# DM01.net
KiCad netlist of a schematic drawn in EAGLE
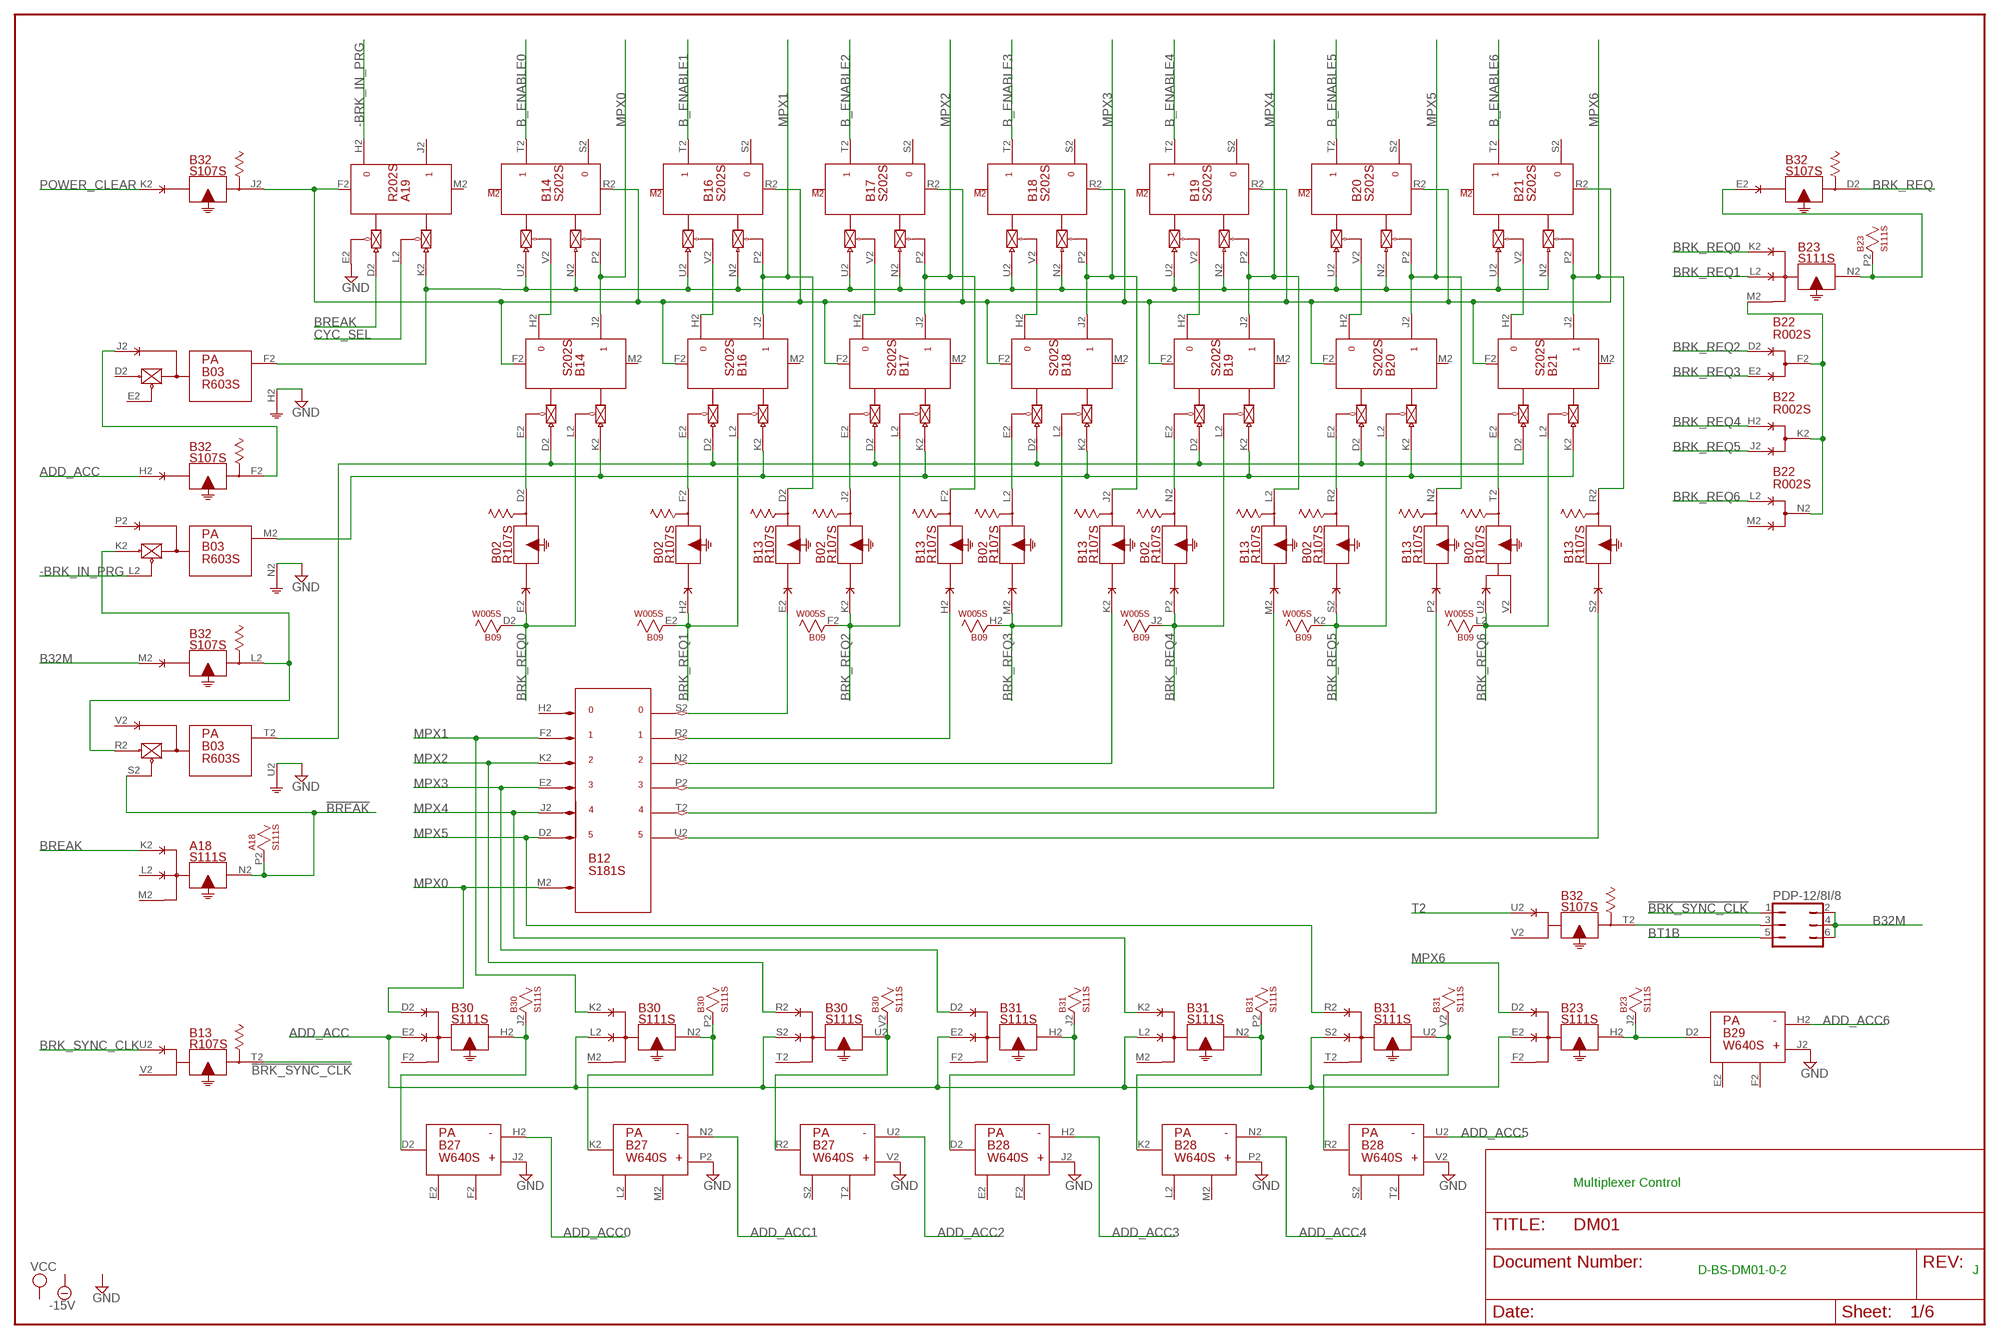
[diagram p0: schematic, sheet 1]
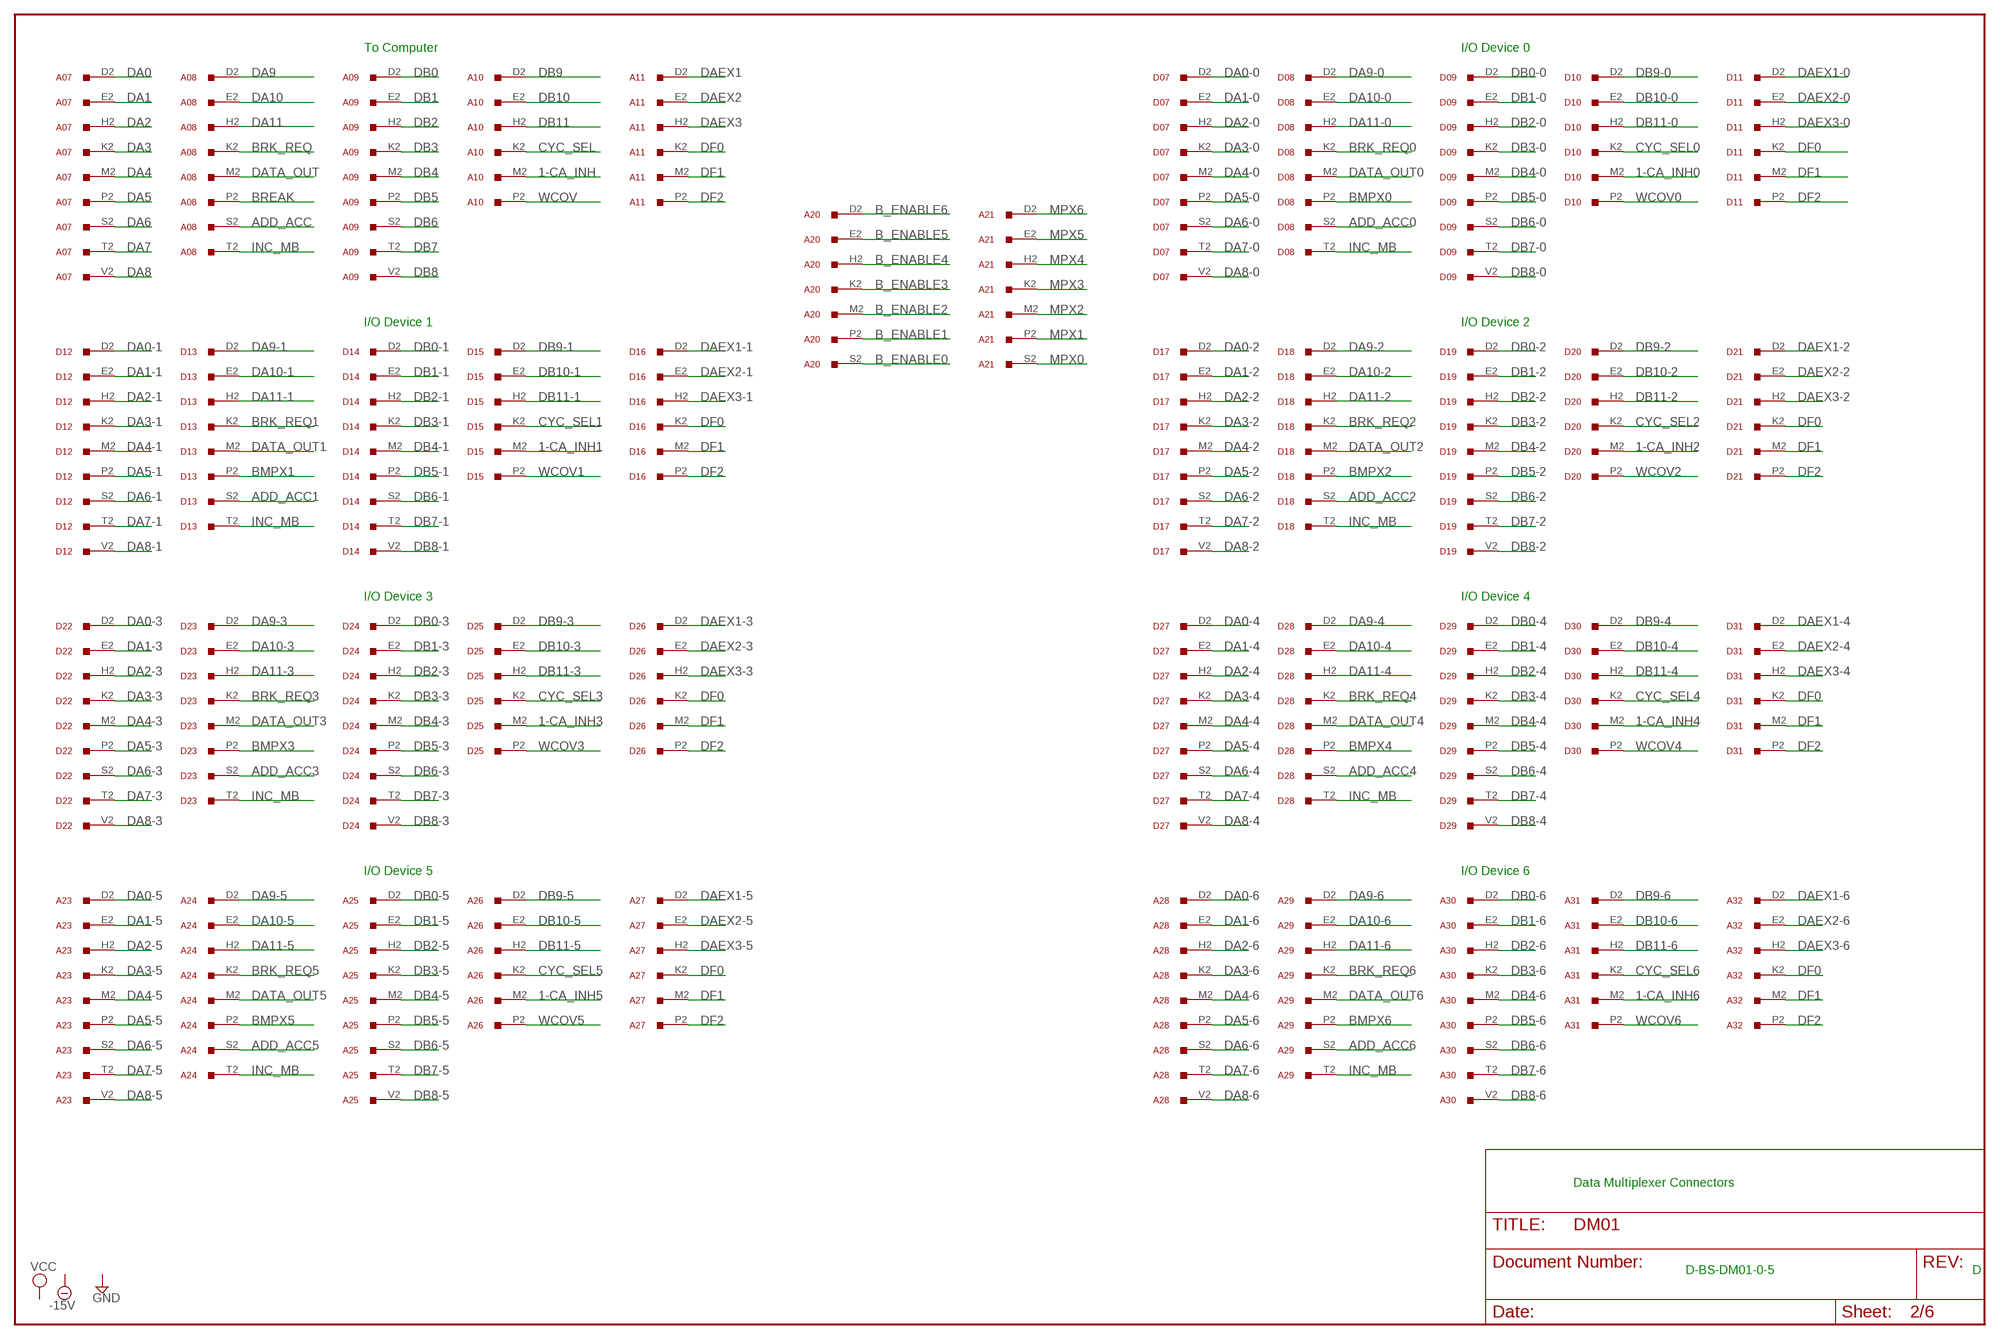
[diagram p1: schematic, sheet 2]
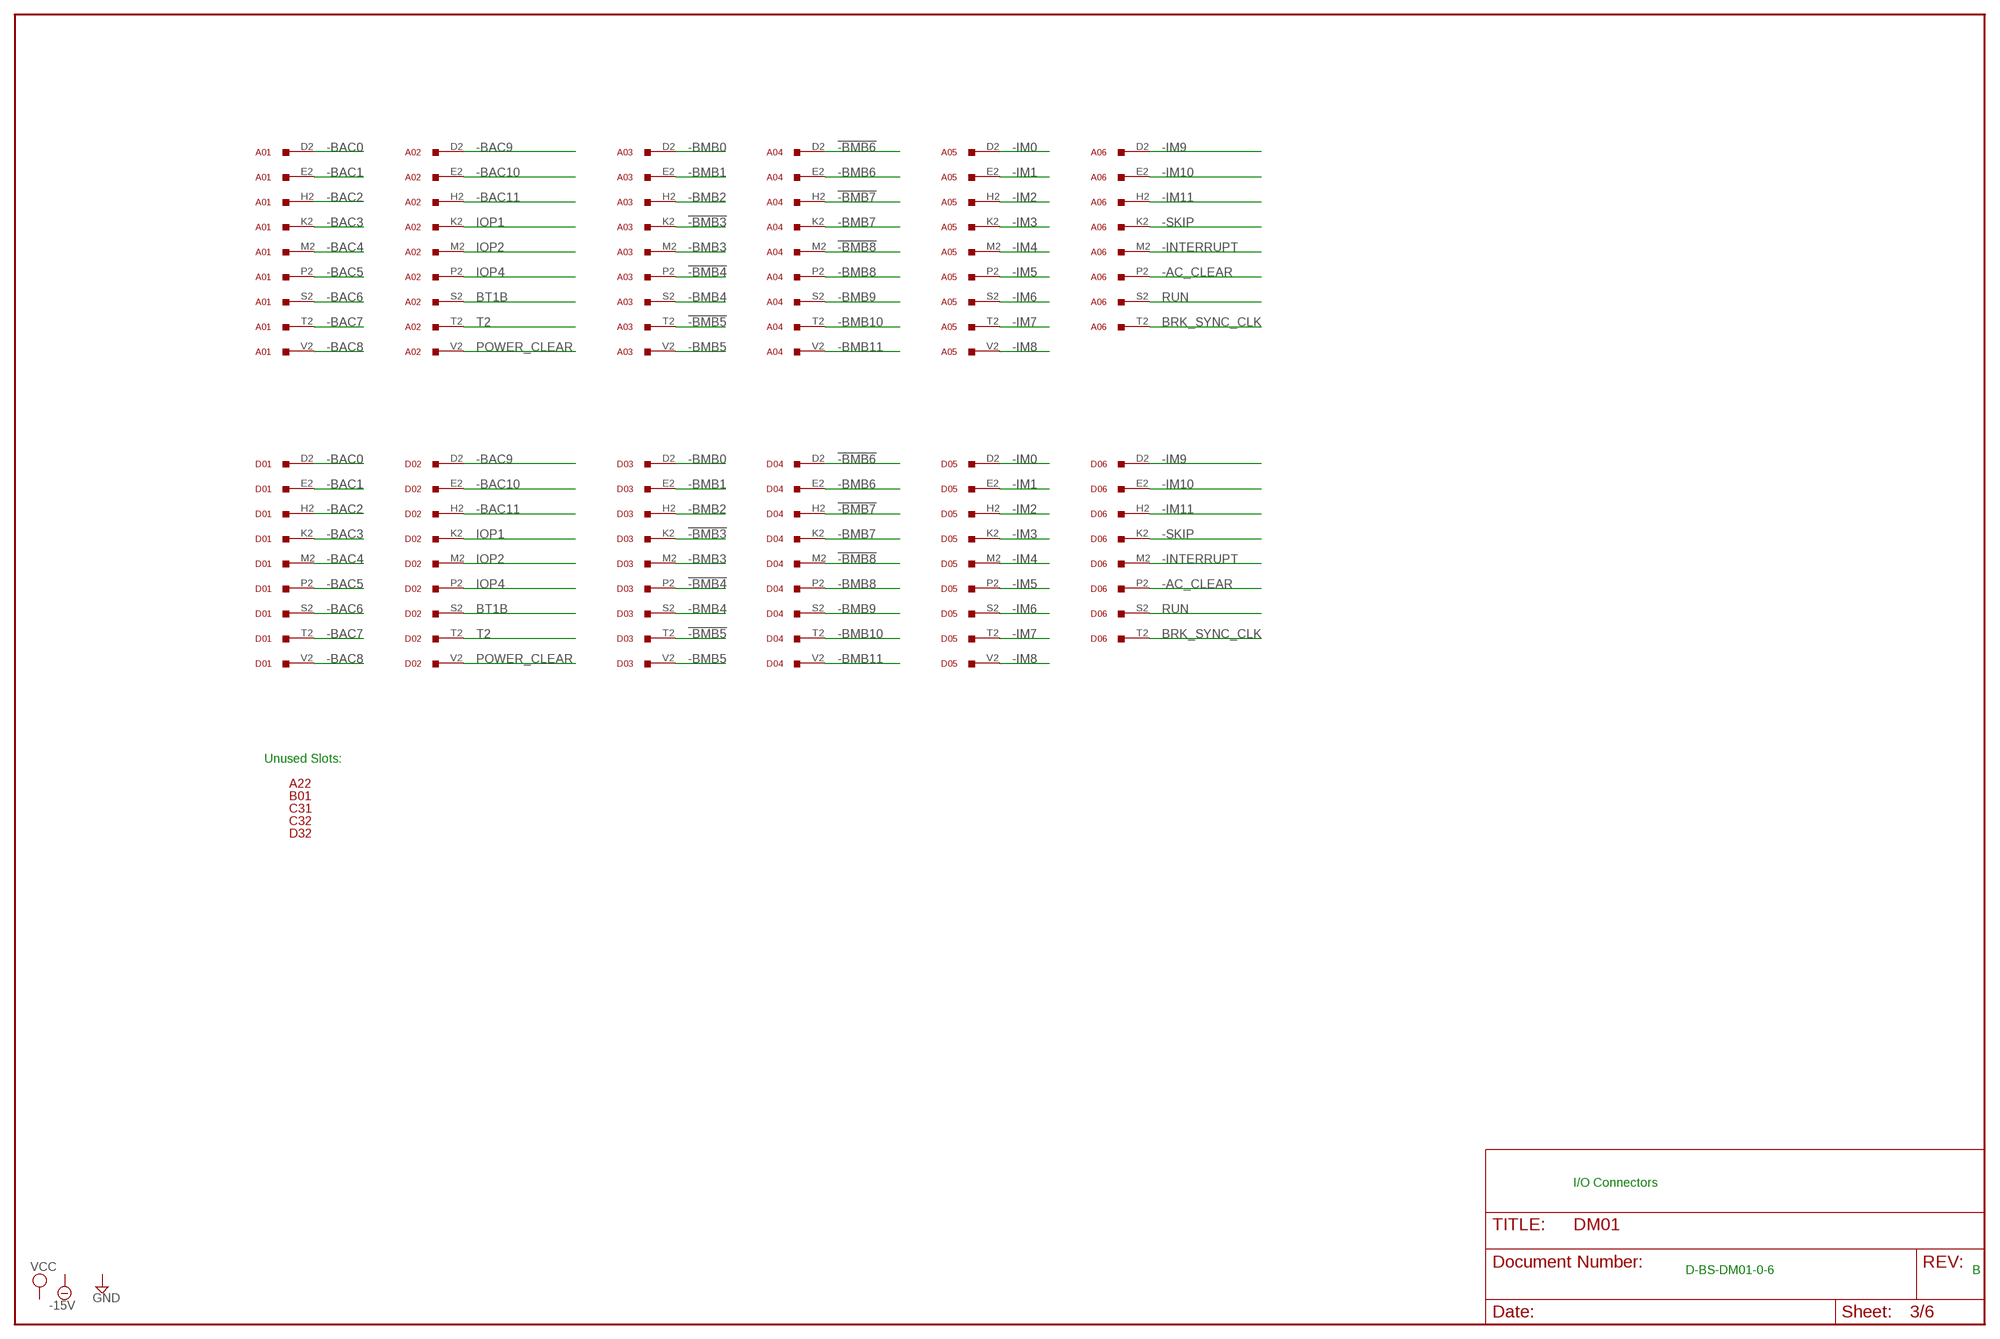
[diagram p2: schematic, sheet 3]
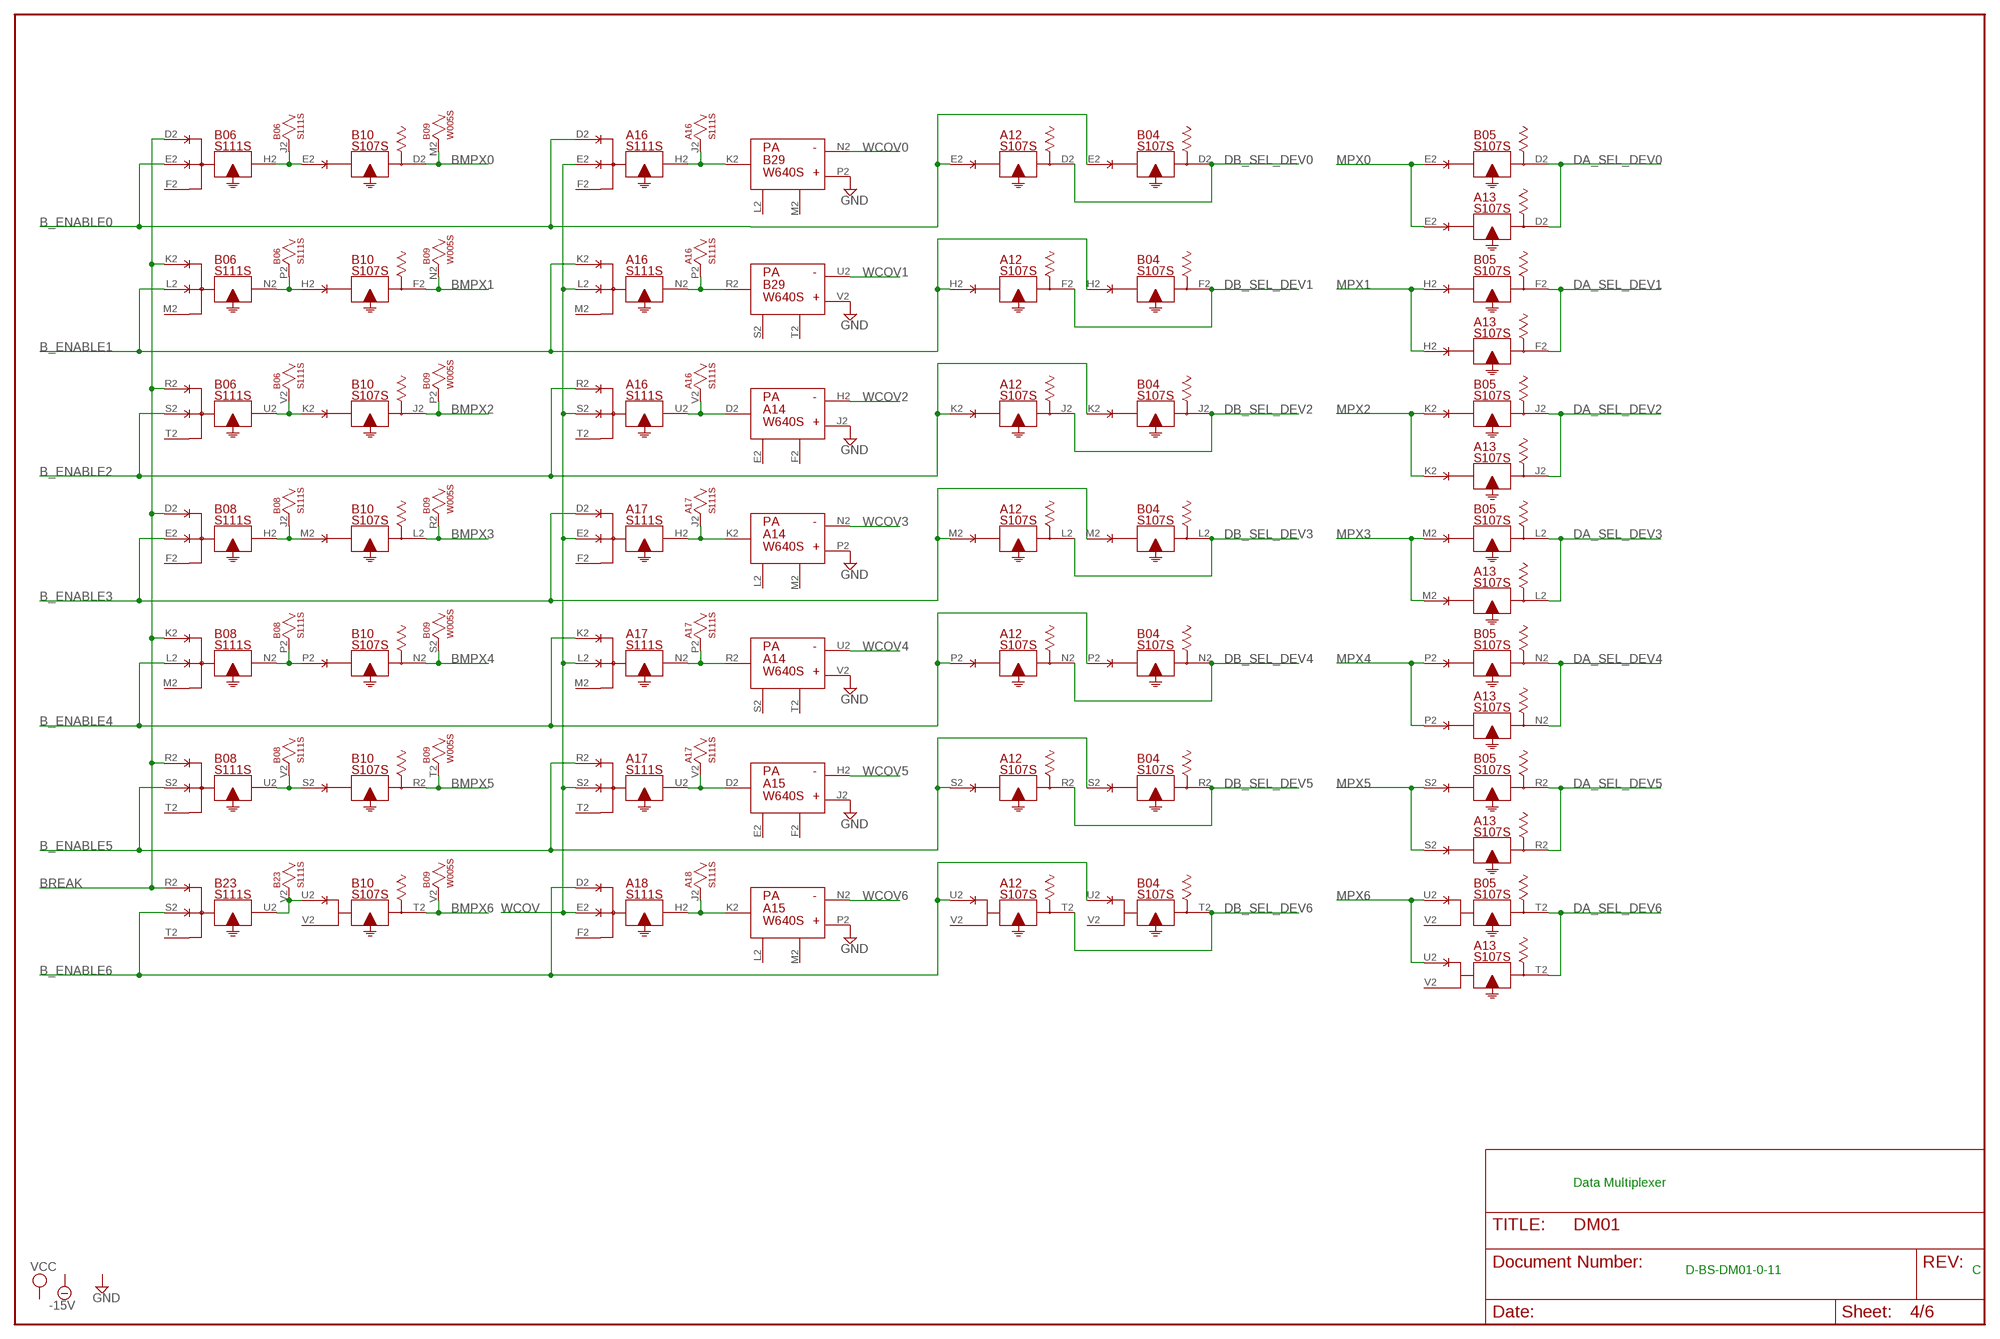
[diagram p3: schematic, sheet 4]
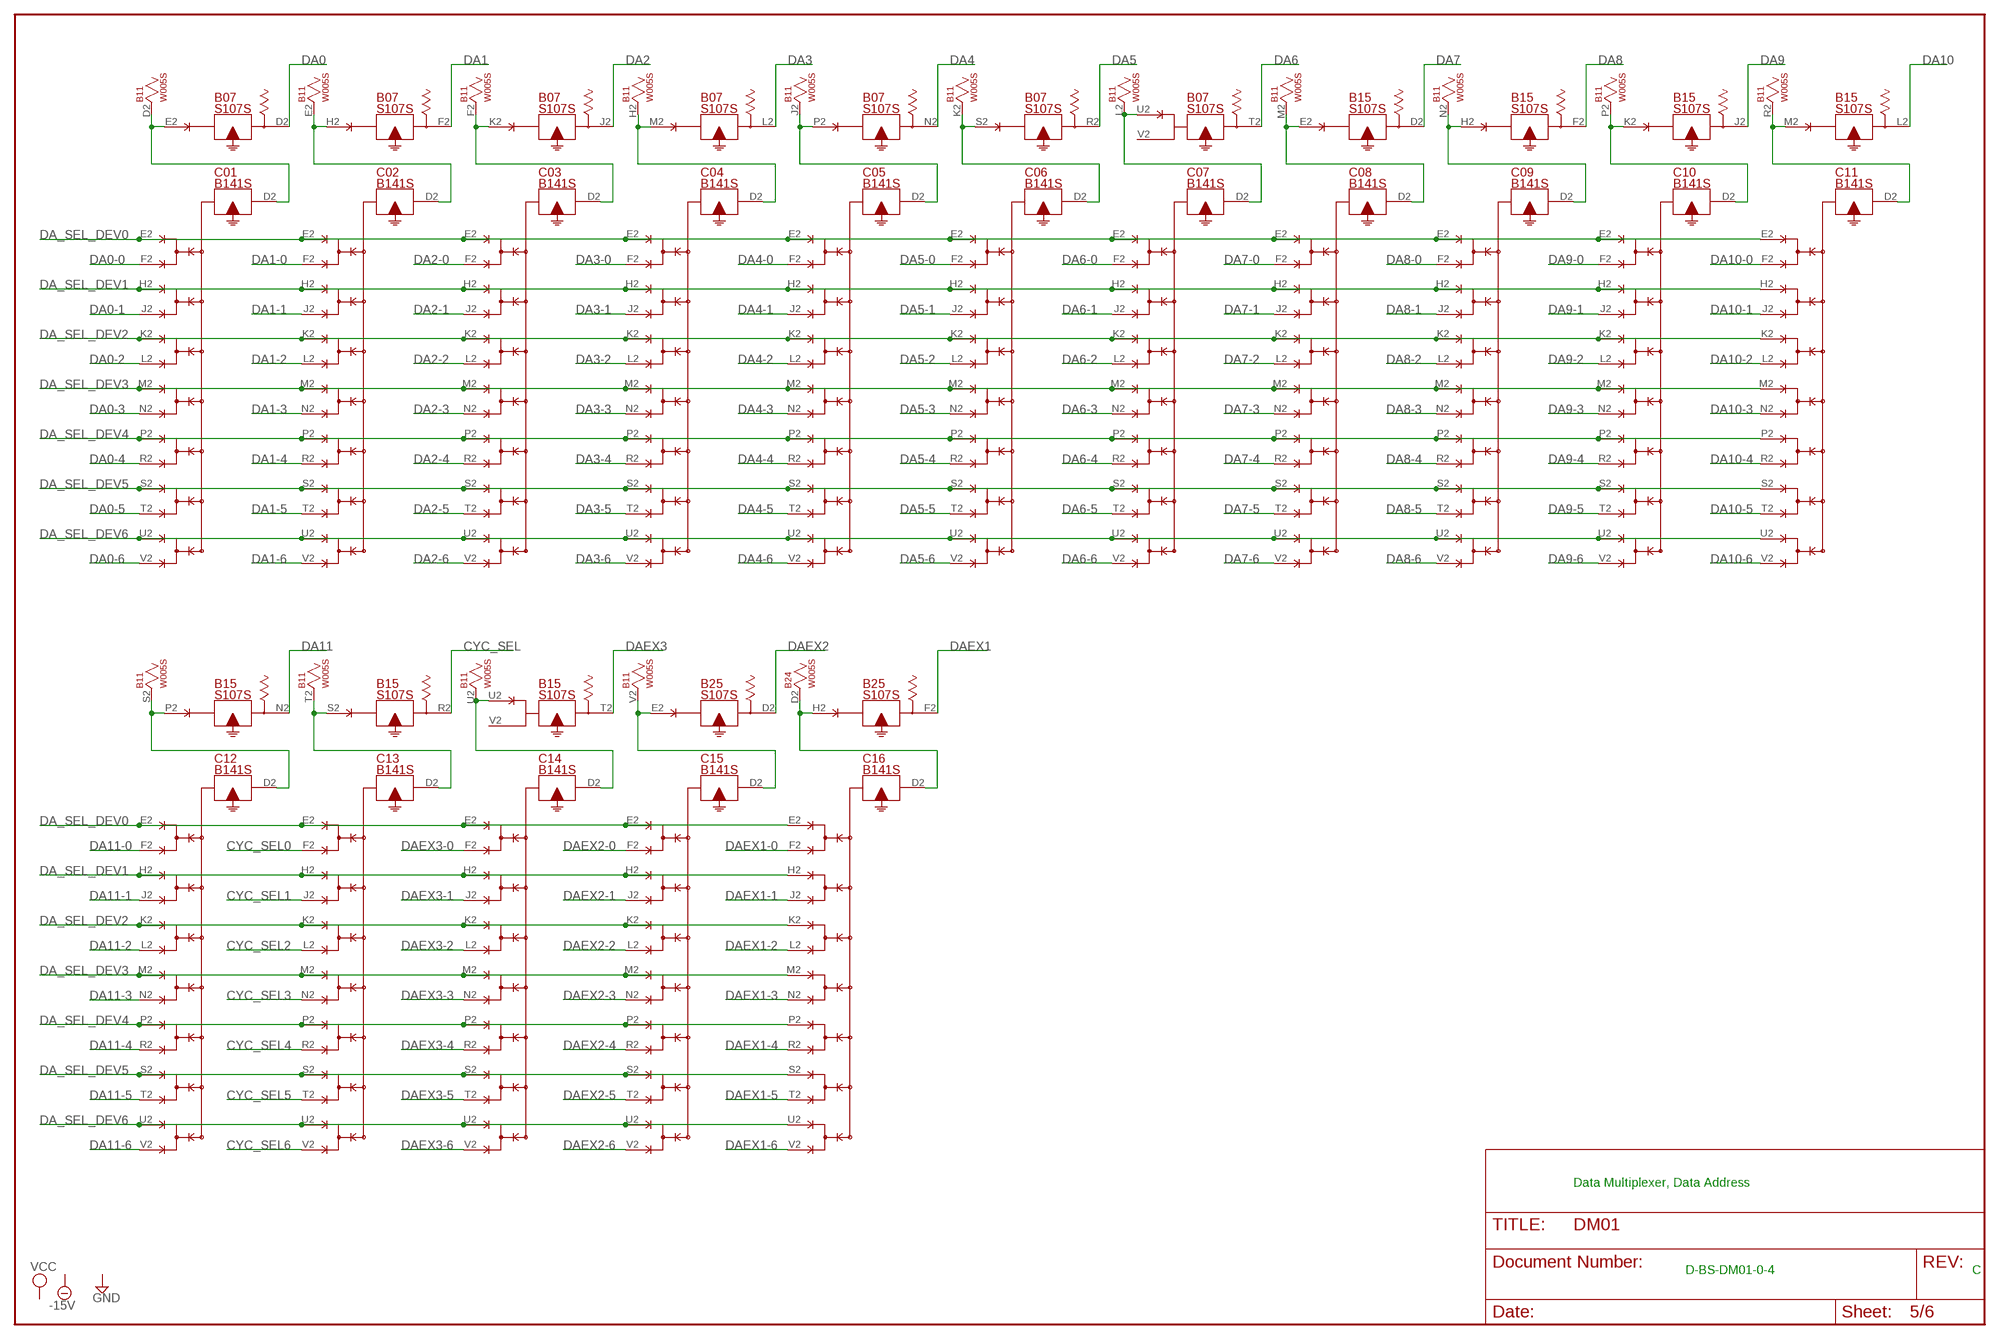
[diagram p4: schematic, sheet 5]
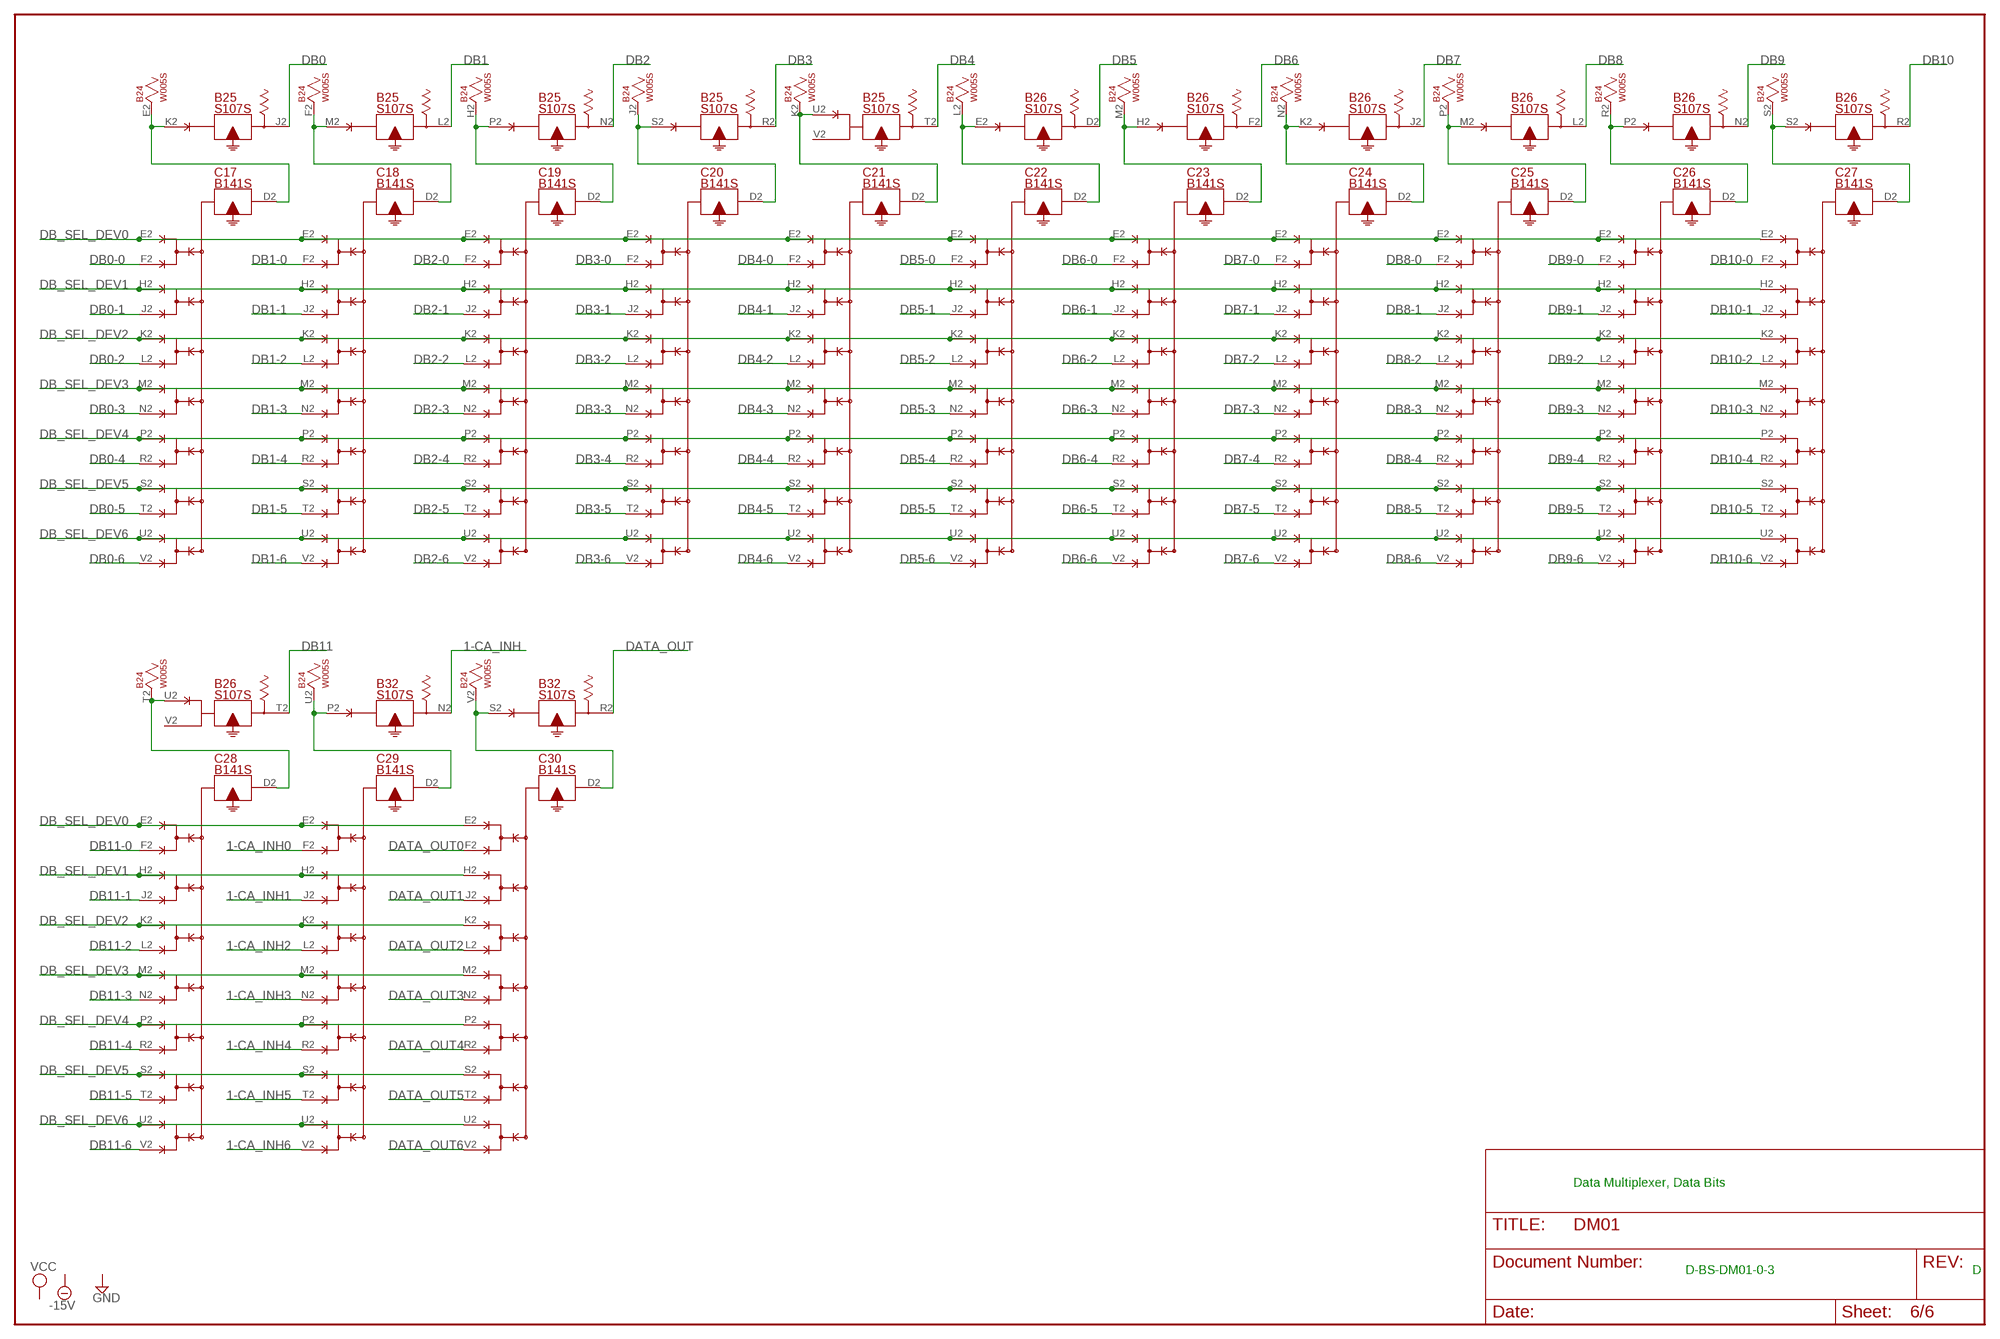
[diagram p5: schematic, sheet 6]

(export (version "E")
  (design (tool "Eeschema 10.0.6"))
  (components
    (comp (ref "A18")
      (value "S111S")
      (footprint "eagle-import:H807S")
      (libsource (lib "eagle-import") (part "R111S"))
    )
    (comp (ref "A19")
      (value "R202S")
      (footprint "eagle-import:H807S")
      (libsource (lib "eagle-import") (part "R202S"))
    )
    (comp (ref "B02")
      (value "R107S")
      (footprint "eagle-import:H807S")
      (libsource (lib "eagle-import") (part "R107S"))
    )
    (comp (ref "B03")
      (value "R603S")
      (footprint "eagle-import:H807S")
      (libsource (lib "eagle-import") (part "R603S"))
    )
    (comp (ref "B09")
      (value "W005S")
      (footprint "eagle-import:H807S")
      (libsource (lib "eagle-import") (part "W005S"))
    )
    (comp (ref "B12")
      (value "S181S")
      (footprint "eagle-import:H807S")
      (libsource (lib "eagle-import") (part "R181S"))
    )
    (comp (ref "B13")
      (value "R107S")
      (footprint "eagle-import:H807S")
      (libsource (lib "eagle-import") (part "R107S"))
    )
    (comp (ref "B14")
      (value "S202S")
      (footprint "eagle-import:H807S")
      (libsource (lib "eagle-import") (part "R202S"))
    )
    (comp (ref "B16")
      (value "S202S")
      (footprint "eagle-import:H807S")
      (libsource (lib "eagle-import") (part "R202S"))
    )
    (comp (ref "B17")
      (value "S202S")
      (footprint "eagle-import:H807S")
      (libsource (lib "eagle-import") (part "R202S"))
    )
    (comp (ref "B18")
      (value "S202S")
      (footprint "eagle-import:H807S")
      (libsource (lib "eagle-import") (part "R202S"))
    )
    (comp (ref "B19")
      (value "S202S")
      (footprint "eagle-import:H807S")
      (libsource (lib "eagle-import") (part "R202S"))
    )
    (comp (ref "B20")
      (value "S202S")
      (footprint "eagle-import:H807S")
      (libsource (lib "eagle-import") (part "R202S"))
    )
    (comp (ref "B21")
      (value "S202S")
      (footprint "eagle-import:H807S")
      (libsource (lib "eagle-import") (part "R202S"))
    )
    (comp (ref "B22")
      (value "R002S")
      (footprint "eagle-import:H807S")
      (libsource (lib "eagle-import") (part "R002S"))
    )
    (comp (ref "B23")
      (value "S111S")
      (footprint "eagle-import:H807S")
      (libsource (lib "eagle-import") (part "R111S"))
    )
    (comp (ref "B27")
      (value "W640S")
      (footprint "eagle-import:H807S")
      (libsource (lib "eagle-import") (part "W640S"))
    )
    (comp (ref "B28")
      (value "W640S")
      (footprint "eagle-import:H807S")
      (libsource (lib "eagle-import") (part "W640S"))
    )
    (comp (ref "B29")
      (value "W640S")
      (footprint "eagle-import:H807S")
      (libsource (lib "eagle-import") (part "W640S"))
    )
    (comp (ref "B30")
      (value "S111S")
      (footprint "eagle-import:H807S")
      (libsource (lib "eagle-import") (part "R111S"))
    )
    (comp (ref "B31")
      (value "S111S")
      (footprint "eagle-import:H807S")
      (libsource (lib "eagle-import") (part "R111S"))
    )
    (comp (ref "B32")
      (value "S107S")
      (footprint "eagle-import:H807S")
      (libsource (lib "eagle-import") (part "R107S"))
    )
    (comp (ref "PDP-12/8I/8")
      (value "JP3Q")
      (footprint "eagle-import:JP3Q")
      (libsource (lib "eagle-import") (part "JP3Q"))
    )
    (comp (ref "A07")
      (value "W021S")
      (footprint "eagle-import:H807S")
      (libsource (lib "eagle-import") (part "W021S"))
    )
    (comp (ref "A08")
      (value "W021S")
      (footprint "eagle-import:H807S")
      (libsource (lib "eagle-import") (part "W021S"))
    )
    (comp (ref "A09")
      (value "W021S")
      (footprint "eagle-import:H807S")
      (libsource (lib "eagle-import") (part "W021S"))
    )
    (comp (ref "A10")
      (value "W021S")
      (footprint "eagle-import:H807S")
      (libsource (lib "eagle-import") (part "W021S"))
    )
    (comp (ref "A11")
      (value "W021S")
      (footprint "eagle-import:H807S")
      (libsource (lib "eagle-import") (part "W021S"))
    )
    (comp (ref "A20")
      (value "W021S")
      (footprint "eagle-import:H807S")
      (libsource (lib "eagle-import") (part "W021S"))
    )
    (comp (ref "A21")
      (value "W021S")
      (footprint "eagle-import:H807S")
      (libsource (lib "eagle-import") (part "W021S"))
    )
    (comp (ref "A23")
      (value "W021S")
      (footprint "eagle-import:H807S")
      (libsource (lib "eagle-import") (part "W021S"))
    )
    (comp (ref "A24")
      (value "W021S")
      (footprint "eagle-import:H807S")
      (libsource (lib "eagle-import") (part "W021S"))
    )
    (comp (ref "A25")
      (value "W021S")
      (footprint "eagle-import:H807S")
      (libsource (lib "eagle-import") (part "W021S"))
    )
    (comp (ref "A26")
      (value "W021S")
      (footprint "eagle-import:H807S")
      (libsource (lib "eagle-import") (part "W021S"))
    )
    (comp (ref "A27")
      (value "W021S")
      (footprint "eagle-import:H807S")
      (libsource (lib "eagle-import") (part "W021S"))
    )
    (comp (ref "A28")
      (value "W021S")
      (footprint "eagle-import:H807S")
      (libsource (lib "eagle-import") (part "W021S"))
    )
    (comp (ref "A29")
      (value "W021S")
      (footprint "eagle-import:H807S")
      (libsource (lib "eagle-import") (part "W021S"))
    )
    (comp (ref "A30")
      (value "W021S")
      (footprint "eagle-import:H807S")
      (libsource (lib "eagle-import") (part "W021S"))
    )
    (comp (ref "A31")
      (value "W021S")
      (footprint "eagle-import:H807S")
      (libsource (lib "eagle-import") (part "W021S"))
    )
    (comp (ref "A32")
      (value "W021S")
      (footprint "eagle-import:H807S")
      (libsource (lib "eagle-import") (part "W021S"))
    )
    (comp (ref "D07")
      (value "W021S")
      (footprint "eagle-import:H807S")
      (libsource (lib "eagle-import") (part "W021S"))
    )
    (comp (ref "D08")
      (value "W021S")
      (footprint "eagle-import:H807S")
      (libsource (lib "eagle-import") (part "W021S"))
    )
    (comp (ref "D09")
      (value "W021S")
      (footprint "eagle-import:H807S")
      (libsource (lib "eagle-import") (part "W021S"))
    )
    (comp (ref "D10")
      (value "W021S")
      (footprint "eagle-import:H807S")
      (libsource (lib "eagle-import") (part "W021S"))
    )
    (comp (ref "D11")
      (value "W021S")
      (footprint "eagle-import:H807S")
      (libsource (lib "eagle-import") (part "W021S"))
    )
    (comp (ref "D12")
      (value "W021S")
      (footprint "eagle-import:H807S")
      (libsource (lib "eagle-import") (part "W021S"))
    )
    (comp (ref "D13")
      (value "W021S")
      (footprint "eagle-import:H807S")
      (libsource (lib "eagle-import") (part "W021S"))
    )
    (comp (ref "D14")
      (value "W021S")
      (footprint "eagle-import:H807S")
      (libsource (lib "eagle-import") (part "W021S"))
    )
    (comp (ref "D15")
      (value "W021S")
      (footprint "eagle-import:H807S")
      (libsource (lib "eagle-import") (part "W021S"))
    )
    (comp (ref "D16")
      (value "W021S")
      (footprint "eagle-import:H807S")
      (libsource (lib "eagle-import") (part "W021S"))
    )
    (comp (ref "D17")
      (value "W021S")
      (footprint "eagle-import:H807S")
      (libsource (lib "eagle-import") (part "W021S"))
    )
    (comp (ref "D18")
      (value "W021S")
      (footprint "eagle-import:H807S")
      (libsource (lib "eagle-import") (part "W021S"))
    )
    (comp (ref "D19")
      (value "W021S")
      (footprint "eagle-import:H807S")
      (libsource (lib "eagle-import") (part "W021S"))
    )
    (comp (ref "D20")
      (value "W021S")
      (footprint "eagle-import:H807S")
      (libsource (lib "eagle-import") (part "W021S"))
    )
    (comp (ref "D21")
      (value "W021S")
      (footprint "eagle-import:H807S")
      (libsource (lib "eagle-import") (part "W021S"))
    )
    (comp (ref "D22")
      (value "W021S")
      (footprint "eagle-import:H807S")
      (libsource (lib "eagle-import") (part "W021S"))
    )
    (comp (ref "D23")
      (value "W021S")
      (footprint "eagle-import:H807S")
      (libsource (lib "eagle-import") (part "W021S"))
    )
    (comp (ref "D24")
      (value "W021S")
      (footprint "eagle-import:H807S")
      (libsource (lib "eagle-import") (part "W021S"))
    )
    (comp (ref "D25")
      (value "W021S")
      (footprint "eagle-import:H807S")
      (libsource (lib "eagle-import") (part "W021S"))
    )
    (comp (ref "D26")
      (value "W021S")
      (footprint "eagle-import:H807S")
      (libsource (lib "eagle-import") (part "W021S"))
    )
    (comp (ref "D27")
      (value "W021S")
      (footprint "eagle-import:H807S")
      (libsource (lib "eagle-import") (part "W021S"))
    )
    (comp (ref "D28")
      (value "W021S")
      (footprint "eagle-import:H807S")
      (libsource (lib "eagle-import") (part "W021S"))
    )
    (comp (ref "D29")
      (value "W021S")
      (footprint "eagle-import:H807S")
      (libsource (lib "eagle-import") (part "W021S"))
    )
    (comp (ref "D30")
      (value "W021S")
      (footprint "eagle-import:H807S")
      (libsource (lib "eagle-import") (part "W021S"))
    )
    (comp (ref "D31")
      (value "W021S")
      (footprint "eagle-import:H807S")
      (libsource (lib "eagle-import") (part "W021S"))
    )
    (comp (ref "B24")
      (value "W005S")
      (footprint "eagle-import:H807S")
      (libsource (lib "eagle-import") (part "W005S"))
    )
    (comp (ref "B25")
      (value "S107S")
      (footprint "eagle-import:H807S")
      (libsource (lib "eagle-import") (part "R107S"))
    )
    (comp (ref "B26")
      (value "S107S")
      (footprint "eagle-import:H807S")
      (libsource (lib "eagle-import") (part "R107S"))
    )
    (comp (ref "C17")
      (value "B141S")
      (footprint "eagle-import:H807S")
      (libsource (lib "eagle-import") (part "R141S"))
    )
    (comp (ref "C18")
      (value "B141S")
      (footprint "eagle-import:H807S")
      (libsource (lib "eagle-import") (part "R141S"))
    )
    (comp (ref "C19")
      (value "B141S")
      (footprint "eagle-import:H807S")
      (libsource (lib "eagle-import") (part "R141S"))
    )
    (comp (ref "C20")
      (value "B141S")
      (footprint "eagle-import:H807S")
      (libsource (lib "eagle-import") (part "R141S"))
    )
    (comp (ref "C21")
      (value "B141S")
      (footprint "eagle-import:H807S")
      (libsource (lib "eagle-import") (part "R141S"))
    )
    (comp (ref "C22")
      (value "B141S")
      (footprint "eagle-import:H807S")
      (libsource (lib "eagle-import") (part "R141S"))
    )
    (comp (ref "C23")
      (value "B141S")
      (footprint "eagle-import:H807S")
      (libsource (lib "eagle-import") (part "R141S"))
    )
    (comp (ref "C24")
      (value "B141S")
      (footprint "eagle-import:H807S")
      (libsource (lib "eagle-import") (part "R141S"))
    )
    (comp (ref "C25")
      (value "B141S")
      (footprint "eagle-import:H807S")
      (libsource (lib "eagle-import") (part "R141S"))
    )
    (comp (ref "C26")
      (value "B141S")
      (footprint "eagle-import:H807S")
      (libsource (lib "eagle-import") (part "R141S"))
    )
    (comp (ref "C27")
      (value "B141S")
      (footprint "eagle-import:H807S")
      (libsource (lib "eagle-import") (part "R141S"))
    )
    (comp (ref "C28")
      (value "B141S")
      (footprint "eagle-import:H807S")
      (libsource (lib "eagle-import") (part "R141S"))
    )
    (comp (ref "C29")
      (value "B141S")
      (footprint "eagle-import:H807S")
      (libsource (lib "eagle-import") (part "R141S"))
    )
    (comp (ref "C30")
      (value "B141S")
      (footprint "eagle-import:H807S")
      (libsource (lib "eagle-import") (part "R141S"))
    )
    (comp (ref "A01")
      (value "W021S")
      (footprint "eagle-import:H807S")
      (libsource (lib "eagle-import") (part "W021S"))
    )
    (comp (ref "A02")
      (value "W021S")
      (footprint "eagle-import:H807S")
      (libsource (lib "eagle-import") (part "W021S"))
    )
    (comp (ref "A03")
      (value "W021S")
      (footprint "eagle-import:H807S")
      (libsource (lib "eagle-import") (part "W021S"))
    )
    (comp (ref "A04")
      (value "W021S")
      (footprint "eagle-import:H807S")
      (libsource (lib "eagle-import") (part "W021S"))
    )
    (comp (ref "A05")
      (value "W021S")
      (footprint "eagle-import:H807S")
      (libsource (lib "eagle-import") (part "W021S"))
    )
    (comp (ref "A06")
      (value "W021S")
      (footprint "eagle-import:H807S")
      (libsource (lib "eagle-import") (part "W021S"))
    )
    (comp (ref "A22")
      (value "EMPTYS")
      (footprint "eagle-import:H807S")
      (libsource (lib "eagle-import") (part "EMPTYS"))
    )
    (comp (ref "B01")
      (value "EMPTYS")
      (footprint "eagle-import:H807S")
      (libsource (lib "eagle-import") (part "EMPTYS"))
    )
    (comp (ref "C31")
      (value "EMPTYS")
      (footprint "eagle-import:H807S")
      (libsource (lib "eagle-import") (part "EMPTYS"))
    )
    (comp (ref "C32")
      (value "EMPTYS")
      (footprint "eagle-import:H807S")
      (libsource (lib "eagle-import") (part "EMPTYS"))
    )
    (comp (ref "D01")
      (value "W021S")
      (footprint "eagle-import:H807S")
      (libsource (lib "eagle-import") (part "W021S"))
    )
    (comp (ref "D02")
      (value "W021S")
      (footprint "eagle-import:H807S")
      (libsource (lib "eagle-import") (part "W021S"))
    )
    (comp (ref "D03")
      (value "W021S")
      (footprint "eagle-import:H807S")
      (libsource (lib "eagle-import") (part "W021S"))
    )
    (comp (ref "D04")
      (value "W021S")
      (footprint "eagle-import:H807S")
      (libsource (lib "eagle-import") (part "W021S"))
    )
    (comp (ref "D05")
      (value "W021S")
      (footprint "eagle-import:H807S")
      (libsource (lib "eagle-import") (part "W021S"))
    )
    (comp (ref "D06")
      (value "W021S")
      (footprint "eagle-import:H807S")
      (libsource (lib "eagle-import") (part "W021S"))
    )
    (comp (ref "D32")
      (value "EMPTYS")
      (footprint "eagle-import:H807S")
      (libsource (lib "eagle-import") (part "EMPTYS"))
    )
    (comp (ref "B07")
      (value "S107S")
      (footprint "eagle-import:H807S")
      (libsource (lib "eagle-import") (part "R107S"))
    )
    (comp (ref "B11")
      (value "W005S")
      (footprint "eagle-import:H807S")
      (libsource (lib "eagle-import") (part "W005S"))
    )
    (comp (ref "B15")
      (value "S107S")
      (footprint "eagle-import:H807S")
      (libsource (lib "eagle-import") (part "R107S"))
    )
    (comp (ref "C01")
      (value "B141S")
      (footprint "eagle-import:H807S")
      (libsource (lib "eagle-import") (part "R141S"))
    )
    (comp (ref "C02")
      (value "B141S")
      (footprint "eagle-import:H807S")
      (libsource (lib "eagle-import") (part "R141S"))
    )
    (comp (ref "C03")
      (value "B141S")
      (footprint "eagle-import:H807S")
      (libsource (lib "eagle-import") (part "R141S"))
    )
    (comp (ref "C04")
      (value "B141S")
      (footprint "eagle-import:H807S")
      (libsource (lib "eagle-import") (part "R141S"))
    )
    (comp (ref "C05")
      (value "B141S")
      (footprint "eagle-import:H807S")
      (libsource (lib "eagle-import") (part "R141S"))
    )
    (comp (ref "C06")
      (value "B141S")
      (footprint "eagle-import:H807S")
      (libsource (lib "eagle-import") (part "R141S"))
    )
    (comp (ref "C07")
      (value "B141S")
      (footprint "eagle-import:H807S")
      (libsource (lib "eagle-import") (part "R141S"))
    )
    (comp (ref "C08")
      (value "B141S")
      (footprint "eagle-import:H807S")
      (libsource (lib "eagle-import") (part "R141S"))
    )
    (comp (ref "C09")
      (value "B141S")
      (footprint "eagle-import:H807S")
      (libsource (lib "eagle-import") (part "R141S"))
    )
    (comp (ref "C10")
      (value "B141S")
      (footprint "eagle-import:H807S")
      (libsource (lib "eagle-import") (part "R141S"))
    )
    (comp (ref "C11")
      (value "B141S")
      (footprint "eagle-import:H807S")
      (libsource (lib "eagle-import") (part "R141S"))
    )
    (comp (ref "C12")
      (value "B141S")
      (footprint "eagle-import:H807S")
      (libsource (lib "eagle-import") (part "R141S"))
    )
    (comp (ref "C13")
      (value "B141S")
      (footprint "eagle-import:H807S")
      (libsource (lib "eagle-import") (part "R141S"))
    )
    (comp (ref "C14")
      (value "B141S")
      (footprint "eagle-import:H807S")
      (libsource (lib "eagle-import") (part "R141S"))
    )
    (comp (ref "C15")
      (value "B141S")
      (footprint "eagle-import:H807S")
      (libsource (lib "eagle-import") (part "R141S"))
    )
    (comp (ref "C16")
      (value "B141S")
      (footprint "eagle-import:H807S")
      (libsource (lib "eagle-import") (part "R141S"))
    )
    (comp (ref "A12")
      (value "S107S")
      (footprint "eagle-import:H807S")
      (libsource (lib "eagle-import") (part "R107S"))
    )
    (comp (ref "A13")
      (value "S107S")
      (footprint "eagle-import:H807S")
      (libsource (lib "eagle-import") (part "R107S"))
    )
    (comp (ref "A14")
      (value "W640S")
      (footprint "eagle-import:H807S")
      (libsource (lib "eagle-import") (part "W640S"))
    )
    (comp (ref "A15")
      (value "W640S")
      (footprint "eagle-import:H807S")
      (libsource (lib "eagle-import") (part "W640S"))
    )
    (comp (ref "A16")
      (value "S111S")
      (footprint "eagle-import:H807S")
      (libsource (lib "eagle-import") (part "R111S"))
    )
    (comp (ref "A17")
      (value "S111S")
      (footprint "eagle-import:H807S")
      (libsource (lib "eagle-import") (part "R111S"))
    )
    (comp (ref "B04")
      (value "S107S")
      (footprint "eagle-import:H807S")
      (libsource (lib "eagle-import") (part "R107S"))
    )
    (comp (ref "B05")
      (value "S107S")
      (footprint "eagle-import:H807S")
      (libsource (lib "eagle-import") (part "R107S"))
    )
    (comp (ref "B06")
      (value "S111S")
      (footprint "eagle-import:H807S")
      (libsource (lib "eagle-import") (part "R111S"))
    )
    (comp (ref "B08")
      (value "S111S")
      (footprint "eagle-import:H807S")
      (libsource (lib "eagle-import") (part "R111S"))
    )
    (comp (ref "B10")
      (value "S107S")
      (footprint "eagle-import:H807S")
      (libsource (lib "eagle-import") (part "R107S"))
    )
  )
  (nets
    (net (code "2") (name "-AC_CLEAR") (class "Default")
      (node (ref "A06") (pin "P2") (pinfunction "P$2_P2") (pintype "bidirectional"))
      (node (ref "D06") (pin "P2") (pinfunction "P$2_P2") (pintype "bidirectional"))
    )
    (net (code "3") (name "-BAC0") (class "Default")
      (node (ref "A01") (pin "D2") (pinfunction "P$2_D2") (pintype "bidirectional"))
      (node (ref "D01") (pin "D2") (pinfunction "P$2_D2") (pintype "bidirectional"))
    )
    (net (code "4") (name "-BAC1") (class "Default")
      (node (ref "A01") (pin "E2") (pinfunction "P$2_E2") (pintype "bidirectional"))
      (node (ref "D01") (pin "E2") (pinfunction "P$2_E2") (pintype "bidirectional"))
    )
    (net (code "5") (name "-BAC2") (class "Default")
      (node (ref "A01") (pin "H2") (pinfunction "P$2_H2") (pintype "bidirectional"))
      (node (ref "D01") (pin "H2") (pinfunction "P$2_H2") (pintype "bidirectional"))
    )
    (net (code "6") (name "-BAC3") (class "Default")
      (node (ref "A01") (pin "K2") (pinfunction "P$2_K2") (pintype "bidirectional"))
      (node (ref "D01") (pin "K2") (pinfunction "P$2_K2") (pintype "bidirectional"))
    )
    (net (code "7") (name "-BAC4") (class "Default")
      (node (ref "A01") (pin "M2") (pinfunction "P$2_M2") (pintype "bidirectional"))
      (node (ref "D01") (pin "M2") (pinfunction "P$2_M2") (pintype "bidirectional"))
    )
    (net (code "8") (name "-BAC5") (class "Default")
      (node (ref "A01") (pin "P2") (pinfunction "P$2_P2") (pintype "bidirectional"))
      (node (ref "D01") (pin "P2") (pinfunction "P$2_P2") (pintype "bidirectional"))
    )
    (net (code "9") (name "-BAC6") (class "Default")
      (node (ref "A01") (pin "S2") (pinfunction "P$2_S2") (pintype "bidirectional"))
      (node (ref "D01") (pin "S2") (pinfunction "P$2_S2") (pintype "bidirectional"))
    )
    (net (code "10") (name "-BAC7") (class "Default")
      (node (ref "A01") (pin "T2") (pinfunction "P$2_T2") (pintype "bidirectional"))
      (node (ref "D01") (pin "T2") (pinfunction "P$2_T2") (pintype "bidirectional"))
    )
    (net (code "11") (name "-BAC8") (class "Default")
      (node (ref "A01") (pin "V2") (pinfunction "P$2_V2") (pintype "bidirectional"))
      (node (ref "D01") (pin "V2") (pinfunction "P$2_V2") (pintype "bidirectional"))
    )
    (net (code "12") (name "-BAC9") (class "Default")
      (node (ref "A02") (pin "D2") (pinfunction "P$2_D2") (pintype "bidirectional"))
      (node (ref "D02") (pin "D2") (pinfunction "P$2_D2") (pintype "bidirectional"))
    )
    (net (code "13") (name "-BAC10") (class "Default")
      (node (ref "A02") (pin "E2") (pinfunction "P$2_E2") (pintype "bidirectional"))
      (node (ref "D02") (pin "E2") (pinfunction "P$2_E2") (pintype "bidirectional"))
    )
    (net (code "14") (name "-BAC11") (class "Default")
      (node (ref "A02") (pin "H2") (pinfunction "P$2_H2") (pintype "bidirectional"))
      (node (ref "D02") (pin "H2") (pinfunction "P$2_H2") (pintype "bidirectional"))
    )
    (net (code "15") (name "-BMB0") (class "Default")
      (node (ref "A03") (pin "D2") (pinfunction "P$2_D2") (pintype "bidirectional"))
      (node (ref "D03") (pin "D2") (pinfunction "P$2_D2") (pintype "bidirectional"))
    )
    (net (code "16") (name "-BMB1") (class "Default")
      (node (ref "A03") (pin "E2") (pinfunction "P$2_E2") (pintype "bidirectional"))
      (node (ref "D03") (pin "E2") (pinfunction "P$2_E2") (pintype "bidirectional"))
    )
    (net (code "17") (name "-BMB2") (class "Default")
      (node (ref "A03") (pin "H2") (pinfunction "P$2_H2") (pintype "bidirectional"))
      (node (ref "D03") (pin "H2") (pinfunction "P$2_H2") (pintype "bidirectional"))
    )
    (net (code "18") (name "-BMB3") (class "Default")
      (node (ref "A03") (pin "M2") (pinfunction "P$2_M2") (pintype "bidirectional"))
      (node (ref "D03") (pin "M2") (pinfunction "P$2_M2") (pintype "bidirectional"))
    )
    (net (code "19") (name "-BMB4") (class "Default")
      (node (ref "A03") (pin "S2") (pinfunction "P$2_S2") (pintype "bidirectional"))
      (node (ref "D03") (pin "S2") (pinfunction "P$2_S2") (pintype "bidirectional"))
    )
    (net (code "20") (name "-BMB5") (class "Default")
      (node (ref "A03") (pin "V2") (pinfunction "P$2_V2") (pintype "bidirectional"))
      (node (ref "D03") (pin "V2") (pinfunction "P$2_V2") (pintype "bidirectional"))
    )
    (net (code "21") (name "-BMB6") (class "Default")
      (node (ref "A04") (pin "E2") (pinfunction "P$2_E2") (pintype "bidirectional"))
      (node (ref "D04") (pin "E2") (pinfunction "P$2_E2") (pintype "bidirectional"))
    )
    (net (code "22") (name "-BMB7") (class "Default")
      (node (ref "A04") (pin "K2") (pinfunction "P$2_K2") (pintype "bidirectional"))
      (node (ref "D04") (pin "K2") (pinfunction "P$2_K2") (pintype "bidirectional"))
    )
    (net (code "23") (name "-BMB8") (class "Default")
      (node (ref "A04") (pin "P2") (pinfunction "P$2_P2") (pintype "bidirectional"))
      (node (ref "D04") (pin "P2") (pinfunction "P$2_P2") (pintype "bidirectional"))
    )
    (net (code "24") (name "-BMB9") (class "Default")
      (node (ref "A04") (pin "S2") (pinfunction "P$2_S2") (pintype "bidirectional"))
      (node (ref "D04") (pin "S2") (pinfunction "P$2_S2") (pintype "bidirectional"))
    )
    (net (code "25") (name "-BMB10") (class "Default")
      (node (ref "A04") (pin "T2") (pinfunction "P$2_T2") (pintype "bidirectional"))
      (node (ref "D04") (pin "T2") (pinfunction "P$2_T2") (pintype "bidirectional"))
    )
    (net (code "26") (name "-BMB11") (class "Default")
      (node (ref "A04") (pin "V2") (pinfunction "P$2_V2") (pintype "bidirectional"))
      (node (ref "D04") (pin "V2") (pinfunction "P$2_V2") (pintype "bidirectional"))
    )
    (net (code "27") (name "-BRK_IN_PRG") (class "Default")
      (node (ref "A19") (pin "H2") (pinfunction "0_H2") (pintype "open_collector"))
      (node (ref "B03") (pin "L2") (pinfunction "EN0_L2") (pintype "passive"))
    )
    (net (code "28") (name "-IM0") (class "Default")
      (node (ref "A05") (pin "D2") (pinfunction "P$2_D2") (pintype "bidirectional"))
      (node (ref "D05") (pin "D2") (pinfunction "P$2_D2") (pintype "bidirectional"))
    )
    (net (code "29") (name "-IM1") (class "Default")
      (node (ref "A05") (pin "E2") (pinfunction "P$2_E2") (pintype "bidirectional"))
      (node (ref "D05") (pin "E2") (pinfunction "P$2_E2") (pintype "bidirectional"))
    )
    (net (code "30") (name "-IM2") (class "Default")
      (node (ref "A05") (pin "H2") (pinfunction "P$2_H2") (pintype "bidirectional"))
      (node (ref "D05") (pin "H2") (pinfunction "P$2_H2") (pintype "bidirectional"))
    )
    (net (code "31") (name "-IM3") (class "Default")
      (node (ref "A05") (pin "K2") (pinfunction "P$2_K2") (pintype "bidirectional"))
      (node (ref "D05") (pin "K2") (pinfunction "P$2_K2") (pintype "bidirectional"))
    )
    (net (code "32") (name "-IM4") (class "Default")
      (node (ref "A05") (pin "M2") (pinfunction "P$2_M2") (pintype "bidirectional"))
      (node (ref "D05") (pin "M2") (pinfunction "P$2_M2") (pintype "bidirectional"))
    )
    (net (code "33") (name "-IM5") (class "Default")
      (node (ref "A05") (pin "P2") (pinfunction "P$2_P2") (pintype "bidirectional"))
      (node (ref "D05") (pin "P2") (pinfunction "P$2_P2") (pintype "bidirectional"))
    )
    (net (code "34") (name "-IM6") (class "Default")
      (node (ref "A05") (pin "S2") (pinfunction "P$2_S2") (pintype "bidirectional"))
      (node (ref "D05") (pin "S2") (pinfunction "P$2_S2") (pintype "bidirectional"))
    )
    (net (code "35") (name "-IM7") (class "Default")
      (node (ref "A05") (pin "T2") (pinfunction "P$2_T2") (pintype "bidirectional"))
      (node (ref "D05") (pin "T2") (pinfunction "P$2_T2") (pintype "bidirectional"))
    )
    (net (code "36") (name "-IM8") (class "Default")
      (node (ref "A05") (pin "V2") (pinfunction "P$2_V2") (pintype "bidirectional"))
      (node (ref "D05") (pin "V2") (pinfunction "P$2_V2") (pintype "bidirectional"))
    )
    (net (code "37") (name "-IM9") (class "Default")
      (node (ref "A06") (pin "D2") (pinfunction "P$2_D2") (pintype "bidirectional"))
      (node (ref "D06") (pin "D2") (pinfunction "P$2_D2") (pintype "bidirectional"))
    )
    (net (code "38") (name "-IM10") (class "Default")
      (node (ref "A06") (pin "E2") (pinfunction "P$2_E2") (pintype "bidirectional"))
      (node (ref "D06") (pin "E2") (pinfunction "P$2_E2") (pintype "bidirectional"))
    )
    (net (code "39") (name "-IM11") (class "Default")
      (node (ref "A06") (pin "H2") (pinfunction "P$2_H2") (pintype "bidirectional"))
      (node (ref "D06") (pin "H2") (pinfunction "P$2_H2") (pintype "bidirectional"))
    )
    (net (code "40") (name "-INTERRUPT") (class "Default")
      (node (ref "A06") (pin "M2") (pinfunction "P$2_M2") (pintype "bidirectional"))
      (node (ref "D06") (pin "M2") (pinfunction "P$2_M2") (pintype "bidirectional"))
    )
    (net (code "41") (name "-SKIP") (class "Default")
      (node (ref "A06") (pin "K2") (pinfunction "P$2_K2") (pintype "bidirectional"))
      (node (ref "D06") (pin "K2") (pinfunction "P$2_K2") (pintype "bidirectional"))
    )
    (net (code "42") (name "1-CA_INH") (class "Default")
      (node (ref "A10") (pin "M2") (pinfunction "P$2_M2") (pintype "bidirectional"))
      (node (ref "B32") (pin "N2") (pinfunction "O$1_N2") (pintype "open_collector"))
    )
    (net (code "43") (name "1-CA_INH0") (class "Default")
      (node (ref "C29") (pin "F2") (pinfunction "F_F2") (pintype "input"))
      (node (ref "D10") (pin "M2") (pinfunction "P$2_M2") (pintype "bidirectional"))
    )
    (net (code "44") (name "1-CA_INH1") (class "Default")
      (node (ref "C29") (pin "J2") (pinfunction "J_J2") (pintype "input"))
      (node (ref "D15") (pin "M2") (pinfunction "P$2_M2") (pintype "bidirectional"))
    )
    (net (code "45") (name "1-CA_INH2") (class "Default")
      (node (ref "C29") (pin "L2") (pinfunction "L_L2") (pintype "input"))
      (node (ref "D20") (pin "M2") (pinfunction "P$2_M2") (pintype "bidirectional"))
    )
    (net (code "46") (name "1-CA_INH3") (class "Default")
      (node (ref "C29") (pin "N2") (pinfunction "N_N2") (pintype "input"))
      (node (ref "D25") (pin "M2") (pinfunction "P$2_M2") (pintype "bidirectional"))
    )
    (net (code "47") (name "1-CA_INH4") (class "Default")
      (node (ref "C29") (pin "R2") (pinfunction "R_R2") (pintype "input"))
      (node (ref "D30") (pin "M2") (pinfunction "P$2_M2") (pintype "bidirectional"))
    )
    (net (code "48") (name "1-CA_INH5") (class "Default")
      (node (ref "A26") (pin "M2") (pinfunction "P$2_M2") (pintype "bidirectional"))
      (node (ref "C29") (pin "T2") (pinfunction "T_T2") (pintype "input"))
    )
    (net (code "49") (name "1-CA_INH6") (class "Default")
      (node (ref "A31") (pin "M2") (pinfunction "P$2_M2") (pintype "bidirectional"))
      (node (ref "C29") (pin "V2") (pinfunction "V_V2") (pintype "input"))
    )
    (net (code "50") (name "ADD_ACC") (class "Default")
      (node (ref "A08") (pin "S2") (pinfunction "P$2_S2") (pintype "bidirectional"))
      (node (ref "B23") (pin "E2") (pinfunction "I$2_E2") (pintype "input"))
      (node (ref "B30") (pin "E2") (pinfunction "I$2_E2") (pintype "input"))
      (node (ref "B30") (pin "L2") (pinfunction "I$2_L2") (pintype "input"))
      (node (ref "B30") (pin "S2") (pinfunction "I$2_S2") (pintype "input"))
      (node (ref "B31") (pin "E2") (pinfunction "I$2_E2") (pintype "input"))
      (node (ref "B31") (pin "L2") (pinfunction "I$2_L2") (pintype "input"))
      (node (ref "B31") (pin "S2") (pinfunction "I$2_S2") (pintype "input"))
      (node (ref "B32") (pin "H2") (pinfunction "I$1_H2") (pintype "input"))
    )
    (net (code "51") (name "ADD_ACC0") (class "Default")
      (node (ref "B27") (pin "H2") (pinfunction "H_H2") (pintype "output"))
      (node (ref "D08") (pin "S2") (pinfunction "P$2_S2") (pintype "bidirectional"))
    )
    (net (code "52") (name "ADD_ACC1") (class "Default")
      (node (ref "B27") (pin "N2") (pinfunction "H_N2") (pintype "output"))
      (node (ref "D13") (pin "S2") (pinfunction "P$2_S2") (pintype "bidirectional"))
    )
    (net (code "53") (name "ADD_ACC2") (class "Default")
      (node (ref "B27") (pin "U2") (pinfunction "H_U2") (pintype "output"))
      (node (ref "D18") (pin "S2") (pinfunction "P$2_S2") (pintype "bidirectional"))
    )
    (net (code "54") (name "ADD_ACC3") (class "Default")
      (node (ref "B28") (pin "H2") (pinfunction "H_H2") (pintype "output"))
      (node (ref "D23") (pin "S2") (pinfunction "P$2_S2") (pintype "bidirectional"))
    )
    (net (code "55") (name "ADD_ACC4") (class "Default")
      (node (ref "B28") (pin "N2") (pinfunction "H_N2") (pintype "output"))
      (node (ref "D28") (pin "S2") (pinfunction "P$2_S2") (pintype "bidirectional"))
    )
    (net (code "56") (name "ADD_ACC5") (class "Default")
      (node (ref "A24") (pin "S2") (pinfunction "P$2_S2") (pintype "bidirectional"))
      (node (ref "B28") (pin "U2") (pinfunction "H_U2") (pintype "output"))
    )
    (net (code "57") (name "ADD_ACC6") (class "Default")
      (node (ref "A29") (pin "S2") (pinfunction "P$2_S2") (pintype "bidirectional"))
      (node (ref "B29") (pin "H2") (pinfunction "H_H2") (pintype "output"))
    )
    (net (code "58") (name "B32M") (class "Default")
      (node (ref "B32") (pin "M2") (pinfunction "I$1_M2") (pintype "input"))
      (node (ref "PDP-12/8I/8") (pin "2") (pinfunction "2_2") (pintype "passive"))
      (node (ref "PDP-12/8I/8") (pin "4") (pinfunction "4_4") (pintype "passive"))
      (node (ref "PDP-12/8I/8") (pin "6") (pinfunction "6_6") (pintype "passive"))
    )
    (net (code "59") (name "BMPX0") (class "Default")
      (node (ref "B09") (pin "M2") (pinfunction "P$1_M2") (pintype "passive"))
      (node (ref "B10") (pin "D2") (pinfunction "O$1_D2") (pintype "open_collector"))
      (node (ref "D08") (pin "P2") (pinfunction "P$2_P2") (pintype "bidirectional"))
    )
    (net (code "60") (name "BMPX1") (class "Default")
      (node (ref "B09") (pin "N2") (pinfunction "P$1_N2") (pintype "passive"))
      (node (ref "B10") (pin "F2") (pinfunction "O$1_F2") (pintype "open_collector"))
      (node (ref "D13") (pin "P2") (pinfunction "P$2_P2") (pintype "bidirectional"))
    )
    (net (code "61") (name "BMPX2") (class "Default")
      (node (ref "B09") (pin "P2") (pinfunction "P$1_P2") (pintype "passive"))
      (node (ref "B10") (pin "J2") (pinfunction "O$1_J2") (pintype "open_collector"))
      (node (ref "D18") (pin "P2") (pinfunction "P$2_P2") (pintype "bidirectional"))
    )
    (net (code "62") (name "BMPX3") (class "Default")
      (node (ref "B09") (pin "R2") (pinfunction "P$1_R2") (pintype "passive"))
      (node (ref "B10") (pin "L2") (pinfunction "O$1_L2") (pintype "open_collector"))
      (node (ref "D23") (pin "P2") (pinfunction "P$2_P2") (pintype "bidirectional"))
    )
    (net (code "63") (name "BMPX4") (class "Default")
      (node (ref "B09") (pin "S2") (pinfunction "P$1_S2") (pintype "passive"))
      (node (ref "B10") (pin "N2") (pinfunction "O$1_N2") (pintype "open_collector"))
      (node (ref "D28") (pin "P2") (pinfunction "P$2_P2") (pintype "bidirectional"))
    )
    (net (code "64") (name "BMPX5") (class "Default")
      (node (ref "A24") (pin "P2") (pinfunction "P$2_P2") (pintype "bidirectional"))
      (node (ref "B09") (pin "T2") (pinfunction "P$1_T2") (pintype "passive"))
      (node (ref "B10") (pin "R2") (pinfunction "O$1_R2") (pintype "open_collector"))
    )
    (net (code "65") (name "BMPX6") (class "Default")
      (node (ref "A29") (pin "P2") (pinfunction "P$2_P2") (pintype "bidirectional"))
      (node (ref "B09") (pin "V2") (pinfunction "P$1_V2") (pintype "passive"))
      (node (ref "B10") (pin "T2") (pinfunction "O$1_T2") (pintype "open_collector"))
    )
    (net (code "66") (name "BREAK") (class "Default")
      (node (ref "A08") (pin "P2") (pinfunction "P$2_P2") (pintype "bidirectional"))
      (node (ref "A18") (pin "K2") (pinfunction "I$1_K2") (pintype "input"))
      (node (ref "A19") (pin "D2") (pinfunction "PU0_D2") (pintype "input"))
      (node (ref "B06") (pin "D2") (pinfunction "I$1_D2") (pintype "input"))
      (node (ref "B06") (pin "K2") (pinfunction "I$1_K2") (pintype "input"))
      (node (ref "B06") (pin "R2") (pinfunction "I$1_R2") (pintype "input"))
      (node (ref "B08") (pin "D2") (pinfunction "I$1_D2") (pintype "input"))
      (node (ref "B08") (pin "K2") (pinfunction "I$1_K2") (pintype "input"))
      (node (ref "B08") (pin "R2") (pinfunction "I$1_R2") (pintype "input"))
      (node (ref "B23") (pin "R2") (pinfunction "I$1_R2") (pintype "input"))
    )
    (net (code "67") (name "BRK_REQ") (class "Default")
      (node (ref "A08") (pin "K2") (pinfunction "P$2_K2") (pintype "bidirectional"))
      (node (ref "B32") (pin "D2") (pinfunction "O$1_D2") (pintype "open_collector"))
    )
    (net (code "68") (name "BRK_REQ0") (class "Default")
      (node (ref "B02") (pin "E2") (pinfunction "I$1_E2") (pintype "input"))
      (node (ref "B09") (pin "D2") (pinfunction "P$1_D2") (pintype "passive"))
      (node (ref "B14") (pin "L2") (pinfunction "EN1_L2") (pintype "input"))
      (node (ref "B23") (pin "K2") (pinfunction "I$1_K2") (pintype "input"))
      (node (ref "D08") (pin "K2") (pinfunction "P$2_K2") (pintype "bidirectional"))
    )
    (net (code "69") (name "BRK_REQ1") (class "Default")
      (node (ref "B02") (pin "H2") (pinfunction "I$1_H2") (pintype "input"))
      (node (ref "B09") (pin "E2") (pinfunction "P$1_E2") (pintype "passive"))
      (node (ref "B16") (pin "L2") (pinfunction "EN1_L2") (pintype "input"))
      (node (ref "B23") (pin "L2") (pinfunction "I$2_L2") (pintype "input"))
      (node (ref "D13") (pin "K2") (pinfunction "P$2_K2") (pintype "bidirectional"))
    )
    (net (code "70") (name "BRK_REQ2") (class "Default")
      (node (ref "B02") (pin "K2") (pinfunction "I$1_K2") (pintype "input"))
      (node (ref "B09") (pin "F2") (pinfunction "P$1_F2") (pintype "passive"))
      (node (ref "B17") (pin "L2") (pinfunction "EN1_L2") (pintype "input"))
      (node (ref "B22") (pin "D2") (pinfunction "D_D2") (pintype "input"))
      (node (ref "D18") (pin "K2") (pinfunction "P$2_K2") (pintype "bidirectional"))
    )
    (net (code "71") (name "BRK_REQ3") (class "Default")
      (node (ref "B02") (pin "M2") (pinfunction "I$1_M2") (pintype "input"))
      (node (ref "B09") (pin "H2") (pinfunction "P$1_H2") (pintype "passive"))
      (node (ref "B18") (pin "L2") (pinfunction "EN1_L2") (pintype "input"))
      (node (ref "B22") (pin "E2") (pinfunction "E_E2") (pintype "input"))
      (node (ref "D23") (pin "K2") (pinfunction "P$2_K2") (pintype "bidirectional"))
    )
    (net (code "72") (name "BRK_REQ4") (class "Default")
      (node (ref "B02") (pin "P2") (pinfunction "I$1_P2") (pintype "input"))
      (node (ref "B09") (pin "J2") (pinfunction "P$1_J2") (pintype "passive"))
      (node (ref "B19") (pin "L2") (pinfunction "EN1_L2") (pintype "input"))
      (node (ref "B22") (pin "H2") (pinfunction "D_H2") (pintype "input"))
      (node (ref "D28") (pin "K2") (pinfunction "P$2_K2") (pintype "bidirectional"))
    )
    (net (code "73") (name "BRK_REQ5") (class "Default")
      (node (ref "A24") (pin "K2") (pinfunction "P$2_K2") (pintype "bidirectional"))
      (node (ref "B02") (pin "S2") (pinfunction "I$1_S2") (pintype "input"))
      (node (ref "B09") (pin "K2") (pinfunction "P$1_K2") (pintype "passive"))
      (node (ref "B20") (pin "L2") (pinfunction "EN1_L2") (pintype "input"))
      (node (ref "B22") (pin "J2") (pinfunction "E_J2") (pintype "input"))
    )
    (net (code "74") (name "BRK_REQ6") (class "Default")
      (node (ref "A29") (pin "K2") (pinfunction "P$2_K2") (pintype "bidirectional"))
      (node (ref "B02") (pin "U2") (pinfunction "I$1_U2") (pintype "input"))
      (node (ref "B09") (pin "L2") (pinfunction "P$1_L2") (pintype "passive"))
      (node (ref "B21") (pin "L2") (pinfunction "EN1_L2") (pintype "input"))
      (node (ref "B22") (pin "L2") (pinfunction "D_L2") (pintype "input"))
    )
    (net (code "75") (name "BRK_SYNC_CLK") (class "Default")
      (node (ref "A06") (pin "T2") (pinfunction "P$2_T2") (pintype "bidirectional"))
      (node (ref "B13") (pin "U2") (pinfunction "I$1_U2") (pintype "input"))
      (node (ref "D06") (pin "T2") (pinfunction "P$2_T2") (pintype "bidirectional"))
    )
    (net (code "76") (name "BT1B") (class "Default")
      (node (ref "A02") (pin "S2") (pinfunction "P$2_S2") (pintype "bidirectional"))
      (node (ref "D02") (pin "S2") (pinfunction "P$2_S2") (pintype "bidirectional"))
      (node (ref "PDP-12/8I/8") (pin "5") (pinfunction "5_5") (pintype "passive"))
    )
    (net (code "77") (name "B_ENABLE0") (class "Default")
      (node (ref "A12") (pin "E2") (pinfunction "I$1_E2") (pintype "input"))
      (node (ref "A16") (pin "D2") (pinfunction "I$1_D2") (pintype "input"))
      (node (ref "A20") (pin "S2") (pinfunction "P$2_S2") (pintype "bidirectional"))
      (node (ref "B04") (pin "E2") (pinfunction "I$1_E2") (pintype "input"))
      (node (ref "B06") (pin "E2") (pinfunction "I$2_E2") (pintype "input"))
      (node (ref "B14") (pin "T2") (pinfunction "1_T2") (pintype "open_collector"))
    )
    (net (code "78") (name "B_ENABLE1") (class "Default")
      (node (ref "A12") (pin "H2") (pinfunction "I$1_H2") (pintype "input"))
      (node (ref "A16") (pin "K2") (pinfunction "I$1_K2") (pintype "input"))
      (node (ref "A20") (pin "P2") (pinfunction "P$2_P2") (pintype "bidirectional"))
      (node (ref "B04") (pin "H2") (pinfunction "I$1_H2") (pintype "input"))
      (node (ref "B06") (pin "L2") (pinfunction "I$2_L2") (pintype "input"))
      (node (ref "B16") (pin "T2") (pinfunction "1_T2") (pintype "open_collector"))
    )
    (net (code "79") (name "B_ENABLE2") (class "Default")
      (node (ref "A12") (pin "K2") (pinfunction "I$1_K2") (pintype "input"))
      (node (ref "A16") (pin "R2") (pinfunction "I$1_R2") (pintype "input"))
      (node (ref "A20") (pin "M2") (pinfunction "P$2_M2") (pintype "bidirectional"))
      (node (ref "B04") (pin "K2") (pinfunction "I$1_K2") (pintype "input"))
      (node (ref "B06") (pin "S2") (pinfunction "I$2_S2") (pintype "input"))
      (node (ref "B17") (pin "T2") (pinfunction "1_T2") (pintype "open_collector"))
    )
    (net (code "80") (name "B_ENABLE3") (class "Default")
      (node (ref "A12") (pin "M2") (pinfunction "I$1_M2") (pintype "input"))
      (node (ref "A17") (pin "D2") (pinfunction "I$1_D2") (pintype "input"))
      (node (ref "A20") (pin "K2") (pinfunction "P$2_K2") (pintype "bidirectional"))
      (node (ref "B04") (pin "M2") (pinfunction "I$1_M2") (pintype "input"))
      (node (ref "B08") (pin "E2") (pinfunction "I$2_E2") (pintype "input"))
      (node (ref "B18") (pin "T2") (pinfunction "1_T2") (pintype "open_collector"))
    )
    (net (code "81") (name "B_ENABLE4") (class "Default")
      (node (ref "A12") (pin "P2") (pinfunction "I$1_P2") (pintype "input"))
      (node (ref "A17") (pin "K2") (pinfunction "I$1_K2") (pintype "input"))
      (node (ref "A20") (pin "H2") (pinfunction "P$2_H2") (pintype "bidirectional"))
      (node (ref "B04") (pin "P2") (pinfunction "I$1_P2") (pintype "input"))
      (node (ref "B08") (pin "L2") (pinfunction "I$2_L2") (pintype "input"))
      (node (ref "B19") (pin "T2") (pinfunction "1_T2") (pintype "open_collector"))
    )
    (net (code "82") (name "B_ENABLE5") (class "Default")
      (node (ref "A12") (pin "S2") (pinfunction "I$1_S2") (pintype "input"))
      (node (ref "A17") (pin "R2") (pinfunction "I$1_R2") (pintype "input"))
      (node (ref "A20") (pin "E2") (pinfunction "P$2_E2") (pintype "bidirectional"))
      (node (ref "B04") (pin "S2") (pinfunction "I$1_S2") (pintype "input"))
      (node (ref "B08") (pin "S2") (pinfunction "I$2_S2") (pintype "input"))
      (node (ref "B20") (pin "T2") (pinfunction "1_T2") (pintype "open_collector"))
    )
    (net (code "83") (name "B_ENABLE6") (class "Default")
      (node (ref "A12") (pin "U2") (pinfunction "I$1_U2") (pintype "input"))
      (node (ref "A18") (pin "D2") (pinfunction "I$1_D2") (pintype "input"))
      (node (ref "A20") (pin "D2") (pinfunction "P$2_D2") (pintype "bidirectional"))
      (node (ref "B04") (pin "U2") (pinfunction "I$1_U2") (pintype "input"))
      (node (ref "B21") (pin "T2") (pinfunction "1_T2") (pintype "open_collector"))
      (node (ref "B23") (pin "S2") (pinfunction "I$2_S2") (pintype "input"))
    )
    (net (code "84") (name "CYC_SEL") (class "Default")
      (node (ref "A10") (pin "K2") (pinfunction "P$2_K2") (pintype "bidirectional"))
      (node (ref "A19") (pin "L2") (pinfunction "EN1_L2") (pintype "input"))
      (node (ref "B15") (pin "R2") (pinfunction "O$1_R2") (pintype "open_collector"))
    )
    (net (code "85") (name "CYC_SEL0") (class "Default")
      (node (ref "C13") (pin "F2") (pinfunction "F_F2") (pintype "input"))
      (node (ref "D10") (pin "K2") (pinfunction "P$2_K2") (pintype "bidirectional"))
    )
    (net (code "86") (name "CYC_SEL1") (class "Default")
      (node (ref "C13") (pin "J2") (pinfunction "J_J2") (pintype "input"))
      (node (ref "D15") (pin "K2") (pinfunction "P$2_K2") (pintype "bidirectional"))
    )
    (net (code "87") (name "CYC_SEL2") (class "Default")
      (node (ref "C13") (pin "L2") (pinfunction "L_L2") (pintype "input"))
      (node (ref "D20") (pin "K2") (pinfunction "P$2_K2") (pintype "bidirectional"))
    )
    (net (code "88") (name "CYC_SEL3") (class "Default")
      (node (ref "C13") (pin "N2") (pinfunction "N_N2") (pintype "input"))
      (node (ref "D25") (pin "K2") (pinfunction "P$2_K2") (pintype "bidirectional"))
    )
    (net (code "89") (name "CYC_SEL4") (class "Default")
      (node (ref "C13") (pin "R2") (pinfunction "R_R2") (pintype "input"))
      (node (ref "D30") (pin "K2") (pinfunction "P$2_K2") (pintype "bidirectional"))
    )
    (net (code "90") (name "CYC_SEL5") (class "Default")
      (node (ref "A26") (pin "K2") (pinfunction "P$2_K2") (pintype "bidirectional"))
      (node (ref "C13") (pin "T2") (pinfunction "T_T2") (pintype "input"))
    )
    (net (code "91") (name "CYC_SEL6") (class "Default")
      (node (ref "A31") (pin "K2") (pinfunction "P$2_K2") (pintype "bidirectional"))
      (node (ref "C13") (pin "V2") (pinfunction "V_V2") (pintype "input"))
    )
    (net (code "92") (name "DA0") (class "Default")
      (node (ref "A07") (pin "D2") (pinfunction "P$2_D2") (pintype "bidirectional"))
      (node (ref "B07") (pin "D2") (pinfunction "O$1_D2") (pintype "open_collector"))
    )
    (net (code "93") (name "DA0-0") (class "Default")
      (node (ref "C01") (pin "F2") (pinfunction "F_F2") (pintype "input"))
      (node (ref "D07") (pin "D2") (pinfunction "P$2_D2") (pintype "bidirectional"))
    )
    (net (code "94") (name "DA0-1") (class "Default")
      (node (ref "C01") (pin "J2") (pinfunction "J_J2") (pintype "input"))
      (node (ref "D12") (pin "D2") (pinfunction "P$2_D2") (pintype "bidirectional"))
    )
    (net (code "95") (name "DA0-2") (class "Default")
      (node (ref "C01") (pin "L2") (pinfunction "L_L2") (pintype "input"))
      (node (ref "D17") (pin "D2") (pinfunction "P$2_D2") (pintype "bidirectional"))
    )
    (net (code "96") (name "DA0-3") (class "Default")
      (node (ref "C01") (pin "N2") (pinfunction "N_N2") (pintype "input"))
      (node (ref "D22") (pin "D2") (pinfunction "P$2_D2") (pintype "bidirectional"))
    )
    (net (code "97") (name "DA0-4") (class "Default")
      (node (ref "C01") (pin "R2") (pinfunction "R_R2") (pintype "input"))
      (node (ref "D27") (pin "D2") (pinfunction "P$2_D2") (pintype "bidirectional"))
    )
    (net (code "98") (name "DA0-5") (class "Default")
      (node (ref "A23") (pin "D2") (pinfunction "P$2_D2") (pintype "bidirectional"))
      (node (ref "C01") (pin "T2") (pinfunction "T_T2") (pintype "input"))
    )
    (net (code "99") (name "DA0-6") (class "Default")
      (node (ref "A28") (pin "D2") (pinfunction "P$2_D2") (pintype "bidirectional"))
      (node (ref "C01") (pin "V2") (pinfunction "V_V2") (pintype "input"))
    )
    (net (code "100") (name "DA1") (class "Default")
      (node (ref "A07") (pin "E2") (pinfunction "P$2_E2") (pintype "bidirectional"))
      (node (ref "B07") (pin "F2") (pinfunction "O$1_F2") (pintype "open_collector"))
    )
    (net (code "101") (name "DA1-0") (class "Default")
      (node (ref "C02") (pin "F2") (pinfunction "F_F2") (pintype "input"))
      (node (ref "D07") (pin "E2") (pinfunction "P$2_E2") (pintype "bidirectional"))
    )
    (net (code "102") (name "DA1-1") (class "Default")
      (node (ref "C02") (pin "J2") (pinfunction "J_J2") (pintype "input"))
      (node (ref "D12") (pin "E2") (pinfunction "P$2_E2") (pintype "bidirectional"))
    )
    (net (code "103") (name "DA1-2") (class "Default")
      (node (ref "C02") (pin "L2") (pinfunction "L_L2") (pintype "input"))
      (node (ref "D17") (pin "E2") (pinfunction "P$2_E2") (pintype "bidirectional"))
    )
    (net (code "104") (name "DA1-3") (class "Default")
      (node (ref "C02") (pin "N2") (pinfunction "N_N2") (pintype "input"))
      (node (ref "D22") (pin "E2") (pinfunction "P$2_E2") (pintype "bidirectional"))
    )
    (net (code "105") (name "DA1-4") (class "Default")
      (node (ref "C02") (pin "R2") (pinfunction "R_R2") (pintype "input"))
      (node (ref "D27") (pin "E2") (pinfunction "P$2_E2") (pintype "bidirectional"))
    )
    (net (code "106") (name "DA1-5") (class "Default")
      (node (ref "A23") (pin "E2") (pinfunction "P$2_E2") (pintype "bidirectional"))
      (node (ref "C02") (pin "T2") (pinfunction "T_T2") (pintype "input"))
    )
    (net (code "107") (name "DA1-6") (class "Default")
      (node (ref "A28") (pin "E2") (pinfunction "P$2_E2") (pintype "bidirectional"))
      (node (ref "C02") (pin "V2") (pinfunction "V_V2") (pintype "input"))
    )
    (net (code "108") (name "DA2") (class "Default")
      (node (ref "A07") (pin "H2") (pinfunction "P$2_H2") (pintype "bidirectional"))
      (node (ref "B07") (pin "J2") (pinfunction "O$1_J2") (pintype "open_collector"))
    )
    (net (code "109") (name "DA2-0") (class "Default")
      (node (ref "C03") (pin "F2") (pinfunction "F_F2") (pintype "input"))
      (node (ref "D07") (pin "H2") (pinfunction "P$2_H2") (pintype "bidirectional"))
    )
    (net (code "110") (name "DA2-1") (class "Default")
      (node (ref "C03") (pin "J2") (pinfunction "J_J2") (pintype "input"))
      (node (ref "D12") (pin "H2") (pinfunction "P$2_H2") (pintype "bidirectional"))
    )
    (net (code "111") (name "DA2-2") (class "Default")
      (node (ref "C03") (pin "L2") (pinfunction "L_L2") (pintype "input"))
      (node (ref "D17") (pin "H2") (pinfunction "P$2_H2") (pintype "bidirectional"))
    )
    (net (code "112") (name "DA2-3") (class "Default")
      (node (ref "C03") (pin "N2") (pinfunction "N_N2") (pintype "input"))
      (node (ref "D22") (pin "H2") (pinfunction "P$2_H2") (pintype "bidirectional"))
    )
    (net (code "113") (name "DA2-4") (class "Default")
      (node (ref "C03") (pin "R2") (pinfunction "R_R2") (pintype "input"))
      (node (ref "D27") (pin "H2") (pinfunction "P$2_H2") (pintype "bidirectional"))
    )
    (net (code "114") (name "DA2-5") (class "Default")
      (node (ref "A23") (pin "H2") (pinfunction "P$2_H2") (pintype "bidirectional"))
      (node (ref "C03") (pin "T2") (pinfunction "T_T2") (pintype "input"))
    )
    (net (code "115") (name "DA2-6") (class "Default")
      (node (ref "A28") (pin "H2") (pinfunction "P$2_H2") (pintype "bidirectional"))
      (node (ref "C03") (pin "V2") (pinfunction "V_V2") (pintype "input"))
    )
    (net (code "116") (name "DA3") (class "Default")
      (node (ref "A07") (pin "K2") (pinfunction "P$2_K2") (pintype "bidirectional"))
      (node (ref "B07") (pin "L2") (pinfunction "O$1_L2") (pintype "open_collector"))
    )
    (net (code "117") (name "DA3-0") (class "Default")
      (node (ref "C04") (pin "F2") (pinfunction "F_F2") (pintype "input"))
      (node (ref "D07") (pin "K2") (pinfunction "P$2_K2") (pintype "bidirectional"))
    )
    (net (code "118") (name "DA3-1") (class "Default")
      (node (ref "C04") (pin "J2") (pinfunction "J_J2") (pintype "input"))
      (node (ref "D12") (pin "K2") (pinfunction "P$2_K2") (pintype "bidirectional"))
    )
    (net (code "119") (name "DA3-2") (class "Default")
      (node (ref "C04") (pin "L2") (pinfunction "L_L2") (pintype "input"))
      (node (ref "D17") (pin "K2") (pinfunction "P$2_K2") (pintype "bidirectional"))
    )
    (net (code "120") (name "DA3-3") (class "Default")
      (node (ref "C04") (pin "N2") (pinfunction "N_N2") (pintype "input"))
      (node (ref "D22") (pin "K2") (pinfunction "P$2_K2") (pintype "bidirectional"))
    )
    (net (code "121") (name "DA3-4") (class "Default")
      (node (ref "C04") (pin "R2") (pinfunction "R_R2") (pintype "input"))
      (node (ref "D27") (pin "K2") (pinfunction "P$2_K2") (pintype "bidirectional"))
    )
    (net (code "122") (name "DA3-5") (class "Default")
      (node (ref "A23") (pin "K2") (pinfunction "P$2_K2") (pintype "bidirectional"))
      (node (ref "C04") (pin "T2") (pinfunction "T_T2") (pintype "input"))
    )
    (net (code "123") (name "DA3-6") (class "Default")
      (node (ref "A28") (pin "K2") (pinfunction "P$2_K2") (pintype "bidirectional"))
      (node (ref "C04") (pin "V2") (pinfunction "V_V2") (pintype "input"))
    )
    (net (code "124") (name "DA4") (class "Default")
      (node (ref "A07") (pin "M2") (pinfunction "P$2_M2") (pintype "bidirectional"))
      (node (ref "B07") (pin "N2") (pinfunction "O$1_N2") (pintype "open_collector"))
    )
    (net (code "125") (name "DA4-0") (class "Default")
      (node (ref "C05") (pin "F2") (pinfunction "F_F2") (pintype "input"))
      (node (ref "D07") (pin "M2") (pinfunction "P$2_M2") (pintype "bidirectional"))
    )
    (net (code "126") (name "DA4-1") (class "Default")
      (node (ref "C05") (pin "J2") (pinfunction "J_J2") (pintype "input"))
      (node (ref "D12") (pin "M2") (pinfunction "P$2_M2") (pintype "bidirectional"))
    )
    (net (code "127") (name "DA4-2") (class "Default")
      (node (ref "C05") (pin "L2") (pinfunction "L_L2") (pintype "input"))
      (node (ref "D17") (pin "M2") (pinfunction "P$2_M2") (pintype "bidirectional"))
    )
    (net (code "128") (name "DA4-3") (class "Default")
      (node (ref "C05") (pin "N2") (pinfunction "N_N2") (pintype "input"))
      (node (ref "D22") (pin "M2") (pinfunction "P$2_M2") (pintype "bidirectional"))
    )
    (net (code "129") (name "DA4-4") (class "Default")
      (node (ref "C05") (pin "R2") (pinfunction "R_R2") (pintype "input"))
      (node (ref "D27") (pin "M2") (pinfunction "P$2_M2") (pintype "bidirectional"))
    )
    (net (code "130") (name "DA4-5") (class "Default")
      (node (ref "A23") (pin "M2") (pinfunction "P$2_M2") (pintype "bidirectional"))
      (node (ref "C05") (pin "T2") (pinfunction "T_T2") (pintype "input"))
    )
    (net (code "131") (name "DA4-6") (class "Default")
      (node (ref "A28") (pin "M2") (pinfunction "P$2_M2") (pintype "bidirectional"))
      (node (ref "C05") (pin "V2") (pinfunction "V_V2") (pintype "input"))
    )
    (net (code "132") (name "DA5") (class "Default")
      (node (ref "A07") (pin "P2") (pinfunction "P$2_P2") (pintype "bidirectional"))
      (node (ref "B07") (pin "R2") (pinfunction "O$1_R2") (pintype "open_collector"))
    )
    (net (code "133") (name "DA5-0") (class "Default")
      (node (ref "C06") (pin "F2") (pinfunction "F_F2") (pintype "input"))
      (node (ref "D07") (pin "P2") (pinfunction "P$2_P2") (pintype "bidirectional"))
    )
    (net (code "134") (name "DA5-1") (class "Default")
      (node (ref "C06") (pin "J2") (pinfunction "J_J2") (pintype "input"))
      (node (ref "D12") (pin "P2") (pinfunction "P$2_P2") (pintype "bidirectional"))
    )
    (net (code "135") (name "DA5-2") (class "Default")
      (node (ref "C06") (pin "L2") (pinfunction "L_L2") (pintype "input"))
      (node (ref "D17") (pin "P2") (pinfunction "P$2_P2") (pintype "bidirectional"))
    )
    (net (code "136") (name "DA5-3") (class "Default")
      (node (ref "C06") (pin "N2") (pinfunction "N_N2") (pintype "input"))
      (node (ref "D22") (pin "P2") (pinfunction "P$2_P2") (pintype "bidirectional"))
    )
    (net (code "137") (name "DA5-4") (class "Default")
      (node (ref "C06") (pin "R2") (pinfunction "R_R2") (pintype "input"))
      (node (ref "D27") (pin "P2") (pinfunction "P$2_P2") (pintype "bidirectional"))
    )
    (net (code "138") (name "DA5-5") (class "Default")
      (node (ref "A23") (pin "P2") (pinfunction "P$2_P2") (pintype "bidirectional"))
      (node (ref "C06") (pin "T2") (pinfunction "T_T2") (pintype "input"))
    )
    (net (code "139") (name "DA5-6") (class "Default")
      (node (ref "A28") (pin "P2") (pinfunction "P$2_P2") (pintype "bidirectional"))
      (node (ref "C06") (pin "V2") (pinfunction "V_V2") (pintype "input"))
    )
    (net (code "140") (name "DA6") (class "Default")
      (node (ref "A07") (pin "S2") (pinfunction "P$2_S2") (pintype "bidirectional"))
      (node (ref "B07") (pin "T2") (pinfunction "O$1_T2") (pintype "open_collector"))
    )
    (net (code "141") (name "DA6-0") (class "Default")
      (node (ref "C07") (pin "F2") (pinfunction "F_F2") (pintype "input"))
      (node (ref "D07") (pin "S2") (pinfunction "P$2_S2") (pintype "bidirectional"))
    )
    (net (code "142") (name "DA6-1") (class "Default")
      (node (ref "C07") (pin "J2") (pinfunction "J_J2") (pintype "input"))
      (node (ref "D12") (pin "S2") (pinfunction "P$2_S2") (pintype "bidirectional"))
    )
    (net (code "143") (name "DA6-2") (class "Default")
      (node (ref "C07") (pin "L2") (pinfunction "L_L2") (pintype "input"))
      (node (ref "D17") (pin "S2") (pinfunction "P$2_S2") (pintype "bidirectional"))
    )
    (net (code "144") (name "DA6-3") (class "Default")
      (node (ref "C07") (pin "N2") (pinfunction "N_N2") (pintype "input"))
      (node (ref "D22") (pin "S2") (pinfunction "P$2_S2") (pintype "bidirectional"))
    )
    (net (code "145") (name "DA6-4") (class "Default")
      (node (ref "C07") (pin "R2") (pinfunction "R_R2") (pintype "input"))
      (node (ref "D27") (pin "S2") (pinfunction "P$2_S2") (pintype "bidirectional"))
    )
    (net (code "146") (name "DA6-5") (class "Default")
      (node (ref "A23") (pin "S2") (pinfunction "P$2_S2") (pintype "bidirectional"))
      (node (ref "C07") (pin "T2") (pinfunction "T_T2") (pintype "input"))
    )
    (net (code "147") (name "DA6-6") (class "Default")
      (node (ref "A28") (pin "S2") (pinfunction "P$2_S2") (pintype "bidirectional"))
      (node (ref "C07") (pin "V2") (pinfunction "V_V2") (pintype "input"))
    )
    (net (code "148") (name "DA7") (class "Default")
      (node (ref "A07") (pin "T2") (pinfunction "P$2_T2") (pintype "bidirectional"))
      (node (ref "B15") (pin "D2") (pinfunction "O$1_D2") (pintype "open_collector"))
    )
    (net (code "149") (name "DA7-0") (class "Default")
      (node (ref "C08") (pin "F2") (pinfunction "F_F2") (pintype "input"))
      (node (ref "D07") (pin "T2") (pinfunction "P$2_T2") (pintype "bidirectional"))
    )
    (net (code "150") (name "DA7-1") (class "Default")
      (node (ref "C08") (pin "J2") (pinfunction "J_J2") (pintype "input"))
      (node (ref "D12") (pin "T2") (pinfunction "P$2_T2") (pintype "bidirectional"))
    )
    (net (code "151") (name "DA7-2") (class "Default")
      (node (ref "C08") (pin "L2") (pinfunction "L_L2") (pintype "input"))
      (node (ref "D17") (pin "T2") (pinfunction "P$2_T2") (pintype "bidirectional"))
    )
    (net (code "152") (name "DA7-3") (class "Default")
      (node (ref "C08") (pin "N2") (pinfunction "N_N2") (pintype "input"))
      (node (ref "D22") (pin "T2") (pinfunction "P$2_T2") (pintype "bidirectional"))
    )
    (net (code "153") (name "DA7-4") (class "Default")
      (node (ref "C08") (pin "R2") (pinfunction "R_R2") (pintype "input"))
      (node (ref "D27") (pin "T2") (pinfunction "P$2_T2") (pintype "bidirectional"))
    )
    (net (code "154") (name "DA7-5") (class "Default")
      (node (ref "A23") (pin "T2") (pinfunction "P$2_T2") (pintype "bidirectional"))
      (node (ref "C08") (pin "T2") (pinfunction "T_T2") (pintype "input"))
    )
    (net (code "155") (name "DA7-6") (class "Default")
      (node (ref "A28") (pin "T2") (pinfunction "P$2_T2") (pintype "bidirectional"))
      (node (ref "C08") (pin "V2") (pinfunction "V_V2") (pintype "input"))
    )
    (net (code "156") (name "DA8") (class "Default")
      (node (ref "A07") (pin "V2") (pinfunction "P$2_V2") (pintype "bidirectional"))
      (node (ref "B15") (pin "F2") (pinfunction "O$1_F2") (pintype "open_collector"))
    )
    (net (code "157") (name "DA8-0") (class "Default")
      (node (ref "C09") (pin "F2") (pinfunction "F_F2") (pintype "input"))
      (node (ref "D07") (pin "V2") (pinfunction "P$2_V2") (pintype "bidirectional"))
    )
    (net (code "158") (name "DA8-1") (class "Default")
      (node (ref "C09") (pin "J2") (pinfunction "J_J2") (pintype "input"))
      (node (ref "D12") (pin "V2") (pinfunction "P$2_V2") (pintype "bidirectional"))
    )
    (net (code "159") (name "DA8-2") (class "Default")
      (node (ref "C09") (pin "L2") (pinfunction "L_L2") (pintype "input"))
      (node (ref "D17") (pin "V2") (pinfunction "P$2_V2") (pintype "bidirectional"))
    )
    (net (code "160") (name "DA8-3") (class "Default")
      (node (ref "C09") (pin "N2") (pinfunction "N_N2") (pintype "input"))
      (node (ref "D22") (pin "V2") (pinfunction "P$2_V2") (pintype "bidirectional"))
    )
    (net (code "161") (name "DA8-4") (class "Default")
      (node (ref "C09") (pin "R2") (pinfunction "R_R2") (pintype "input"))
      (node (ref "D27") (pin "V2") (pinfunction "P$2_V2") (pintype "bidirectional"))
    )
    (net (code "162") (name "DA8-5") (class "Default")
      (node (ref "A23") (pin "V2") (pinfunction "P$2_V2") (pintype "bidirectional"))
      (node (ref "C09") (pin "T2") (pinfunction "T_T2") (pintype "input"))
    )
    (net (code "163") (name "DA8-6") (class "Default")
      (node (ref "A28") (pin "V2") (pinfunction "P$2_V2") (pintype "bidirectional"))
      (node (ref "C09") (pin "V2") (pinfunction "V_V2") (pintype "input"))
    )
    (net (code "164") (name "DA9") (class "Default")
      (node (ref "A08") (pin "D2") (pinfunction "P$2_D2") (pintype "bidirectional"))
      (node (ref "B15") (pin "J2") (pinfunction "O$1_J2") (pintype "open_collector"))
    )
    (net (code "165") (name "DA9-0") (class "Default")
      (node (ref "C10") (pin "F2") (pinfunction "F_F2") (pintype "input"))
      (node (ref "D08") (pin "D2") (pinfunction "P$2_D2") (pintype "bidirectional"))
    )
    (net (code "166") (name "DA9-1") (class "Default")
      (node (ref "C10") (pin "J2") (pinfunction "J_J2") (pintype "input"))
      (node (ref "D13") (pin "D2") (pinfunction "P$2_D2") (pintype "bidirectional"))
    )
    (net (code "167") (name "DA9-2") (class "Default")
      (node (ref "C10") (pin "L2") (pinfunction "L_L2") (pintype "input"))
      (node (ref "D18") (pin "D2") (pinfunction "P$2_D2") (pintype "bidirectional"))
    )
    (net (code "168") (name "DA9-3") (class "Default")
      (node (ref "C10") (pin "N2") (pinfunction "N_N2") (pintype "input"))
      (node (ref "D23") (pin "D2") (pinfunction "P$2_D2") (pintype "bidirectional"))
    )
    (net (code "169") (name "DA9-4") (class "Default")
      (node (ref "C10") (pin "R2") (pinfunction "R_R2") (pintype "input"))
      (node (ref "D28") (pin "D2") (pinfunction "P$2_D2") (pintype "bidirectional"))
    )
    (net (code "170") (name "DA9-5") (class "Default")
      (node (ref "A24") (pin "D2") (pinfunction "P$2_D2") (pintype "bidirectional"))
      (node (ref "C10") (pin "T2") (pinfunction "T_T2") (pintype "input"))
    )
    (net (code "171") (name "DA9-6") (class "Default")
      (node (ref "A29") (pin "D2") (pinfunction "P$2_D2") (pintype "bidirectional"))
      (node (ref "C10") (pin "V2") (pinfunction "V_V2") (pintype "input"))
    )
    (net (code "172") (name "DA10") (class "Default")
      (node (ref "A08") (pin "E2") (pinfunction "P$2_E2") (pintype "bidirectional"))
      (node (ref "B15") (pin "L2") (pinfunction "O$1_L2") (pintype "open_collector"))
    )
    (net (code "173") (name "DA10-0") (class "Default")
      (node (ref "C11") (pin "F2") (pinfunction "F_F2") (pintype "input"))
      (node (ref "D08") (pin "E2") (pinfunction "P$2_E2") (pintype "bidirectional"))
    )
    (net (code "174") (name "DA10-1") (class "Default")
      (node (ref "C11") (pin "J2") (pinfunction "J_J2") (pintype "input"))
      (node (ref "D13") (pin "E2") (pinfunction "P$2_E2") (pintype "bidirectional"))
    )
    (net (code "175") (name "DA10-2") (class "Default")
      (node (ref "C11") (pin "L2") (pinfunction "L_L2") (pintype "input"))
      (node (ref "D18") (pin "E2") (pinfunction "P$2_E2") (pintype "bidirectional"))
    )
    (net (code "176") (name "DA10-3") (class "Default")
      (node (ref "C11") (pin "N2") (pinfunction "N_N2") (pintype "input"))
      (node (ref "D23") (pin "E2") (pinfunction "P$2_E2") (pintype "bidirectional"))
    )
    (net (code "177") (name "DA10-4") (class "Default")
      (node (ref "C11") (pin "R2") (pinfunction "R_R2") (pintype "input"))
      (node (ref "D28") (pin "E2") (pinfunction "P$2_E2") (pintype "bidirectional"))
    )
    (net (code "178") (name "DA10-5") (class "Default")
      (node (ref "A24") (pin "E2") (pinfunction "P$2_E2") (pintype "bidirectional"))
      (node (ref "C11") (pin "T2") (pinfunction "T_T2") (pintype "input"))
    )
    (net (code "179") (name "DA10-6") (class "Default")
      (node (ref "A29") (pin "E2") (pinfunction "P$2_E2") (pintype "bidirectional"))
      (node (ref "C11") (pin "V2") (pinfunction "V_V2") (pintype "input"))
    )
    (net (code "180") (name "DA11") (class "Default")
      (node (ref "A08") (pin "H2") (pinfunction "P$2_H2") (pintype "bidirectional"))
      (node (ref "B15") (pin "N2") (pinfunction "O$1_N2") (pintype "open_collector"))
    )
    (net (code "181") (name "DA11-0") (class "Default")
      (node (ref "C12") (pin "F2") (pinfunction "F_F2") (pintype "input"))
      (node (ref "D08") (pin "H2") (pinfunction "P$2_H2") (pintype "bidirectional"))
    )
    (net (code "182") (name "DA11-1") (class "Default")
      (node (ref "C12") (pin "J2") (pinfunction "J_J2") (pintype "input"))
      (node (ref "D13") (pin "H2") (pinfunction "P$2_H2") (pintype "bidirectional"))
    )
    (net (code "183") (name "DA11-2") (class "Default")
      (node (ref "C12") (pin "L2") (pinfunction "L_L2") (pintype "input"))
      (node (ref "D18") (pin "H2") (pinfunction "P$2_H2") (pintype "bidirectional"))
    )
    (net (code "184") (name "DA11-3") (class "Default")
      (node (ref "C12") (pin "N2") (pinfunction "N_N2") (pintype "input"))
      (node (ref "D23") (pin "H2") (pinfunction "P$2_H2") (pintype "bidirectional"))
    )
    (net (code "185") (name "DA11-4") (class "Default")
      (node (ref "C12") (pin "R2") (pinfunction "R_R2") (pintype "input"))
      (node (ref "D28") (pin "H2") (pinfunction "P$2_H2") (pintype "bidirectional"))
    )
    (net (code "186") (name "DA11-5") (class "Default")
      (node (ref "A24") (pin "H2") (pinfunction "P$2_H2") (pintype "bidirectional"))
      (node (ref "C12") (pin "T2") (pinfunction "T_T2") (pintype "input"))
    )
    (net (code "187") (name "DA11-6") (class "Default")
      (node (ref "A29") (pin "H2") (pinfunction "P$2_H2") (pintype "bidirectional"))
      (node (ref "C12") (pin "V2") (pinfunction "V_V2") (pintype "input"))
    )
    (net (code "188") (name "DAEX1") (class "Default")
      (node (ref "A11") (pin "D2") (pinfunction "P$2_D2") (pintype "bidirectional"))
      (node (ref "B25") (pin "F2") (pinfunction "O$1_F2") (pintype "open_collector"))
    )
    (net (code "189") (name "DAEX1-0") (class "Default")
      (node (ref "C16") (pin "F2") (pinfunction "F_F2") (pintype "input"))
      (node (ref "D11") (pin "D2") (pinfunction "P$2_D2") (pintype "bidirectional"))
    )
    (net (code "190") (name "DAEX1-1") (class "Default")
      (node (ref "C16") (pin "J2") (pinfunction "J_J2") (pintype "input"))
      (node (ref "D16") (pin "D2") (pinfunction "P$2_D2") (pintype "bidirectional"))
    )
    (net (code "191") (name "DAEX1-2") (class "Default")
      (node (ref "C16") (pin "L2") (pinfunction "L_L2") (pintype "input"))
      (node (ref "D21") (pin "D2") (pinfunction "P$2_D2") (pintype "bidirectional"))
    )
    (net (code "192") (name "DAEX1-3") (class "Default")
      (node (ref "C16") (pin "N2") (pinfunction "N_N2") (pintype "input"))
      (node (ref "D26") (pin "D2") (pinfunction "P$2_D2") (pintype "bidirectional"))
    )
    (net (code "193") (name "DAEX1-4") (class "Default")
      (node (ref "C16") (pin "R2") (pinfunction "R_R2") (pintype "input"))
      (node (ref "D31") (pin "D2") (pinfunction "P$2_D2") (pintype "bidirectional"))
    )
    (net (code "194") (name "DAEX1-5") (class "Default")
      (node (ref "A27") (pin "D2") (pinfunction "P$2_D2") (pintype "bidirectional"))
      (node (ref "C16") (pin "T2") (pinfunction "T_T2") (pintype "input"))
    )
    (net (code "195") (name "DAEX1-6") (class "Default")
      (node (ref "A32") (pin "D2") (pinfunction "P$2_D2") (pintype "bidirectional"))
      (node (ref "C16") (pin "V2") (pinfunction "V_V2") (pintype "input"))
    )
    (net (code "196") (name "DAEX2") (class "Default")
      (node (ref "A11") (pin "E2") (pinfunction "P$2_E2") (pintype "bidirectional"))
      (node (ref "B25") (pin "D2") (pinfunction "O$1_D2") (pintype "open_collector"))
    )
    (net (code "197") (name "DAEX2-0") (class "Default")
      (node (ref "C15") (pin "F2") (pinfunction "F_F2") (pintype "input"))
      (node (ref "D11") (pin "E2") (pinfunction "P$2_E2") (pintype "bidirectional"))
    )
    (net (code "198") (name "DAEX2-1") (class "Default")
      (node (ref "C15") (pin "J2") (pinfunction "J_J2") (pintype "input"))
      (node (ref "D16") (pin "E2") (pinfunction "P$2_E2") (pintype "bidirectional"))
    )
    (net (code "199") (name "DAEX2-2") (class "Default")
      (node (ref "C15") (pin "L2") (pinfunction "L_L2") (pintype "input"))
      (node (ref "D21") (pin "E2") (pinfunction "P$2_E2") (pintype "bidirectional"))
    )
    (net (code "200") (name "DAEX2-3") (class "Default")
      (node (ref "C15") (pin "N2") (pinfunction "N_N2") (pintype "input"))
      (node (ref "D26") (pin "E2") (pinfunction "P$2_E2") (pintype "bidirectional"))
    )
    (net (code "201") (name "DAEX2-4") (class "Default")
      (node (ref "C15") (pin "R2") (pinfunction "R_R2") (pintype "input"))
      (node (ref "D31") (pin "E2") (pinfunction "P$2_E2") (pintype "bidirectional"))
    )
    (net (code "202") (name "DAEX2-5") (class "Default")
      (node (ref "A27") (pin "E2") (pinfunction "P$2_E2") (pintype "bidirectional"))
      (node (ref "C15") (pin "T2") (pinfunction "T_T2") (pintype "input"))
    )
    (net (code "203") (name "DAEX2-6") (class "Default")
      (node (ref "A32") (pin "E2") (pinfunction "P$2_E2") (pintype "bidirectional"))
      (node (ref "C15") (pin "V2") (pinfunction "V_V2") (pintype "input"))
    )
    (net (code "204") (name "DAEX3") (class "Default")
      (node (ref "A11") (pin "H2") (pinfunction "P$2_H2") (pintype "bidirectional"))
      (node (ref "B15") (pin "T2") (pinfunction "O$1_T2") (pintype "open_collector"))
    )
    (net (code "205") (name "DAEX3-0") (class "Default")
      (node (ref "C14") (pin "F2") (pinfunction "F_F2") (pintype "input"))
      (node (ref "D11") (pin "H2") (pinfunction "P$2_H2") (pintype "bidirectional"))
    )
    (net (code "206") (name "DAEX3-1") (class "Default")
      (node (ref "C14") (pin "J2") (pinfunction "J_J2") (pintype "input"))
      (node (ref "D16") (pin "H2") (pinfunction "P$2_H2") (pintype "bidirectional"))
    )
    (net (code "207") (name "DAEX3-2") (class "Default")
      (node (ref "C14") (pin "L2") (pinfunction "L_L2") (pintype "input"))
      (node (ref "D21") (pin "H2") (pinfunction "P$2_H2") (pintype "bidirectional"))
    )
    (net (code "208") (name "DAEX3-3") (class "Default")
      (node (ref "C14") (pin "N2") (pinfunction "N_N2") (pintype "input"))
      (node (ref "D26") (pin "H2") (pinfunction "P$2_H2") (pintype "bidirectional"))
    )
    (net (code "209") (name "DAEX3-4") (class "Default")
      (node (ref "C14") (pin "R2") (pinfunction "R_R2") (pintype "input"))
      (node (ref "D31") (pin "H2") (pinfunction "P$2_H2") (pintype "bidirectional"))
    )
    (net (code "210") (name "DAEX3-5") (class "Default")
      (node (ref "A27") (pin "H2") (pinfunction "P$2_H2") (pintype "bidirectional"))
      (node (ref "C14") (pin "T2") (pinfunction "T_T2") (pintype "input"))
    )
    (net (code "211") (name "DAEX3-6") (class "Default")
      (node (ref "A32") (pin "H2") (pinfunction "P$2_H2") (pintype "bidirectional"))
      (node (ref "C14") (pin "V2") (pinfunction "V_V2") (pintype "input"))
    )
    (net (code "212") (name "DATA_OUT") (class "Default")
      (node (ref "A08") (pin "M2") (pinfunction "P$2_M2") (pintype "bidirectional"))
      (node (ref "B32") (pin "R2") (pinfunction "O$1_R2") (pintype "open_collector"))
    )
    (net (code "213") (name "DATA_OUT0") (class "Default")
      (node (ref "C30") (pin "F2") (pinfunction "F_F2") (pintype "input"))
      (node (ref "D08") (pin "M2") (pinfunction "P$2_M2") (pintype "bidirectional"))
    )
    (net (code "214") (name "DATA_OUT1") (class "Default")
      (node (ref "C30") (pin "J2") (pinfunction "J_J2") (pintype "input"))
      (node (ref "D13") (pin "M2") (pinfunction "P$2_M2") (pintype "bidirectional"))
    )
    (net (code "215") (name "DATA_OUT2") (class "Default")
      (node (ref "C30") (pin "L2") (pinfunction "L_L2") (pintype "input"))
      (node (ref "D18") (pin "M2") (pinfunction "P$2_M2") (pintype "bidirectional"))
    )
    (net (code "216") (name "DATA_OUT3") (class "Default")
      (node (ref "C30") (pin "N2") (pinfunction "N_N2") (pintype "input"))
      (node (ref "D23") (pin "M2") (pinfunction "P$2_M2") (pintype "bidirectional"))
    )
    (net (code "217") (name "DATA_OUT4") (class "Default")
      (node (ref "C30") (pin "R2") (pinfunction "R_R2") (pintype "input"))
      (node (ref "D28") (pin "M2") (pinfunction "P$2_M2") (pintype "bidirectional"))
    )
    (net (code "218") (name "DATA_OUT5") (class "Default")
      (node (ref "A24") (pin "M2") (pinfunction "P$2_M2") (pintype "bidirectional"))
      (node (ref "C30") (pin "T2") (pinfunction "T_T2") (pintype "input"))
    )
    (net (code "219") (name "DATA_OUT6") (class "Default")
      (node (ref "A29") (pin "M2") (pinfunction "P$2_M2") (pintype "bidirectional"))
      (node (ref "C30") (pin "V2") (pinfunction "V_V2") (pintype "input"))
    )
    (net (code "220") (name "DA_SEL_DEV0") (class "Default")
      (node (ref "A13") (pin "D2") (pinfunction "O$1_D2") (pintype "open_collector"))
      (node (ref "B05") (pin "D2") (pinfunction "O$1_D2") (pintype "open_collector"))
      (node (ref "C01") (pin "E2") (pinfunction "E_E2") (pintype "input"))
      (node (ref "C02") (pin "E2") (pinfunction "E_E2") (pintype "input"))
      (node (ref "C03") (pin "E2") (pinfunction "E_E2") (pintype "input"))
      (node (ref "C04") (pin "E2") (pinfunction "E_E2") (pintype "input"))
      (node (ref "C05") (pin "E2") (pinfunction "E_E2") (pintype "input"))
      (node (ref "C06") (pin "E2") (pinfunction "E_E2") (pintype "input"))
      (node (ref "C07") (pin "E2") (pinfunction "E_E2") (pintype "input"))
      (node (ref "C08") (pin "E2") (pinfunction "E_E2") (pintype "input"))
      (node (ref "C09") (pin "E2") (pinfunction "E_E2") (pintype "input"))
      (node (ref "C10") (pin "E2") (pinfunction "E_E2") (pintype "input"))
      (node (ref "C11") (pin "E2") (pinfunction "E_E2") (pintype "input"))
      (node (ref "C12") (pin "E2") (pinfunction "E_E2") (pintype "input"))
      (node (ref "C13") (pin "E2") (pinfunction "E_E2") (pintype "input"))
      (node (ref "C14") (pin "E2") (pinfunction "E_E2") (pintype "input"))
      (node (ref "C15") (pin "E2") (pinfunction "E_E2") (pintype "input"))
      (node (ref "C16") (pin "E2") (pinfunction "E_E2") (pintype "input"))
    )
    (net (code "221") (name "DA_SEL_DEV1") (class "Default")
      (node (ref "A13") (pin "F2") (pinfunction "O$1_F2") (pintype "open_collector"))
      (node (ref "B05") (pin "F2") (pinfunction "O$1_F2") (pintype "open_collector"))
      (node (ref "C01") (pin "H2") (pinfunction "H_H2") (pintype "input"))
      (node (ref "C02") (pin "H2") (pinfunction "H_H2") (pintype "input"))
      (node (ref "C03") (pin "H2") (pinfunction "H_H2") (pintype "input"))
      (node (ref "C04") (pin "H2") (pinfunction "H_H2") (pintype "input"))
      (node (ref "C05") (pin "H2") (pinfunction "H_H2") (pintype "input"))
      (node (ref "C06") (pin "H2") (pinfunction "H_H2") (pintype "input"))
      (node (ref "C07") (pin "H2") (pinfunction "H_H2") (pintype "input"))
      (node (ref "C08") (pin "H2") (pinfunction "H_H2") (pintype "input"))
      (node (ref "C09") (pin "H2") (pinfunction "H_H2") (pintype "input"))
      (node (ref "C10") (pin "H2") (pinfunction "H_H2") (pintype "input"))
      (node (ref "C11") (pin "H2") (pinfunction "H_H2") (pintype "input"))
      (node (ref "C12") (pin "H2") (pinfunction "H_H2") (pintype "input"))
      (node (ref "C13") (pin "H2") (pinfunction "H_H2") (pintype "input"))
      (node (ref "C14") (pin "H2") (pinfunction "H_H2") (pintype "input"))
      (node (ref "C15") (pin "H2") (pinfunction "H_H2") (pintype "input"))
      (node (ref "C16") (pin "H2") (pinfunction "H_H2") (pintype "input"))
    )
    (net (code "222") (name "DA_SEL_DEV2") (class "Default")
      (node (ref "A13") (pin "J2") (pinfunction "O$1_J2") (pintype "open_collector"))
      (node (ref "B05") (pin "J2") (pinfunction "O$1_J2") (pintype "open_collector"))
      (node (ref "C01") (pin "K2") (pinfunction "K_K2") (pintype "input"))
      (node (ref "C02") (pin "K2") (pinfunction "K_K2") (pintype "input"))
      (node (ref "C03") (pin "K2") (pinfunction "K_K2") (pintype "input"))
      (node (ref "C04") (pin "K2") (pinfunction "K_K2") (pintype "input"))
      (node (ref "C05") (pin "K2") (pinfunction "K_K2") (pintype "input"))
      (node (ref "C06") (pin "K2") (pinfunction "K_K2") (pintype "input"))
      (node (ref "C07") (pin "K2") (pinfunction "K_K2") (pintype "input"))
      (node (ref "C08") (pin "K2") (pinfunction "K_K2") (pintype "input"))
      (node (ref "C09") (pin "K2") (pinfunction "K_K2") (pintype "input"))
      (node (ref "C10") (pin "K2") (pinfunction "K_K2") (pintype "input"))
      (node (ref "C11") (pin "K2") (pinfunction "K_K2") (pintype "input"))
      (node (ref "C12") (pin "K2") (pinfunction "K_K2") (pintype "input"))
      (node (ref "C13") (pin "K2") (pinfunction "K_K2") (pintype "input"))
      (node (ref "C14") (pin "K2") (pinfunction "K_K2") (pintype "input"))
      (node (ref "C15") (pin "K2") (pinfunction "K_K2") (pintype "input"))
      (node (ref "C16") (pin "K2") (pinfunction "K_K2") (pintype "input"))
    )
    (net (code "223") (name "DA_SEL_DEV3") (class "Default")
      (node (ref "A13") (pin "L2") (pinfunction "O$1_L2") (pintype "open_collector"))
      (node (ref "B05") (pin "L2") (pinfunction "O$1_L2") (pintype "open_collector"))
      (node (ref "C01") (pin "M2") (pinfunction "M_M2") (pintype "input"))
      (node (ref "C02") (pin "M2") (pinfunction "M_M2") (pintype "input"))
      (node (ref "C03") (pin "M2") (pinfunction "M_M2") (pintype "input"))
      (node (ref "C04") (pin "M2") (pinfunction "M_M2") (pintype "input"))
      (node (ref "C05") (pin "M2") (pinfunction "M_M2") (pintype "input"))
      (node (ref "C06") (pin "M2") (pinfunction "M_M2") (pintype "input"))
      (node (ref "C07") (pin "M2") (pinfunction "M_M2") (pintype "input"))
      (node (ref "C08") (pin "M2") (pinfunction "M_M2") (pintype "input"))
      (node (ref "C09") (pin "M2") (pinfunction "M_M2") (pintype "input"))
      (node (ref "C10") (pin "M2") (pinfunction "M_M2") (pintype "input"))
      (node (ref "C11") (pin "M2") (pinfunction "M_M2") (pintype "input"))
      (node (ref "C12") (pin "M2") (pinfunction "M_M2") (pintype "input"))
      (node (ref "C13") (pin "M2") (pinfunction "M_M2") (pintype "input"))
      (node (ref "C14") (pin "M2") (pinfunction "M_M2") (pintype "input"))
      (node (ref "C15") (pin "M2") (pinfunction "M_M2") (pintype "input"))
      (node (ref "C16") (pin "M2") (pinfunction "M_M2") (pintype "input"))
    )
    (net (code "224") (name "DA_SEL_DEV4") (class "Default")
      (node (ref "A13") (pin "N2") (pinfunction "O$1_N2") (pintype "open_collector"))
      (node (ref "B05") (pin "N2") (pinfunction "O$1_N2") (pintype "open_collector"))
      (node (ref "C01") (pin "P2") (pinfunction "P_P2") (pintype "input"))
      (node (ref "C02") (pin "P2") (pinfunction "P_P2") (pintype "input"))
      (node (ref "C03") (pin "P2") (pinfunction "P_P2") (pintype "input"))
      (node (ref "C04") (pin "P2") (pinfunction "P_P2") (pintype "input"))
      (node (ref "C05") (pin "P2") (pinfunction "P_P2") (pintype "input"))
      (node (ref "C06") (pin "P2") (pinfunction "P_P2") (pintype "input"))
      (node (ref "C07") (pin "P2") (pinfunction "P_P2") (pintype "input"))
      (node (ref "C08") (pin "P2") (pinfunction "P_P2") (pintype "input"))
      (node (ref "C09") (pin "P2") (pinfunction "P_P2") (pintype "input"))
      (node (ref "C10") (pin "P2") (pinfunction "P_P2") (pintype "input"))
      (node (ref "C11") (pin "P2") (pinfunction "P_P2") (pintype "input"))
      (node (ref "C12") (pin "P2") (pinfunction "P_P2") (pintype "input"))
      (node (ref "C13") (pin "P2") (pinfunction "P_P2") (pintype "input"))
      (node (ref "C14") (pin "P2") (pinfunction "P_P2") (pintype "input"))
      (node (ref "C15") (pin "P2") (pinfunction "P_P2") (pintype "input"))
      (node (ref "C16") (pin "P2") (pinfunction "P_P2") (pintype "input"))
    )
    (net (code "225") (name "DA_SEL_DEV5") (class "Default")
      (node (ref "A13") (pin "R2") (pinfunction "O$1_R2") (pintype "open_collector"))
      (node (ref "B05") (pin "R2") (pinfunction "O$1_R2") (pintype "open_collector"))
      (node (ref "C01") (pin "S2") (pinfunction "S_S2") (pintype "input"))
      (node (ref "C02") (pin "S2") (pinfunction "S_S2") (pintype "input"))
      (node (ref "C03") (pin "S2") (pinfunction "S_S2") (pintype "input"))
      (node (ref "C04") (pin "S2") (pinfunction "S_S2") (pintype "input"))
      (node (ref "C05") (pin "S2") (pinfunction "S_S2") (pintype "input"))
      (node (ref "C06") (pin "S2") (pinfunction "S_S2") (pintype "input"))
      (node (ref "C07") (pin "S2") (pinfunction "S_S2") (pintype "input"))
      (node (ref "C08") (pin "S2") (pinfunction "S_S2") (pintype "input"))
      (node (ref "C09") (pin "S2") (pinfunction "S_S2") (pintype "input"))
      (node (ref "C10") (pin "S2") (pinfunction "S_S2") (pintype "input"))
      (node (ref "C11") (pin "S2") (pinfunction "S_S2") (pintype "input"))
      (node (ref "C12") (pin "S2") (pinfunction "S_S2") (pintype "input"))
      (node (ref "C13") (pin "S2") (pinfunction "S_S2") (pintype "input"))
      (node (ref "C14") (pin "S2") (pinfunction "S_S2") (pintype "input"))
      (node (ref "C15") (pin "S2") (pinfunction "S_S2") (pintype "input"))
      (node (ref "C16") (pin "S2") (pinfunction "S_S2") (pintype "input"))
    )
    (net (code "226") (name "DA_SEL_DEV6") (class "Default")
      (node (ref "A13") (pin "T2") (pinfunction "O$1_T2") (pintype "open_collector"))
      (node (ref "B05") (pin "T2") (pinfunction "O$1_T2") (pintype "open_collector"))
      (node (ref "C01") (pin "U2") (pinfunction "U_U2") (pintype "input"))
      (node (ref "C02") (pin "U2") (pinfunction "U_U2") (pintype "input"))
      (node (ref "C03") (pin "U2") (pinfunction "U_U2") (pintype "input"))
      (node (ref "C04") (pin "U2") (pinfunction "U_U2") (pintype "input"))
      (node (ref "C05") (pin "U2") (pinfunction "U_U2") (pintype "input"))
      (node (ref "C06") (pin "U2") (pinfunction "U_U2") (pintype "input"))
      (node (ref "C07") (pin "U2") (pinfunction "U_U2") (pintype "input"))
      (node (ref "C08") (pin "U2") (pinfunction "U_U2") (pintype "input"))
      (node (ref "C09") (pin "U2") (pinfunction "U_U2") (pintype "input"))
      (node (ref "C10") (pin "U2") (pinfunction "U_U2") (pintype "input"))
      (node (ref "C11") (pin "U2") (pinfunction "U_U2") (pintype "input"))
      (node (ref "C12") (pin "U2") (pinfunction "U_U2") (pintype "input"))
      (node (ref "C13") (pin "U2") (pinfunction "U_U2") (pintype "input"))
      (node (ref "C14") (pin "U2") (pinfunction "U_U2") (pintype "input"))
      (node (ref "C15") (pin "U2") (pinfunction "U_U2") (pintype "input"))
      (node (ref "C16") (pin "U2") (pinfunction "U_U2") (pintype "input"))
    )
    (net (code "227") (name "DB0") (class "Default")
      (node (ref "A09") (pin "D2") (pinfunction "P$2_D2") (pintype "bidirectional"))
      (node (ref "B25") (pin "J2") (pinfunction "O$1_J2") (pintype "open_collector"))
    )
    (net (code "228") (name "DB0-0") (class "Default")
      (node (ref "C17") (pin "F2") (pinfunction "F_F2") (pintype "input"))
      (node (ref "D09") (pin "D2") (pinfunction "P$2_D2") (pintype "bidirectional"))
    )
    (net (code "229") (name "DB0-1") (class "Default")
      (node (ref "C17") (pin "J2") (pinfunction "J_J2") (pintype "input"))
      (node (ref "D14") (pin "D2") (pinfunction "P$2_D2") (pintype "bidirectional"))
    )
    (net (code "230") (name "DB0-2") (class "Default")
      (node (ref "C17") (pin "L2") (pinfunction "L_L2") (pintype "input"))
      (node (ref "D19") (pin "D2") (pinfunction "P$2_D2") (pintype "bidirectional"))
    )
    (net (code "231") (name "DB0-3") (class "Default")
      (node (ref "C17") (pin "N2") (pinfunction "N_N2") (pintype "input"))
      (node (ref "D24") (pin "D2") (pinfunction "P$2_D2") (pintype "bidirectional"))
    )
    (net (code "232") (name "DB0-4") (class "Default")
      (node (ref "C17") (pin "R2") (pinfunction "R_R2") (pintype "input"))
      (node (ref "D29") (pin "D2") (pinfunction "P$2_D2") (pintype "bidirectional"))
    )
    (net (code "233") (name "DB0-5") (class "Default")
      (node (ref "A25") (pin "D2") (pinfunction "P$2_D2") (pintype "bidirectional"))
      (node (ref "C17") (pin "T2") (pinfunction "T_T2") (pintype "input"))
    )
    (net (code "234") (name "DB0-6") (class "Default")
      (node (ref "A30") (pin "D2") (pinfunction "P$2_D2") (pintype "bidirectional"))
      (node (ref "C17") (pin "V2") (pinfunction "V_V2") (pintype "input"))
    )
    (net (code "235") (name "DB1") (class "Default")
      (node (ref "A09") (pin "E2") (pinfunction "P$2_E2") (pintype "bidirectional"))
      (node (ref "B25") (pin "L2") (pinfunction "O$1_L2") (pintype "open_collector"))
    )
    (net (code "236") (name "DB1-0") (class "Default")
      (node (ref "C18") (pin "F2") (pinfunction "F_F2") (pintype "input"))
      (node (ref "D09") (pin "E2") (pinfunction "P$2_E2") (pintype "bidirectional"))
    )
    (net (code "237") (name "DB1-1") (class "Default")
      (node (ref "C18") (pin "J2") (pinfunction "J_J2") (pintype "input"))
      (node (ref "D14") (pin "E2") (pinfunction "P$2_E2") (pintype "bidirectional"))
    )
    (net (code "238") (name "DB1-2") (class "Default")
      (node (ref "C18") (pin "L2") (pinfunction "L_L2") (pintype "input"))
      (node (ref "D19") (pin "E2") (pinfunction "P$2_E2") (pintype "bidirectional"))
    )
    (net (code "239") (name "DB1-3") (class "Default")
      (node (ref "C18") (pin "N2") (pinfunction "N_N2") (pintype "input"))
      (node (ref "D24") (pin "E2") (pinfunction "P$2_E2") (pintype "bidirectional"))
    )
    (net (code "240") (name "DB1-4") (class "Default")
      (node (ref "C18") (pin "R2") (pinfunction "R_R2") (pintype "input"))
      (node (ref "D29") (pin "E2") (pinfunction "P$2_E2") (pintype "bidirectional"))
    )
    (net (code "241") (name "DB1-5") (class "Default")
      (node (ref "A25") (pin "E2") (pinfunction "P$2_E2") (pintype "bidirectional"))
      (node (ref "C18") (pin "T2") (pinfunction "T_T2") (pintype "input"))
    )
    (net (code "242") (name "DB1-6") (class "Default")
      (node (ref "A30") (pin "E2") (pinfunction "P$2_E2") (pintype "bidirectional"))
      (node (ref "C18") (pin "V2") (pinfunction "V_V2") (pintype "input"))
    )
    (net (code "243") (name "DB2") (class "Default")
      (node (ref "A09") (pin "H2") (pinfunction "P$2_H2") (pintype "bidirectional"))
      (node (ref "B25") (pin "N2") (pinfunction "O$1_N2") (pintype "open_collector"))
    )
    (net (code "244") (name "DB2-0") (class "Default")
      (node (ref "C19") (pin "F2") (pinfunction "F_F2") (pintype "input"))
      (node (ref "D09") (pin "H2") (pinfunction "P$2_H2") (pintype "bidirectional"))
    )
    (net (code "245") (name "DB2-1") (class "Default")
      (node (ref "C19") (pin "J2") (pinfunction "J_J2") (pintype "input"))
      (node (ref "D14") (pin "H2") (pinfunction "P$2_H2") (pintype "bidirectional"))
    )
    (net (code "246") (name "DB2-2") (class "Default")
      (node (ref "C19") (pin "L2") (pinfunction "L_L2") (pintype "input"))
      (node (ref "D19") (pin "H2") (pinfunction "P$2_H2") (pintype "bidirectional"))
    )
    (net (code "247") (name "DB2-3") (class "Default")
      (node (ref "C19") (pin "N2") (pinfunction "N_N2") (pintype "input"))
      (node (ref "D24") (pin "H2") (pinfunction "P$2_H2") (pintype "bidirectional"))
    )
    (net (code "248") (name "DB2-4") (class "Default")
      (node (ref "C19") (pin "R2") (pinfunction "R_R2") (pintype "input"))
      (node (ref "D29") (pin "H2") (pinfunction "P$2_H2") (pintype "bidirectional"))
    )
    (net (code "249") (name "DB2-5") (class "Default")
      (node (ref "A25") (pin "H2") (pinfunction "P$2_H2") (pintype "bidirectional"))
      (node (ref "C19") (pin "T2") (pinfunction "T_T2") (pintype "input"))
    )
    (net (code "250") (name "DB2-6") (class "Default")
      (node (ref "A30") (pin "H2") (pinfunction "P$2_H2") (pintype "bidirectional"))
      (node (ref "C19") (pin "V2") (pinfunction "V_V2") (pintype "input"))
    )
    (net (code "251") (name "DB3") (class "Default")
      (node (ref "A09") (pin "K2") (pinfunction "P$2_K2") (pintype "bidirectional"))
      (node (ref "B25") (pin "R2") (pinfunction "O$1_R2") (pintype "open_collector"))
    )
    (net (code "252") (name "DB3-0") (class "Default")
      (node (ref "C20") (pin "F2") (pinfunction "F_F2") (pintype "input"))
      (node (ref "D09") (pin "K2") (pinfunction "P$2_K2") (pintype "bidirectional"))
    )
    (net (code "253") (name "DB3-1") (class "Default")
      (node (ref "C20") (pin "J2") (pinfunction "J_J2") (pintype "input"))
      (node (ref "D14") (pin "K2") (pinfunction "P$2_K2") (pintype "bidirectional"))
    )
    (net (code "254") (name "DB3-2") (class "Default")
      (node (ref "C20") (pin "L2") (pinfunction "L_L2") (pintype "input"))
      (node (ref "D19") (pin "K2") (pinfunction "P$2_K2") (pintype "bidirectional"))
    )
    (net (code "255") (name "DB3-3") (class "Default")
      (node (ref "C20") (pin "N2") (pinfunction "N_N2") (pintype "input"))
      (node (ref "D24") (pin "K2") (pinfunction "P$2_K2") (pintype "bidirectional"))
    )
    (net (code "256") (name "DB3-4") (class "Default")
      (node (ref "C20") (pin "R2") (pinfunction "R_R2") (pintype "input"))
      (node (ref "D29") (pin "K2") (pinfunction "P$2_K2") (pintype "bidirectional"))
    )
    (net (code "257") (name "DB3-5") (class "Default")
      (node (ref "A25") (pin "K2") (pinfunction "P$2_K2") (pintype "bidirectional"))
      (node (ref "C20") (pin "T2") (pinfunction "T_T2") (pintype "input"))
    )
    (net (code "258") (name "DB3-6") (class "Default")
      (node (ref "A30") (pin "K2") (pinfunction "P$2_K2") (pintype "bidirectional"))
      (node (ref "C20") (pin "V2") (pinfunction "V_V2") (pintype "input"))
    )
    (net (code "259") (name "DB4") (class "Default")
      (node (ref "A09") (pin "M2") (pinfunction "P$2_M2") (pintype "bidirectional"))
      (node (ref "B25") (pin "T2") (pinfunction "O$1_T2") (pintype "open_collector"))
    )
    (net (code "260") (name "DB4-0") (class "Default")
      (node (ref "C21") (pin "F2") (pinfunction "F_F2") (pintype "input"))
      (node (ref "D09") (pin "M2") (pinfunction "P$2_M2") (pintype "bidirectional"))
    )
    (net (code "261") (name "DB4-1") (class "Default")
      (node (ref "C21") (pin "J2") (pinfunction "J_J2") (pintype "input"))
      (node (ref "D14") (pin "M2") (pinfunction "P$2_M2") (pintype "bidirectional"))
    )
    (net (code "262") (name "DB4-2") (class "Default")
      (node (ref "C21") (pin "L2") (pinfunction "L_L2") (pintype "input"))
      (node (ref "D19") (pin "M2") (pinfunction "P$2_M2") (pintype "bidirectional"))
    )
    (net (code "263") (name "DB4-3") (class "Default")
      (node (ref "C21") (pin "N2") (pinfunction "N_N2") (pintype "input"))
      (node (ref "D24") (pin "M2") (pinfunction "P$2_M2") (pintype "bidirectional"))
    )
    (net (code "264") (name "DB4-4") (class "Default")
      (node (ref "C21") (pin "R2") (pinfunction "R_R2") (pintype "input"))
      (node (ref "D29") (pin "M2") (pinfunction "P$2_M2") (pintype "bidirectional"))
    )
    (net (code "265") (name "DB4-5") (class "Default")
      (node (ref "A25") (pin "M2") (pinfunction "P$2_M2") (pintype "bidirectional"))
      (node (ref "C21") (pin "T2") (pinfunction "T_T2") (pintype "input"))
    )
    (net (code "266") (name "DB4-6") (class "Default")
      (node (ref "A30") (pin "M2") (pinfunction "P$2_M2") (pintype "bidirectional"))
      (node (ref "C21") (pin "V2") (pinfunction "V_V2") (pintype "input"))
    )
    (net (code "267") (name "DB5") (class "Default")
      (node (ref "A09") (pin "P2") (pinfunction "P$2_P2") (pintype "bidirectional"))
      (node (ref "B26") (pin "D2") (pinfunction "O$1_D2") (pintype "open_collector"))
    )
    (net (code "268") (name "DB5-0") (class "Default")
      (node (ref "C22") (pin "F2") (pinfunction "F_F2") (pintype "input"))
      (node (ref "D09") (pin "P2") (pinfunction "P$2_P2") (pintype "bidirectional"))
    )
    (net (code "269") (name "DB5-1") (class "Default")
      (node (ref "C22") (pin "J2") (pinfunction "J_J2") (pintype "input"))
      (node (ref "D14") (pin "P2") (pinfunction "P$2_P2") (pintype "bidirectional"))
    )
    (net (code "270") (name "DB5-2") (class "Default")
      (node (ref "C22") (pin "L2") (pinfunction "L_L2") (pintype "input"))
      (node (ref "D19") (pin "P2") (pinfunction "P$2_P2") (pintype "bidirectional"))
    )
    (net (code "271") (name "DB5-3") (class "Default")
      (node (ref "C22") (pin "N2") (pinfunction "N_N2") (pintype "input"))
      (node (ref "D24") (pin "P2") (pinfunction "P$2_P2") (pintype "bidirectional"))
    )
    (net (code "272") (name "DB5-4") (class "Default")
      (node (ref "C22") (pin "R2") (pinfunction "R_R2") (pintype "input"))
      (node (ref "D29") (pin "P2") (pinfunction "P$2_P2") (pintype "bidirectional"))
    )
    (net (code "273") (name "DB5-5") (class "Default")
      (node (ref "A25") (pin "P2") (pinfunction "P$2_P2") (pintype "bidirectional"))
      (node (ref "C22") (pin "T2") (pinfunction "T_T2") (pintype "input"))
    )
    (net (code "274") (name "DB5-6") (class "Default")
      (node (ref "A30") (pin "P2") (pinfunction "P$2_P2") (pintype "bidirectional"))
      (node (ref "C22") (pin "V2") (pinfunction "V_V2") (pintype "input"))
    )
    (net (code "275") (name "DB6") (class "Default")
      (node (ref "A09") (pin "S2") (pinfunction "P$2_S2") (pintype "bidirectional"))
      (node (ref "B26") (pin "F2") (pinfunction "O$1_F2") (pintype "open_collector"))
    )
    (net (code "276") (name "DB6-0") (class "Default")
      (node (ref "C23") (pin "F2") (pinfunction "F_F2") (pintype "input"))
      (node (ref "D09") (pin "S2") (pinfunction "P$2_S2") (pintype "bidirectional"))
    )
    (net (code "277") (name "DB6-1") (class "Default")
      (node (ref "C23") (pin "J2") (pinfunction "J_J2") (pintype "input"))
      (node (ref "D14") (pin "S2") (pinfunction "P$2_S2") (pintype "bidirectional"))
    )
    (net (code "278") (name "DB6-2") (class "Default")
      (node (ref "C23") (pin "L2") (pinfunction "L_L2") (pintype "input"))
      (node (ref "D19") (pin "S2") (pinfunction "P$2_S2") (pintype "bidirectional"))
    )
    (net (code "279") (name "DB6-3") (class "Default")
      (node (ref "C23") (pin "N2") (pinfunction "N_N2") (pintype "input"))
      (node (ref "D24") (pin "S2") (pinfunction "P$2_S2") (pintype "bidirectional"))
    )
    (net (code "280") (name "DB6-4") (class "Default")
      (node (ref "C23") (pin "R2") (pinfunction "R_R2") (pintype "input"))
      (node (ref "D29") (pin "S2") (pinfunction "P$2_S2") (pintype "bidirectional"))
    )
    (net (code "281") (name "DB6-5") (class "Default")
      (node (ref "A25") (pin "S2") (pinfunction "P$2_S2") (pintype "bidirectional"))
      (node (ref "C23") (pin "T2") (pinfunction "T_T2") (pintype "input"))
    )
    (net (code "282") (name "DB6-6") (class "Default")
      (node (ref "A30") (pin "S2") (pinfunction "P$2_S2") (pintype "bidirectional"))
      (node (ref "C23") (pin "V2") (pinfunction "V_V2") (pintype "input"))
    )
    (net (code "283") (name "DB7") (class "Default")
      (node (ref "A09") (pin "T2") (pinfunction "P$2_T2") (pintype "bidirectional"))
      (node (ref "B26") (pin "J2") (pinfunction "O$1_J2") (pintype "open_collector"))
    )
    (net (code "284") (name "DB7-0") (class "Default")
      (node (ref "C24") (pin "F2") (pinfunction "F_F2") (pintype "input"))
      (node (ref "D09") (pin "T2") (pinfunction "P$2_T2") (pintype "bidirectional"))
    )
    (net (code "285") (name "DB7-1") (class "Default")
      (node (ref "C24") (pin "J2") (pinfunction "J_J2") (pintype "input"))
      (node (ref "D14") (pin "T2") (pinfunction "P$2_T2") (pintype "bidirectional"))
    )
    (net (code "286") (name "DB7-2") (class "Default")
      (node (ref "C24") (pin "L2") (pinfunction "L_L2") (pintype "input"))
      (node (ref "D19") (pin "T2") (pinfunction "P$2_T2") (pintype "bidirectional"))
    )
    (net (code "287") (name "DB7-3") (class "Default")
      (node (ref "C24") (pin "N2") (pinfunction "N_N2") (pintype "input"))
      (node (ref "D24") (pin "T2") (pinfunction "P$2_T2") (pintype "bidirectional"))
    )
    (net (code "288") (name "DB7-4") (class "Default")
      (node (ref "C24") (pin "R2") (pinfunction "R_R2") (pintype "input"))
      (node (ref "D29") (pin "T2") (pinfunction "P$2_T2") (pintype "bidirectional"))
    )
    (net (code "289") (name "DB7-5") (class "Default")
      (node (ref "A25") (pin "T2") (pinfunction "P$2_T2") (pintype "bidirectional"))
      (node (ref "C24") (pin "T2") (pinfunction "T_T2") (pintype "input"))
    )
    (net (code "290") (name "DB7-6") (class "Default")
      (node (ref "A30") (pin "T2") (pinfunction "P$2_T2") (pintype "bidirectional"))
      (node (ref "C24") (pin "V2") (pinfunction "V_V2") (pintype "input"))
    )
    (net (code "291") (name "DB8") (class "Default")
      (node (ref "A09") (pin "V2") (pinfunction "P$2_V2") (pintype "bidirectional"))
      (node (ref "B26") (pin "L2") (pinfunction "O$1_L2") (pintype "open_collector"))
    )
    (net (code "292") (name "DB8-0") (class "Default")
      (node (ref "C25") (pin "F2") (pinfunction "F_F2") (pintype "input"))
      (node (ref "D09") (pin "V2") (pinfunction "P$2_V2") (pintype "bidirectional"))
    )
    (net (code "293") (name "DB8-1") (class "Default")
      (node (ref "C25") (pin "J2") (pinfunction "J_J2") (pintype "input"))
      (node (ref "D14") (pin "V2") (pinfunction "P$2_V2") (pintype "bidirectional"))
    )
    (net (code "294") (name "DB8-2") (class "Default")
      (node (ref "C25") (pin "L2") (pinfunction "L_L2") (pintype "input"))
      (node (ref "D19") (pin "V2") (pinfunction "P$2_V2") (pintype "bidirectional"))
    )
    (net (code "295") (name "DB8-3") (class "Default")
      (node (ref "C25") (pin "N2") (pinfunction "N_N2") (pintype "input"))
      (node (ref "D24") (pin "V2") (pinfunction "P$2_V2") (pintype "bidirectional"))
    )
    (net (code "296") (name "DB8-4") (class "Default")
      (node (ref "C25") (pin "R2") (pinfunction "R_R2") (pintype "input"))
      (node (ref "D29") (pin "V2") (pinfunction "P$2_V2") (pintype "bidirectional"))
    )
    (net (code "297") (name "DB8-5") (class "Default")
      (node (ref "A25") (pin "V2") (pinfunction "P$2_V2") (pintype "bidirectional"))
      (node (ref "C25") (pin "T2") (pinfunction "T_T2") (pintype "input"))
    )
    (net (code "298") (name "DB8-6") (class "Default")
      (node (ref "A30") (pin "V2") (pinfunction "P$2_V2") (pintype "bidirectional"))
      (node (ref "C25") (pin "V2") (pinfunction "V_V2") (pintype "input"))
    )
    (net (code "299") (name "DB9") (class "Default")
      (node (ref "A10") (pin "D2") (pinfunction "P$2_D2") (pintype "bidirectional"))
      (node (ref "B26") (pin "N2") (pinfunction "O$1_N2") (pintype "open_collector"))
    )
    (net (code "300") (name "DB9-0") (class "Default")
      (node (ref "C26") (pin "F2") (pinfunction "F_F2") (pintype "input"))
      (node (ref "D10") (pin "D2") (pinfunction "P$2_D2") (pintype "bidirectional"))
    )
    (net (code "301") (name "DB9-1") (class "Default")
      (node (ref "C26") (pin "J2") (pinfunction "J_J2") (pintype "input"))
      (node (ref "D15") (pin "D2") (pinfunction "P$2_D2") (pintype "bidirectional"))
    )
    (net (code "302") (name "DB9-2") (class "Default")
      (node (ref "C26") (pin "L2") (pinfunction "L_L2") (pintype "input"))
      (node (ref "D20") (pin "D2") (pinfunction "P$2_D2") (pintype "bidirectional"))
    )
    (net (code "303") (name "DB9-3") (class "Default")
      (node (ref "C26") (pin "N2") (pinfunction "N_N2") (pintype "input"))
      (node (ref "D25") (pin "D2") (pinfunction "P$2_D2") (pintype "bidirectional"))
    )
    (net (code "304") (name "DB9-4") (class "Default")
      (node (ref "C26") (pin "R2") (pinfunction "R_R2") (pintype "input"))
      (node (ref "D30") (pin "D2") (pinfunction "P$2_D2") (pintype "bidirectional"))
    )
    (net (code "305") (name "DB9-5") (class "Default")
      (node (ref "A26") (pin "D2") (pinfunction "P$2_D2") (pintype "bidirectional"))
      (node (ref "C26") (pin "T2") (pinfunction "T_T2") (pintype "input"))
    )
    (net (code "306") (name "DB9-6") (class "Default")
      (node (ref "A31") (pin "D2") (pinfunction "P$2_D2") (pintype "bidirectional"))
      (node (ref "C26") (pin "V2") (pinfunction "V_V2") (pintype "input"))
    )
    (net (code "307") (name "DB10") (class "Default")
      (node (ref "A10") (pin "E2") (pinfunction "P$2_E2") (pintype "bidirectional"))
      (node (ref "B26") (pin "R2") (pinfunction "O$1_R2") (pintype "open_collector"))
    )
    (net (code "308") (name "DB10-0") (class "Default")
      (node (ref "C27") (pin "F2") (pinfunction "F_F2") (pintype "input"))
      (node (ref "D10") (pin "E2") (pinfunction "P$2_E2") (pintype "bidirectional"))
    )
    (net (code "309") (name "DB10-1") (class "Default")
      (node (ref "C27") (pin "J2") (pinfunction "J_J2") (pintype "input"))
      (node (ref "D15") (pin "E2") (pinfunction "P$2_E2") (pintype "bidirectional"))
    )
    (net (code "310") (name "DB10-2") (class "Default")
      (node (ref "C27") (pin "L2") (pinfunction "L_L2") (pintype "input"))
      (node (ref "D20") (pin "E2") (pinfunction "P$2_E2") (pintype "bidirectional"))
    )
    (net (code "311") (name "DB10-3") (class "Default")
      (node (ref "C27") (pin "N2") (pinfunction "N_N2") (pintype "input"))
      (node (ref "D25") (pin "E2") (pinfunction "P$2_E2") (pintype "bidirectional"))
    )
    (net (code "312") (name "DB10-4") (class "Default")
      (node (ref "C27") (pin "R2") (pinfunction "R_R2") (pintype "input"))
      (node (ref "D30") (pin "E2") (pinfunction "P$2_E2") (pintype "bidirectional"))
    )
    (net (code "313") (name "DB10-5") (class "Default")
      (node (ref "A26") (pin "E2") (pinfunction "P$2_E2") (pintype "bidirectional"))
      (node (ref "C27") (pin "T2") (pinfunction "T_T2") (pintype "input"))
    )
    (net (code "314") (name "DB10-6") (class "Default")
      (node (ref "A31") (pin "E2") (pinfunction "P$2_E2") (pintype "bidirectional"))
      (node (ref "C27") (pin "V2") (pinfunction "V_V2") (pintype "input"))
    )
    (net (code "315") (name "DB11") (class "Default")
      (node (ref "A10") (pin "H2") (pinfunction "P$2_H2") (pintype "bidirectional"))
      (node (ref "B26") (pin "T2") (pinfunction "O$1_T2") (pintype "open_collector"))
    )
    (net (code "316") (name "DB11-0") (class "Default")
      (node (ref "C28") (pin "F2") (pinfunction "F_F2") (pintype "input"))
      (node (ref "D10") (pin "H2") (pinfunction "P$2_H2") (pintype "bidirectional"))
    )
    (net (code "317") (name "DB11-1") (class "Default")
      (node (ref "C28") (pin "J2") (pinfunction "J_J2") (pintype "input"))
      (node (ref "D15") (pin "H2") (pinfunction "P$2_H2") (pintype "bidirectional"))
    )
    (net (code "318") (name "DB11-2") (class "Default")
      (node (ref "C28") (pin "L2") (pinfunction "L_L2") (pintype "input"))
      (node (ref "D20") (pin "H2") (pinfunction "P$2_H2") (pintype "bidirectional"))
    )
    (net (code "319") (name "DB11-3") (class "Default")
      (node (ref "C28") (pin "N2") (pinfunction "N_N2") (pintype "input"))
      (node (ref "D25") (pin "H2") (pinfunction "P$2_H2") (pintype "bidirectional"))
    )
    (net (code "320") (name "DB11-4") (class "Default")
      (node (ref "C28") (pin "R2") (pinfunction "R_R2") (pintype "input"))
      (node (ref "D30") (pin "H2") (pinfunction "P$2_H2") (pintype "bidirectional"))
    )
    (net (code "321") (name "DB11-5") (class "Default")
      (node (ref "A26") (pin "H2") (pinfunction "P$2_H2") (pintype "bidirectional"))
      (node (ref "C28") (pin "T2") (pinfunction "T_T2") (pintype "input"))
    )
    (net (code "322") (name "DB11-6") (class "Default")
      (node (ref "A31") (pin "H2") (pinfunction "P$2_H2") (pintype "bidirectional"))
      (node (ref "C28") (pin "V2") (pinfunction "V_V2") (pintype "input"))
    )
    (net (code "323") (name "DB_SEL_DEV0") (class "Default")
      (node (ref "A12") (pin "D2") (pinfunction "O$1_D2") (pintype "open_collector"))
      (node (ref "B04") (pin "D2") (pinfunction "O$1_D2") (pintype "open_collector"))
      (node (ref "C17") (pin "E2") (pinfunction "E_E2") (pintype "input"))
      (node (ref "C18") (pin "E2") (pinfunction "E_E2") (pintype "input"))
      (node (ref "C19") (pin "E2") (pinfunction "E_E2") (pintype "input"))
      (node (ref "C20") (pin "E2") (pinfunction "E_E2") (pintype "input"))
      (node (ref "C21") (pin "E2") (pinfunction "E_E2") (pintype "input"))
      (node (ref "C22") (pin "E2") (pinfunction "E_E2") (pintype "input"))
      (node (ref "C23") (pin "E2") (pinfunction "E_E2") (pintype "input"))
      (node (ref "C24") (pin "E2") (pinfunction "E_E2") (pintype "input"))
      (node (ref "C25") (pin "E2") (pinfunction "E_E2") (pintype "input"))
      (node (ref "C26") (pin "E2") (pinfunction "E_E2") (pintype "input"))
      (node (ref "C27") (pin "E2") (pinfunction "E_E2") (pintype "input"))
      (node (ref "C28") (pin "E2") (pinfunction "E_E2") (pintype "input"))
      (node (ref "C29") (pin "E2") (pinfunction "E_E2") (pintype "input"))
      (node (ref "C30") (pin "E2") (pinfunction "E_E2") (pintype "input"))
    )
    (net (code "324") (name "DB_SEL_DEV1") (class "Default")
      (node (ref "A12") (pin "F2") (pinfunction "O$1_F2") (pintype "open_collector"))
      (node (ref "B04") (pin "F2") (pinfunction "O$1_F2") (pintype "open_collector"))
      (node (ref "C17") (pin "H2") (pinfunction "H_H2") (pintype "input"))
      (node (ref "C18") (pin "H2") (pinfunction "H_H2") (pintype "input"))
      (node (ref "C19") (pin "H2") (pinfunction "H_H2") (pintype "input"))
      (node (ref "C20") (pin "H2") (pinfunction "H_H2") (pintype "input"))
      (node (ref "C21") (pin "H2") (pinfunction "H_H2") (pintype "input"))
      (node (ref "C22") (pin "H2") (pinfunction "H_H2") (pintype "input"))
      (node (ref "C23") (pin "H2") (pinfunction "H_H2") (pintype "input"))
      (node (ref "C24") (pin "H2") (pinfunction "H_H2") (pintype "input"))
      (node (ref "C25") (pin "H2") (pinfunction "H_H2") (pintype "input"))
      (node (ref "C26") (pin "H2") (pinfunction "H_H2") (pintype "input"))
      (node (ref "C27") (pin "H2") (pinfunction "H_H2") (pintype "input"))
      (node (ref "C28") (pin "H2") (pinfunction "H_H2") (pintype "input"))
      (node (ref "C29") (pin "H2") (pinfunction "H_H2") (pintype "input"))
      (node (ref "C30") (pin "H2") (pinfunction "H_H2") (pintype "input"))
    )
    (net (code "325") (name "DB_SEL_DEV2") (class "Default")
      (node (ref "A12") (pin "J2") (pinfunction "O$1_J2") (pintype "open_collector"))
      (node (ref "B04") (pin "J2") (pinfunction "O$1_J2") (pintype "open_collector"))
      (node (ref "C17") (pin "K2") (pinfunction "K_K2") (pintype "input"))
      (node (ref "C18") (pin "K2") (pinfunction "K_K2") (pintype "input"))
      (node (ref "C19") (pin "K2") (pinfunction "K_K2") (pintype "input"))
      (node (ref "C20") (pin "K2") (pinfunction "K_K2") (pintype "input"))
      (node (ref "C21") (pin "K2") (pinfunction "K_K2") (pintype "input"))
      (node (ref "C22") (pin "K2") (pinfunction "K_K2") (pintype "input"))
      (node (ref "C23") (pin "K2") (pinfunction "K_K2") (pintype "input"))
      (node (ref "C24") (pin "K2") (pinfunction "K_K2") (pintype "input"))
      (node (ref "C25") (pin "K2") (pinfunction "K_K2") (pintype "input"))
      (node (ref "C26") (pin "K2") (pinfunction "K_K2") (pintype "input"))
      (node (ref "C27") (pin "K2") (pinfunction "K_K2") (pintype "input"))
      (node (ref "C28") (pin "K2") (pinfunction "K_K2") (pintype "input"))
      (node (ref "C29") (pin "K2") (pinfunction "K_K2") (pintype "input"))
      (node (ref "C30") (pin "K2") (pinfunction "K_K2") (pintype "input"))
    )
    (net (code "326") (name "DB_SEL_DEV3") (class "Default")
      (node (ref "A12") (pin "L2") (pinfunction "O$1_L2") (pintype "open_collector"))
      (node (ref "B04") (pin "L2") (pinfunction "O$1_L2") (pintype "open_collector"))
      (node (ref "C17") (pin "M2") (pinfunction "M_M2") (pintype "input"))
      (node (ref "C18") (pin "M2") (pinfunction "M_M2") (pintype "input"))
      (node (ref "C19") (pin "M2") (pinfunction "M_M2") (pintype "input"))
      (node (ref "C20") (pin "M2") (pinfunction "M_M2") (pintype "input"))
      (node (ref "C21") (pin "M2") (pinfunction "M_M2") (pintype "input"))
      (node (ref "C22") (pin "M2") (pinfunction "M_M2") (pintype "input"))
      (node (ref "C23") (pin "M2") (pinfunction "M_M2") (pintype "input"))
      (node (ref "C24") (pin "M2") (pinfunction "M_M2") (pintype "input"))
      (node (ref "C25") (pin "M2") (pinfunction "M_M2") (pintype "input"))
      (node (ref "C26") (pin "M2") (pinfunction "M_M2") (pintype "input"))
      (node (ref "C27") (pin "M2") (pinfunction "M_M2") (pintype "input"))
      (node (ref "C28") (pin "M2") (pinfunction "M_M2") (pintype "input"))
      (node (ref "C29") (pin "M2") (pinfunction "M_M2") (pintype "input"))
      (node (ref "C30") (pin "M2") (pinfunction "M_M2") (pintype "input"))
    )
    (net (code "327") (name "DB_SEL_DEV4") (class "Default")
      (node (ref "A12") (pin "N2") (pinfunction "O$1_N2") (pintype "open_collector"))
      (node (ref "B04") (pin "N2") (pinfunction "O$1_N2") (pintype "open_collector"))
      (node (ref "C17") (pin "P2") (pinfunction "P_P2") (pintype "input"))
      (node (ref "C18") (pin "P2") (pinfunction "P_P2") (pintype "input"))
      (node (ref "C19") (pin "P2") (pinfunction "P_P2") (pintype "input"))
      (node (ref "C20") (pin "P2") (pinfunction "P_P2") (pintype "input"))
      (node (ref "C21") (pin "P2") (pinfunction "P_P2") (pintype "input"))
      (node (ref "C22") (pin "P2") (pinfunction "P_P2") (pintype "input"))
      (node (ref "C23") (pin "P2") (pinfunction "P_P2") (pintype "input"))
      (node (ref "C24") (pin "P2") (pinfunction "P_P2") (pintype "input"))
      (node (ref "C25") (pin "P2") (pinfunction "P_P2") (pintype "input"))
      (node (ref "C26") (pin "P2") (pinfunction "P_P2") (pintype "input"))
      (node (ref "C27") (pin "P2") (pinfunction "P_P2") (pintype "input"))
      (node (ref "C28") (pin "P2") (pinfunction "P_P2") (pintype "input"))
      (node (ref "C29") (pin "P2") (pinfunction "P_P2") (pintype "input"))
      (node (ref "C30") (pin "P2") (pinfunction "P_P2") (pintype "input"))
    )
    (net (code "328") (name "DB_SEL_DEV5") (class "Default")
      (node (ref "A12") (pin "R2") (pinfunction "O$1_R2") (pintype "open_collector"))
      (node (ref "B04") (pin "R2") (pinfunction "O$1_R2") (pintype "open_collector"))
      (node (ref "C17") (pin "S2") (pinfunction "S_S2") (pintype "input"))
      (node (ref "C18") (pin "S2") (pinfunction "S_S2") (pintype "input"))
      (node (ref "C19") (pin "S2") (pinfunction "S_S2") (pintype "input"))
      (node (ref "C20") (pin "S2") (pinfunction "S_S2") (pintype "input"))
      (node (ref "C21") (pin "S2") (pinfunction "S_S2") (pintype "input"))
      (node (ref "C22") (pin "S2") (pinfunction "S_S2") (pintype "input"))
      (node (ref "C23") (pin "S2") (pinfunction "S_S2") (pintype "input"))
      (node (ref "C24") (pin "S2") (pinfunction "S_S2") (pintype "input"))
      (node (ref "C25") (pin "S2") (pinfunction "S_S2") (pintype "input"))
      (node (ref "C26") (pin "S2") (pinfunction "S_S2") (pintype "input"))
      (node (ref "C27") (pin "S2") (pinfunction "S_S2") (pintype "input"))
      (node (ref "C28") (pin "S2") (pinfunction "S_S2") (pintype "input"))
      (node (ref "C29") (pin "S2") (pinfunction "S_S2") (pintype "input"))
      (node (ref "C30") (pin "S2") (pinfunction "S_S2") (pintype "input"))
    )
    (net (code "329") (name "DB_SEL_DEV6") (class "Default")
      (node (ref "A12") (pin "T2") (pinfunction "O$1_T2") (pintype "open_collector"))
      (node (ref "B04") (pin "T2") (pinfunction "O$1_T2") (pintype "open_collector"))
      (node (ref "C17") (pin "U2") (pinfunction "U_U2") (pintype "input"))
      (node (ref "C18") (pin "U2") (pinfunction "U_U2") (pintype "input"))
      (node (ref "C19") (pin "U2") (pinfunction "U_U2") (pintype "input"))
      (node (ref "C20") (pin "U2") (pinfunction "U_U2") (pintype "input"))
      (node (ref "C21") (pin "U2") (pinfunction "U_U2") (pintype "input"))
      (node (ref "C22") (pin "U2") (pinfunction "U_U2") (pintype "input"))
      (node (ref "C23") (pin "U2") (pinfunction "U_U2") (pintype "input"))
      (node (ref "C24") (pin "U2") (pinfunction "U_U2") (pintype "input"))
      (node (ref "C25") (pin "U2") (pinfunction "U_U2") (pintype "input"))
      (node (ref "C26") (pin "U2") (pinfunction "U_U2") (pintype "input"))
      (node (ref "C27") (pin "U2") (pinfunction "U_U2") (pintype "input"))
      (node (ref "C28") (pin "U2") (pinfunction "U_U2") (pintype "input"))
      (node (ref "C29") (pin "U2") (pinfunction "U_U2") (pintype "input"))
      (node (ref "C30") (pin "U2") (pinfunction "U_U2") (pintype "input"))
    )
    (net (code "330") (name "DF0") (class "Default")
      (node (ref "A11") (pin "K2") (pinfunction "P$2_K2") (pintype "bidirectional"))
      (node (ref "A27") (pin "K2") (pinfunction "P$2_K2") (pintype "bidirectional"))
      (node (ref "A32") (pin "K2") (pinfunction "P$2_K2") (pintype "bidirectional"))
      (node (ref "D11") (pin "K2") (pinfunction "P$2_K2") (pintype "bidirectional"))
      (node (ref "D16") (pin "K2") (pinfunction "P$2_K2") (pintype "bidirectional"))
      (node (ref "D21") (pin "K2") (pinfunction "P$2_K2") (pintype "bidirectional"))
      (node (ref "D26") (pin "K2") (pinfunction "P$2_K2") (pintype "bidirectional"))
      (node (ref "D31") (pin "K2") (pinfunction "P$2_K2") (pintype "bidirectional"))
    )
    (net (code "331") (name "DF1") (class "Default")
      (node (ref "A11") (pin "M2") (pinfunction "P$2_M2") (pintype "bidirectional"))
      (node (ref "A27") (pin "M2") (pinfunction "P$2_M2") (pintype "bidirectional"))
      (node (ref "A32") (pin "M2") (pinfunction "P$2_M2") (pintype "bidirectional"))
      (node (ref "D11") (pin "M2") (pinfunction "P$2_M2") (pintype "bidirectional"))
      (node (ref "D16") (pin "M2") (pinfunction "P$2_M2") (pintype "bidirectional"))
      (node (ref "D21") (pin "M2") (pinfunction "P$2_M2") (pintype "bidirectional"))
      (node (ref "D26") (pin "M2") (pinfunction "P$2_M2") (pintype "bidirectional"))
      (node (ref "D31") (pin "M2") (pinfunction "P$2_M2") (pintype "bidirectional"))
    )
    (net (code "332") (name "DF2") (class "Default")
      (node (ref "A11") (pin "P2") (pinfunction "P$2_P2") (pintype "bidirectional"))
      (node (ref "A27") (pin "P2") (pinfunction "P$2_P2") (pintype "bidirectional"))
      (node (ref "A32") (pin "P2") (pinfunction "P$2_P2") (pintype "bidirectional"))
      (node (ref "D11") (pin "P2") (pinfunction "P$2_P2") (pintype "bidirectional"))
      (node (ref "D16") (pin "P2") (pinfunction "P$2_P2") (pintype "bidirectional"))
      (node (ref "D21") (pin "P2") (pinfunction "P$2_P2") (pintype "bidirectional"))
      (node (ref "D26") (pin "P2") (pinfunction "P$2_P2") (pintype "bidirectional"))
      (node (ref "D31") (pin "P2") (pinfunction "P$2_P2") (pintype "bidirectional"))
    )
    (net (code "333") (name "GND") (class "Default")
      (node (ref "A14") (pin "J2") (pinfunction "J_J2") (pintype "input"))
      (node (ref "A14") (pin "P2") (pinfunction "J_P2") (pintype "input"))
      (node (ref "A14") (pin "V2") (pinfunction "J_V2") (pintype "input"))
      (node (ref "A15") (pin "J2") (pinfunction "J_J2") (pintype "input"))
      (node (ref "A15") (pin "P2") (pinfunction "J_P2") (pintype "input"))
      (node (ref "A19") (pin "E2") (pinfunction "EN0_E2") (pintype "input"))
      (node (ref "B03") (pin "H2") (pinfunction "G_H2") (pintype "input"))
      (node (ref "B03") (pin "N2") (pinfunction "G_N2") (pintype "input"))
      (node (ref "B03") (pin "U2") (pinfunction "G_U2") (pintype "input"))
      (node (ref "B27") (pin "J2") (pinfunction "J_J2") (pintype "input"))
      (node (ref "B27") (pin "P2") (pinfunction "J_P2") (pintype "input"))
      (node (ref "B27") (pin "V2") (pinfunction "J_V2") (pintype "input"))
      (node (ref "B28") (pin "J2") (pinfunction "J_J2") (pintype "input"))
      (node (ref "B28") (pin "P2") (pinfunction "J_P2") (pintype "input"))
      (node (ref "B28") (pin "V2") (pinfunction "J_V2") (pintype "input"))
      (node (ref "B29") (pin "J2") (pinfunction "J_J2") (pintype "input"))
      (node (ref "B29") (pin "P2") (pinfunction "J_P2") (pintype "input"))
      (node (ref "B29") (pin "V2") (pinfunction "J_V2") (pintype "input"))
    )
    (net (code "334") (name "INC_MB") (class "Default")
      (node (ref "A08") (pin "T2") (pinfunction "P$2_T2") (pintype "bidirectional"))
      (node (ref "A24") (pin "T2") (pinfunction "P$2_T2") (pintype "bidirectional"))
      (node (ref "A29") (pin "T2") (pinfunction "P$2_T2") (pintype "bidirectional"))
      (node (ref "D08") (pin "T2") (pinfunction "P$2_T2") (pintype "bidirectional"))
      (node (ref "D13") (pin "T2") (pinfunction "P$2_T2") (pintype "bidirectional"))
      (node (ref "D18") (pin "T2") (pinfunction "P$2_T2") (pintype "bidirectional"))
      (node (ref "D23") (pin "T2") (pinfunction "P$2_T2") (pintype "bidirectional"))
      (node (ref "D28") (pin "T2") (pinfunction "P$2_T2") (pintype "bidirectional"))
    )
    (net (code "335") (name "IOP1") (class "Default")
      (node (ref "A02") (pin "K2") (pinfunction "P$2_K2") (pintype "bidirectional"))
      (node (ref "D02") (pin "K2") (pinfunction "P$2_K2") (pintype "bidirectional"))
    )
    (net (code "336") (name "IOP2") (class "Default")
      (node (ref "A02") (pin "M2") (pinfunction "P$2_M2") (pintype "bidirectional"))
      (node (ref "D02") (pin "M2") (pinfunction "P$2_M2") (pintype "bidirectional"))
    )
    (net (code "337") (name "IOP4") (class "Default")
      (node (ref "A02") (pin "P2") (pinfunction "P$2_P2") (pintype "bidirectional"))
      (node (ref "D02") (pin "P2") (pinfunction "P$2_P2") (pintype "bidirectional"))
    )
    (net (code "338") (name "MPX0") (class "Default")
      (node (ref "A13") (pin "E2") (pinfunction "I$1_E2") (pintype "input"))
      (node (ref "A21") (pin "S2") (pinfunction "P$2_S2") (pintype "bidirectional"))
      (node (ref "B05") (pin "E2") (pinfunction "I$1_E2") (pintype "input"))
      (node (ref "B12") (pin "M2") (pinfunction "M_M2") (pintype "input"))
      (node (ref "B14") (pin "J2") (pinfunction "1_J2") (pintype "open_collector"))
      (node (ref "B14") (pin "P2") (pinfunction "EN0_P2") (pintype "input"))
      (node (ref "B30") (pin "D2") (pinfunction "I$1_D2") (pintype "input"))
    )
    (net (code "339") (name "MPX1") (class "Default")
      (node (ref "A13") (pin "H2") (pinfunction "I$1_H2") (pintype "input"))
      (node (ref "A21") (pin "P2") (pinfunction "P$2_P2") (pintype "bidirectional"))
      (node (ref "B05") (pin "H2") (pinfunction "I$1_H2") (pintype "input"))
      (node (ref "B12") (pin "F2") (pinfunction "F_F2") (pintype "input"))
      (node (ref "B13") (pin "D2") (pinfunction "O$1_D2") (pintype "open_collector"))
      (node (ref "B16") (pin "J2") (pinfunction "1_J2") (pintype "open_collector"))
      (node (ref "B16") (pin "P2") (pinfunction "EN0_P2") (pintype "input"))
      (node (ref "B30") (pin "K2") (pinfunction "I$1_K2") (pintype "input"))
    )
    (net (code "340") (name "MPX2") (class "Default")
      (node (ref "A13") (pin "K2") (pinfunction "I$1_K2") (pintype "input"))
      (node (ref "A21") (pin "M2") (pinfunction "P$2_M2") (pintype "bidirectional"))
      (node (ref "B05") (pin "K2") (pinfunction "I$1_K2") (pintype "input"))
      (node (ref "B12") (pin "K2") (pinfunction "K_K2") (pintype "input"))
      (node (ref "B13") (pin "F2") (pinfunction "O$1_F2") (pintype "open_collector"))
      (node (ref "B17") (pin "J2") (pinfunction "1_J2") (pintype "open_collector"))
      (node (ref "B17") (pin "P2") (pinfunction "EN0_P2") (pintype "input"))
      (node (ref "B30") (pin "R2") (pinfunction "I$1_R2") (pintype "input"))
    )
    (net (code "341") (name "MPX3") (class "Default")
      (node (ref "A13") (pin "M2") (pinfunction "I$1_M2") (pintype "input"))
      (node (ref "A21") (pin "K2") (pinfunction "P$2_K2") (pintype "bidirectional"))
      (node (ref "B05") (pin "M2") (pinfunction "I$1_M2") (pintype "input"))
      (node (ref "B12") (pin "E2") (pinfunction "E_E2") (pintype "input"))
      (node (ref "B13") (pin "J2") (pinfunction "O$1_J2") (pintype "open_collector"))
      (node (ref "B18") (pin "J2") (pinfunction "1_J2") (pintype "open_collector"))
      (node (ref "B18") (pin "P2") (pinfunction "EN0_P2") (pintype "input"))
      (node (ref "B31") (pin "D2") (pinfunction "I$1_D2") (pintype "input"))
    )
    (net (code "342") (name "MPX4") (class "Default")
      (node (ref "A13") (pin "P2") (pinfunction "I$1_P2") (pintype "input"))
      (node (ref "A21") (pin "H2") (pinfunction "P$2_H2") (pintype "bidirectional"))
      (node (ref "B05") (pin "P2") (pinfunction "I$1_P2") (pintype "input"))
      (node (ref "B12") (pin "J2") (pinfunction "J_J2") (pintype "input"))
      (node (ref "B13") (pin "L2") (pinfunction "O$1_L2") (pintype "open_collector"))
      (node (ref "B19") (pin "J2") (pinfunction "1_J2") (pintype "open_collector"))
      (node (ref "B19") (pin "P2") (pinfunction "EN0_P2") (pintype "input"))
      (node (ref "B31") (pin "K2") (pinfunction "I$1_K2") (pintype "input"))
    )
    (net (code "343") (name "MPX5") (class "Default")
      (node (ref "A13") (pin "S2") (pinfunction "I$1_S2") (pintype "input"))
      (node (ref "A21") (pin "E2") (pinfunction "P$2_E2") (pintype "bidirectional"))
      (node (ref "B05") (pin "S2") (pinfunction "I$1_S2") (pintype "input"))
      (node (ref "B12") (pin "D2") (pinfunction "D_D2") (pintype "input"))
      (node (ref "B13") (pin "N2") (pinfunction "O$1_N2") (pintype "open_collector"))
      (node (ref "B20") (pin "J2") (pinfunction "1_J2") (pintype "open_collector"))
      (node (ref "B20") (pin "P2") (pinfunction "EN0_P2") (pintype "input"))
      (node (ref "B31") (pin "R2") (pinfunction "I$1_R2") (pintype "input"))
    )
    (net (code "344") (name "MPX6") (class "Default")
      (node (ref "A13") (pin "U2") (pinfunction "I$1_U2") (pintype "input"))
      (node (ref "A21") (pin "D2") (pinfunction "P$2_D2") (pintype "bidirectional"))
      (node (ref "B05") (pin "U2") (pinfunction "I$1_U2") (pintype "input"))
      (node (ref "B13") (pin "R2") (pinfunction "O$1_R2") (pintype "open_collector"))
      (node (ref "B21") (pin "J2") (pinfunction "1_J2") (pintype "open_collector"))
      (node (ref "B21") (pin "P2") (pinfunction "EN0_P2") (pintype "input"))
      (node (ref "B23") (pin "D2") (pinfunction "I$1_D2") (pintype "input"))
    )
    (net (code "345") (name "Net-(A14A-D)") (class "Default")
      (node (ref "A14") (pin "D2") (pinfunction "D_D2") (pintype "input"))
      (node (ref "A16") (pin "U2") (pinfunction "O$1_U2") (pintype "open_collector"))
      (node (ref "A16") (pin "V2") (pinfunction "P$1_V2") (pintype "passive"))
    )
    (net (code "346") (name "Net-(A14B-D)") (class "Default")
      (node (ref "A14") (pin "K2") (pinfunction "D_K2") (pintype "input"))
      (node (ref "A17") (pin "H2") (pinfunction "O$1_H2") (pintype "open_collector"))
      (node (ref "A17") (pin "J2") (pinfunction "P$1_J2") (pintype "passive"))
    )
    (net (code "347") (name "Net-(A14C-D)") (class "Default")
      (node (ref "A14") (pin "R2") (pinfunction "D_R2") (pintype "input"))
      (node (ref "A17") (pin "N2") (pinfunction "O$1_N2") (pintype "open_collector"))
      (node (ref "A17") (pin "P2") (pinfunction "P$1_P2") (pintype "passive"))
    )
    (net (code "348") (name "Net-(A15A-D)") (class "Default")
      (node (ref "A15") (pin "D2") (pinfunction "D_D2") (pintype "input"))
      (node (ref "A17") (pin "U2") (pinfunction "O$1_U2") (pintype "open_collector"))
      (node (ref "A17") (pin "V2") (pinfunction "P$1_V2") (pintype "passive"))
    )
    (net (code "349") (name "Net-(A15B-D)") (class "Default")
      (node (ref "A15") (pin "K2") (pinfunction "D_K2") (pintype "input"))
      (node (ref "A18") (pin "H2") (pinfunction "O$1_H2") (pintype "open_collector"))
      (node (ref "A18") (pin "J2") (pinfunction "P$1_J2") (pintype "passive"))
    )
    (net (code "350") (name "Net-(A16C-O$1)") (class "Default")
      (node (ref "A16") (pin "H2") (pinfunction "O$1_H2") (pintype "open_collector"))
      (node (ref "A16") (pin "J2") (pinfunction "P$1_J2") (pintype "passive"))
      (node (ref "B29") (pin "K2") (pinfunction "D_K2") (pintype "input"))
    )
    (net (code "351") (name "Net-(A16E-O$1)") (class "Default")
      (node (ref "A16") (pin "N2") (pinfunction "O$1_N2") (pintype "open_collector"))
      (node (ref "A16") (pin "P2") (pinfunction "P$1_P2") (pintype "passive"))
      (node (ref "B29") (pin "R2") (pinfunction "D_R2") (pintype "input"))
    )
    (net (code "352") (name "Net-(A19C-PU1)") (class "Default")
      (node (ref "A19") (pin "K2") (pinfunction "PU1_K2") (pintype "input"))
      (node (ref "B03") (pin "F2") (pinfunction "O_F2") (pintype "open_collector"))
      (node (ref "B14") (pin "N2") (pinfunction "PU0_N2") (pintype "input"))
      (node (ref "B14") (pin "U2") (pinfunction "PU1_U2") (pintype "input"))
      (node (ref "B16") (pin "N2") (pinfunction "PU0_N2") (pintype "input"))
      (node (ref "B16") (pin "U2") (pinfunction "PU1_U2") (pintype "input"))
      (node (ref "B17") (pin "N2") (pinfunction "PU0_N2") (pintype "input"))
      (node (ref "B17") (pin "U2") (pinfunction "PU1_U2") (pintype "input"))
      (node (ref "B18") (pin "N2") (pinfunction "PU0_N2") (pintype "input"))
      (node (ref "B18") (pin "U2") (pinfunction "PU1_U2") (pintype "input"))
      (node (ref "B19") (pin "N2") (pinfunction "PU0_N2") (pintype "input"))
      (node (ref "B19") (pin "U2") (pinfunction "PU1_U2") (pintype "input"))
      (node (ref "B20") (pin "N2") (pinfunction "PU0_N2") (pintype "input"))
      (node (ref "B20") (pin "U2") (pinfunction "PU1_U2") (pintype "input"))
      (node (ref "B21") (pin "N2") (pinfunction "PU0_N2") (pintype "input"))
      (node (ref "B21") (pin "U2") (pinfunction "PU1_U2") (pintype "input"))
    )
    (net (code "353") (name "Net-(A19C-RESET)") (class "Default")
      (node (ref "A19") (pin "F2") (pinfunction "RESET_F2") (pintype "input"))
      (node (ref "B14") (pin "F2") (pinfunction "RESET_F2") (pintype "input"))
      (node (ref "B14") (pin "R2") (pinfunction "RESET_R2") (pintype "input"))
      (node (ref "B16") (pin "F2") (pinfunction "RESET_F2") (pintype "input"))
      (node (ref "B16") (pin "R2") (pinfunction "RESET_R2") (pintype "input"))
      (node (ref "B17") (pin "F2") (pinfunction "RESET_F2") (pintype "input"))
      (node (ref "B17") (pin "R2") (pinfunction "RESET_R2") (pintype "input"))
      (node (ref "B18") (pin "F2") (pinfunction "RESET_F2") (pintype "input"))
      (node (ref "B18") (pin "R2") (pinfunction "RESET_R2") (pintype "input"))
      (node (ref "B19") (pin "F2") (pinfunction "RESET_F2") (pintype "input"))
      (node (ref "B19") (pin "R2") (pinfunction "RESET_R2") (pintype "input"))
      (node (ref "B20") (pin "F2") (pinfunction "RESET_F2") (pintype "input"))
      (node (ref "B20") (pin "R2") (pinfunction "RESET_R2") (pintype "input"))
      (node (ref "B21") (pin "F2") (pinfunction "RESET_F2") (pintype "input"))
      (node (ref "B21") (pin "R2") (pinfunction "RESET_R2") (pintype "input"))
      (node (ref "B32") (pin "J2") (pinfunction "O$1_J2") (pintype "open_collector"))
    )
    (net (code "354") (name "Net-(B02A-O$1)") (class "Default")
      (node (ref "B02") (pin "D2") (pinfunction "O$1_D2") (pintype "open_collector"))
      (node (ref "B14") (pin "E2") (pinfunction "EN0_E2") (pintype "input"))
    )
    (net (code "355") (name "Net-(B02B-O$1)") (class "Default")
      (node (ref "B02") (pin "F2") (pinfunction "O$1_F2") (pintype "open_collector"))
      (node (ref "B16") (pin "E2") (pinfunction "EN0_E2") (pintype "input"))
    )
    (net (code "356") (name "Net-(B02E-O$1)") (class "Default")
      (node (ref "B02") (pin "J2") (pinfunction "O$1_J2") (pintype "open_collector"))
      (node (ref "B17") (pin "E2") (pinfunction "EN0_E2") (pintype "input"))
    )
    (net (code "357") (name "Net-(B02F-O$1)") (class "Default")
      (node (ref "B02") (pin "L2") (pinfunction "O$1_L2") (pintype "open_collector"))
      (node (ref "B18") (pin "E2") (pinfunction "EN0_E2") (pintype "input"))
    )
    (net (code "358") (name "Net-(B02G-O$1)") (class "Default")
      (node (ref "B02") (pin "N2") (pinfunction "O$1_N2") (pintype "open_collector"))
      (node (ref "B19") (pin "E2") (pinfunction "EN0_E2") (pintype "input"))
    )
    (net (code "359") (name "Net-(B02H-O$1)") (class "Default")
      (node (ref "B02") (pin "R2") (pinfunction "O$1_R2") (pintype "open_collector"))
      (node (ref "B20") (pin "E2") (pinfunction "EN0_E2") (pintype "input"))
    )
    (net (code "360") (name "Net-(B02I-O$1)") (class "Default")
      (node (ref "B02") (pin "T2") (pinfunction "O$1_T2") (pintype "open_collector"))
      (node (ref "B21") (pin "E2") (pinfunction "EN0_E2") (pintype "input"))
    )
    (net (code "361") (name "Net-(B03A-I$1)") (class "Default")
      (node (ref "B03") (pin "J2") (pinfunction "I$1_J2") (pintype "passive"))
      (node (ref "B32") (pin "F2") (pinfunction "O$1_F2") (pintype "open_collector"))
    )
    (net (code "362") (name "Net-(B03D-O)") (class "Default")
      (node (ref "B03") (pin "M2") (pinfunction "O_M2") (pintype "open_collector"))
      (node (ref "B14") (pin "K2") (pinfunction "PU1_K2") (pintype "input"))
      (node (ref "B16") (pin "K2") (pinfunction "PU1_K2") (pintype "input"))
      (node (ref "B17") (pin "K2") (pinfunction "PU1_K2") (pintype "input"))
      (node (ref "B18") (pin "K2") (pinfunction "PU1_K2") (pintype "input"))
      (node (ref "B19") (pin "K2") (pinfunction "PU1_K2") (pintype "input"))
      (node (ref "B20") (pin "K2") (pinfunction "PU1_K2") (pintype "input"))
      (node (ref "B21") (pin "K2") (pinfunction "PU1_K2") (pintype "input"))
    )
    (net (code "363") (name "Net-(B03D-PU0)") (class "Default")
      (node (ref "B03") (pin "K2") (pinfunction "PU0_K2") (pintype "input"))
      (node (ref "B03") (pin "R2") (pinfunction "PU0_R2") (pintype "input"))
      (node (ref "B32") (pin "L2") (pinfunction "O$1_L2") (pintype "open_collector"))
    )
    (net (code "364") (name "Net-(B03E-O)") (class "Default")
      (node (ref "B03") (pin "T2") (pinfunction "O_T2") (pintype "open_collector"))
      (node (ref "B14") (pin "D2") (pinfunction "PU0_D2") (pintype "input"))
      (node (ref "B16") (pin "D2") (pinfunction "PU0_D2") (pintype "input"))
      (node (ref "B17") (pin "D2") (pinfunction "PU0_D2") (pintype "input"))
      (node (ref "B18") (pin "D2") (pinfunction "PU0_D2") (pintype "input"))
      (node (ref "B19") (pin "D2") (pinfunction "PU0_D2") (pintype "input"))
      (node (ref "B20") (pin "D2") (pinfunction "PU0_D2") (pintype "input"))
      (node (ref "B21") (pin "D2") (pinfunction "PU0_D2") (pintype "input"))
    )
    (net (code "365") (name "Net-(B06C-O$1)") (class "Default")
      (node (ref "B06") (pin "H2") (pinfunction "O$1_H2") (pintype "open_collector"))
      (node (ref "B06") (pin "J2") (pinfunction "P$1_J2") (pintype "passive"))
      (node (ref "B10") (pin "E2") (pinfunction "I$1_E2") (pintype "input"))
    )
    (net (code "366") (name "Net-(B06E-O$1)") (class "Default")
      (node (ref "B06") (pin "N2") (pinfunction "O$1_N2") (pintype "open_collector"))
      (node (ref "B06") (pin "P2") (pinfunction "P$1_P2") (pintype "passive"))
      (node (ref "B10") (pin "H2") (pinfunction "I$1_H2") (pintype "input"))
    )
    (net (code "367") (name "Net-(B06G-O$1)") (class "Default")
      (node (ref "B06") (pin "U2") (pinfunction "O$1_U2") (pintype "open_collector"))
      (node (ref "B06") (pin "V2") (pinfunction "P$1_V2") (pintype "passive"))
      (node (ref "B10") (pin "K2") (pinfunction "I$1_K2") (pintype "input"))
    )
    (net (code "368") (name "Net-(B07A-I$1)") (class "Default")
      (node (ref "B07") (pin "E2") (pinfunction "I$1_E2") (pintype "input"))
      (node (ref "B11") (pin "D2") (pinfunction "P$1_D2") (pintype "passive"))
      (node (ref "C01") (pin "D2") (pinfunction "D_D2") (pintype "output"))
    )
    (net (code "369") (name "Net-(B07B-I$1)") (class "Default")
      (node (ref "B07") (pin "H2") (pinfunction "I$1_H2") (pintype "input"))
      (node (ref "B11") (pin "E2") (pinfunction "P$1_E2") (pintype "passive"))
      (node (ref "C02") (pin "D2") (pinfunction "D_D2") (pintype "output"))
    )
    (net (code "370") (name "Net-(B07E-I$1)") (class "Default")
      (node (ref "B07") (pin "K2") (pinfunction "I$1_K2") (pintype "input"))
      (node (ref "B11") (pin "F2") (pinfunction "P$1_F2") (pintype "passive"))
      (node (ref "C03") (pin "D2") (pinfunction "D_D2") (pintype "output"))
    )
    (net (code "371") (name "Net-(B07F-I$1)") (class "Default")
      (node (ref "B07") (pin "M2") (pinfunction "I$1_M2") (pintype "input"))
      (node (ref "B11") (pin "H2") (pinfunction "P$1_H2") (pintype "passive"))
      (node (ref "C04") (pin "D2") (pinfunction "D_D2") (pintype "output"))
    )
    (net (code "372") (name "Net-(B07G-I$1)") (class "Default")
      (node (ref "B07") (pin "P2") (pinfunction "I$1_P2") (pintype "input"))
      (node (ref "B11") (pin "J2") (pinfunction "P$1_J2") (pintype "passive"))
      (node (ref "C05") (pin "D2") (pinfunction "D_D2") (pintype "output"))
    )
    (net (code "373") (name "Net-(B07H-I$1)") (class "Default")
      (node (ref "B07") (pin "S2") (pinfunction "I$1_S2") (pintype "input"))
      (node (ref "B11") (pin "K2") (pinfunction "P$1_K2") (pintype "passive"))
      (node (ref "C06") (pin "D2") (pinfunction "D_D2") (pintype "output"))
    )
    (net (code "374") (name "Net-(B07I-I$1)") (class "Default")
      (node (ref "B07") (pin "U2") (pinfunction "I$1_U2") (pintype "input"))
      (node (ref "B11") (pin "L2") (pinfunction "P$1_L2") (pintype "passive"))
      (node (ref "C07") (pin "D2") (pinfunction "D_D2") (pintype "output"))
    )
    (net (code "375") (name "Net-(B08C-O$1)") (class "Default")
      (node (ref "B08") (pin "H2") (pinfunction "O$1_H2") (pintype "open_collector"))
      (node (ref "B08") (pin "J2") (pinfunction "P$1_J2") (pintype "passive"))
      (node (ref "B10") (pin "M2") (pinfunction "I$1_M2") (pintype "input"))
    )
    (net (code "376") (name "Net-(B08E-O$1)") (class "Default")
      (node (ref "B08") (pin "N2") (pinfunction "O$1_N2") (pintype "open_collector"))
      (node (ref "B08") (pin "P2") (pinfunction "P$1_P2") (pintype "passive"))
      (node (ref "B10") (pin "P2") (pinfunction "I$1_P2") (pintype "input"))
    )
    (net (code "377") (name "Net-(B08G-O$1)") (class "Default")
      (node (ref "B08") (pin "U2") (pinfunction "O$1_U2") (pintype "open_collector"))
      (node (ref "B08") (pin "V2") (pinfunction "P$1_V2") (pintype "passive"))
      (node (ref "B10") (pin "S2") (pinfunction "I$1_S2") (pintype "input"))
    )
    (net (code "378") (name "Net-(B10I-I$1)") (class "Default")
      (node (ref "B10") (pin "U2") (pinfunction "I$1_U2") (pintype "input"))
      (node (ref "B23") (pin "U2") (pinfunction "O$1_U2") (pintype "open_collector"))
      (node (ref "B23") (pin "V2") (pinfunction "P$1_V2") (pintype "passive"))
    )
    (net (code "379") (name "Net-(B11J-P$1)") (class "Default")
      (node (ref "B11") (pin "M2") (pinfunction "P$1_M2") (pintype "passive"))
      (node (ref "B15") (pin "E2") (pinfunction "I$1_E2") (pintype "input"))
      (node (ref "C08") (pin "D2") (pinfunction "D_D2") (pintype "output"))
    )
    (net (code "380") (name "Net-(B11K-P$1)") (class "Default")
      (node (ref "B11") (pin "N2") (pinfunction "P$1_N2") (pintype "passive"))
      (node (ref "B15") (pin "H2") (pinfunction "I$1_H2") (pintype "input"))
      (node (ref "C09") (pin "D2") (pinfunction "D_D2") (pintype "output"))
    )
    (net (code "381") (name "Net-(B11L-P$1)") (class "Default")
      (node (ref "B11") (pin "P2") (pinfunction "P$1_P2") (pintype "passive"))
      (node (ref "B15") (pin "K2") (pinfunction "I$1_K2") (pintype "input"))
      (node (ref "C10") (pin "D2") (pinfunction "D_D2") (pintype "output"))
    )
    (net (code "382") (name "Net-(B11M-P$1)") (class "Default")
      (node (ref "B11") (pin "R2") (pinfunction "P$1_R2") (pintype "passive"))
      (node (ref "B15") (pin "M2") (pinfunction "I$1_M2") (pintype "input"))
      (node (ref "C11") (pin "D2") (pinfunction "D_D2") (pintype "output"))
    )
    (net (code "383") (name "Net-(B11N-P$1)") (class "Default")
      (node (ref "B11") (pin "S2") (pinfunction "P$1_S2") (pintype "passive"))
      (node (ref "B15") (pin "P2") (pinfunction "I$1_P2") (pintype "input"))
      (node (ref "C12") (pin "D2") (pinfunction "D_D2") (pintype "output"))
    )
    (net (code "384") (name "Net-(B11O-P$1)") (class "Default")
      (node (ref "B11") (pin "T2") (pinfunction "P$1_T2") (pintype "passive"))
      (node (ref "B15") (pin "S2") (pinfunction "I$1_S2") (pintype "input"))
      (node (ref "C13") (pin "D2") (pinfunction "D_D2") (pintype "output"))
    )
    (net (code "385") (name "Net-(B11P-P$1)") (class "Default")
      (node (ref "B11") (pin "U2") (pinfunction "P$1_U2") (pintype "passive"))
      (node (ref "B15") (pin "U2") (pinfunction "I$1_U2") (pintype "input"))
      (node (ref "C14") (pin "D2") (pinfunction "D_D2") (pintype "output"))
    )
    (net (code "386") (name "Net-(B11Q-P$1)") (class "Default")
      (node (ref "B11") (pin "V2") (pinfunction "P$1_V2") (pintype "passive"))
      (node (ref "B25") (pin "E2") (pinfunction "I$1_E2") (pintype "input"))
      (node (ref "C15") (pin "D2") (pinfunction "D_D2") (pintype "output"))
    )
    (net (code "387") (name "Net-(B12A-N)") (class "Default")
      (node (ref "B12") (pin "N2") (pinfunction "N_N2") (pintype "output"))
      (node (ref "B13") (pin "K2") (pinfunction "I$1_K2") (pintype "input"))
    )
    (net (code "388") (name "Net-(B12A-P)") (class "Default")
      (node (ref "B12") (pin "P2") (pinfunction "P_P2") (pintype "output"))
      (node (ref "B13") (pin "M2") (pinfunction "I$1_M2") (pintype "input"))
    )
    (net (code "389") (name "Net-(B12A-R)") (class "Default")
      (node (ref "B12") (pin "R2") (pinfunction "R_R2") (pintype "output"))
      (node (ref "B13") (pin "H2") (pinfunction "I$1_H2") (pintype "input"))
    )
    (net (code "390") (name "Net-(B12A-S)") (class "Default")
      (node (ref "B12") (pin "S2") (pinfunction "S_S2") (pintype "output"))
      (node (ref "B13") (pin "E2") (pinfunction "I$1_E2") (pintype "input"))
    )
    (net (code "391") (name "Net-(B12A-T)") (class "Default")
      (node (ref "B12") (pin "T2") (pinfunction "T_T2") (pintype "output"))
      (node (ref "B13") (pin "P2") (pinfunction "I$1_P2") (pintype "input"))
    )
    (net (code "392") (name "Net-(B12A-U)") (class "Default")
      (node (ref "B12") (pin "U2") (pinfunction "U_U2") (pintype "output"))
      (node (ref "B13") (pin "S2") (pinfunction "I$1_S2") (pintype "input"))
    )
    (net (code "393") (name "Net-(B14C-0)") (class "Default")
      (node (ref "B14") (pin "H2") (pinfunction "0_H2") (pintype "open_collector"))
      (node (ref "B14") (pin "V2") (pinfunction "EN1_V2") (pintype "input"))
    )
    (net (code "394") (name "Net-(B16C-0)") (class "Default")
      (node (ref "B16") (pin "H2") (pinfunction "0_H2") (pintype "open_collector"))
      (node (ref "B16") (pin "V2") (pinfunction "EN1_V2") (pintype "input"))
    )
    (net (code "395") (name "Net-(B17C-0)") (class "Default")
      (node (ref "B17") (pin "H2") (pinfunction "0_H2") (pintype "open_collector"))
      (node (ref "B17") (pin "V2") (pinfunction "EN1_V2") (pintype "input"))
    )
    (net (code "396") (name "Net-(B18C-0)") (class "Default")
      (node (ref "B18") (pin "H2") (pinfunction "0_H2") (pintype "open_collector"))
      (node (ref "B18") (pin "V2") (pinfunction "EN1_V2") (pintype "input"))
    )
    (net (code "397") (name "Net-(B19C-0)") (class "Default")
      (node (ref "B19") (pin "H2") (pinfunction "0_H2") (pintype "open_collector"))
      (node (ref "B19") (pin "V2") (pinfunction "EN1_V2") (pintype "input"))
    )
    (net (code "398") (name "Net-(B20C-0)") (class "Default")
      (node (ref "B20") (pin "H2") (pinfunction "0_H2") (pintype "open_collector"))
      (node (ref "B20") (pin "V2") (pinfunction "EN1_V2") (pintype "input"))
    )
    (net (code "399") (name "Net-(B21C-0)") (class "Default")
      (node (ref "B21") (pin "H2") (pinfunction "0_H2") (pintype "open_collector"))
      (node (ref "B21") (pin "V2") (pinfunction "EN1_V2") (pintype "input"))
    )
    (net (code "400") (name "Net-(B22A-F)") (class "Default")
      (node (ref "B22") (pin "F2") (pinfunction "F_F2") (pintype "open_collector"))
      (node (ref "B22") (pin "K2") (pinfunction "F_K2") (pintype "open_collector"))
      (node (ref "B22") (pin "N2") (pinfunction "F_N2") (pintype "open_collector"))
      (node (ref "B23") (pin "M2") (pinfunction "I$3_M2") (pintype "passive"))
    )
    (net (code "401") (name "Net-(B23C-O$1)") (class "Default")
      (node (ref "B23") (pin "H2") (pinfunction "O$1_H2") (pintype "open_collector"))
      (node (ref "B23") (pin "J2") (pinfunction "P$1_J2") (pintype "passive"))
      (node (ref "B29") (pin "D2") (pinfunction "D_D2") (pintype "input"))
    )
    (net (code "402") (name "Net-(B23E-O$1)") (class "Default")
      (node (ref "B23") (pin "N2") (pinfunction "O$1_N2") (pintype "open_collector"))
      (node (ref "B23") (pin "P2") (pinfunction "P$1_P2") (pintype "passive"))
      (node (ref "B32") (pin "E2") (pinfunction "I$1_E2") (pintype "input"))
    )
    (net (code "403") (name "Net-(B24A-P$1)") (class "Default")
      (node (ref "B24") (pin "D2") (pinfunction "P$1_D2") (pintype "passive"))
      (node (ref "B25") (pin "H2") (pinfunction "I$1_H2") (pintype "input"))
      (node (ref "C16") (pin "D2") (pinfunction "D_D2") (pintype "output"))
    )
    (net (code "404") (name "Net-(B24B-P$1)") (class "Default")
      (node (ref "B24") (pin "E2") (pinfunction "P$1_E2") (pintype "passive"))
      (node (ref "B25") (pin "K2") (pinfunction "I$1_K2") (pintype "input"))
      (node (ref "C17") (pin "D2") (pinfunction "D_D2") (pintype "output"))
    )
    (net (code "405") (name "Net-(B24C-P$1)") (class "Default")
      (node (ref "B24") (pin "F2") (pinfunction "P$1_F2") (pintype "passive"))
      (node (ref "B25") (pin "M2") (pinfunction "I$1_M2") (pintype "input"))
      (node (ref "C18") (pin "D2") (pinfunction "D_D2") (pintype "output"))
    )
    (net (code "406") (name "Net-(B24F-P$1)") (class "Default")
      (node (ref "B24") (pin "H2") (pinfunction "P$1_H2") (pintype "passive"))
      (node (ref "B25") (pin "P2") (pinfunction "I$1_P2") (pintype "input"))
      (node (ref "C19") (pin "D2") (pinfunction "D_D2") (pintype "output"))
    )
    (net (code "407") (name "Net-(B24G-P$1)") (class "Default")
      (node (ref "B24") (pin "J2") (pinfunction "P$1_J2") (pintype "passive"))
      (node (ref "B25") (pin "S2") (pinfunction "I$1_S2") (pintype "input"))
      (node (ref "C20") (pin "D2") (pinfunction "D_D2") (pintype "output"))
    )
    (net (code "408") (name "Net-(B24H-P$1)") (class "Default")
      (node (ref "B24") (pin "K2") (pinfunction "P$1_K2") (pintype "passive"))
      (node (ref "B25") (pin "U2") (pinfunction "I$1_U2") (pintype "input"))
      (node (ref "C21") (pin "D2") (pinfunction "D_D2") (pintype "output"))
    )
    (net (code "409") (name "Net-(B24I-P$1)") (class "Default")
      (node (ref "B24") (pin "L2") (pinfunction "P$1_L2") (pintype "passive"))
      (node (ref "B26") (pin "E2") (pinfunction "I$1_E2") (pintype "input"))
      (node (ref "C22") (pin "D2") (pinfunction "D_D2") (pintype "output"))
    )
    (net (code "410") (name "Net-(B24J-P$1)") (class "Default")
      (node (ref "B24") (pin "M2") (pinfunction "P$1_M2") (pintype "passive"))
      (node (ref "B26") (pin "H2") (pinfunction "I$1_H2") (pintype "input"))
      (node (ref "C23") (pin "D2") (pinfunction "D_D2") (pintype "output"))
    )
    (net (code "411") (name "Net-(B24K-P$1)") (class "Default")
      (node (ref "B24") (pin "N2") (pinfunction "P$1_N2") (pintype "passive"))
      (node (ref "B26") (pin "K2") (pinfunction "I$1_K2") (pintype "input"))
      (node (ref "C24") (pin "D2") (pinfunction "D_D2") (pintype "output"))
    )
    (net (code "412") (name "Net-(B24L-P$1)") (class "Default")
      (node (ref "B24") (pin "P2") (pinfunction "P$1_P2") (pintype "passive"))
      (node (ref "B26") (pin "M2") (pinfunction "I$1_M2") (pintype "input"))
      (node (ref "C25") (pin "D2") (pinfunction "D_D2") (pintype "output"))
    )
    (net (code "413") (name "Net-(B24M-P$1)") (class "Default")
      (node (ref "B24") (pin "R2") (pinfunction "P$1_R2") (pintype "passive"))
      (node (ref "B26") (pin "P2") (pinfunction "I$1_P2") (pintype "input"))
      (node (ref "C26") (pin "D2") (pinfunction "D_D2") (pintype "output"))
    )
    (net (code "414") (name "Net-(B24N-P$1)") (class "Default")
      (node (ref "B24") (pin "S2") (pinfunction "P$1_S2") (pintype "passive"))
      (node (ref "B26") (pin "S2") (pinfunction "I$1_S2") (pintype "input"))
      (node (ref "C27") (pin "D2") (pinfunction "D_D2") (pintype "output"))
    )
    (net (code "415") (name "Net-(B24O-P$1)") (class "Default")
      (node (ref "B24") (pin "T2") (pinfunction "P$1_T2") (pintype "passive"))
      (node (ref "B26") (pin "U2") (pinfunction "I$1_U2") (pintype "input"))
      (node (ref "C28") (pin "D2") (pinfunction "D_D2") (pintype "output"))
    )
    (net (code "416") (name "Net-(B24P-P$1)") (class "Default")
      (node (ref "B24") (pin "U2") (pinfunction "P$1_U2") (pintype "passive"))
      (node (ref "B32") (pin "P2") (pinfunction "I$1_P2") (pintype "input"))
      (node (ref "C29") (pin "D2") (pinfunction "D_D2") (pintype "output"))
    )
    (net (code "417") (name "Net-(B24Q-P$1)") (class "Default")
      (node (ref "B24") (pin "V2") (pinfunction "P$1_V2") (pintype "passive"))
      (node (ref "B32") (pin "S2") (pinfunction "I$1_S2") (pintype "input"))
      (node (ref "C30") (pin "D2") (pinfunction "D_D2") (pintype "output"))
    )
    (net (code "418") (name "Net-(B27A-D)") (class "Default")
      (node (ref "B27") (pin "D2") (pinfunction "D_D2") (pintype "input"))
      (node (ref "B30") (pin "H2") (pinfunction "O$1_H2") (pintype "open_collector"))
      (node (ref "B30") (pin "J2") (pinfunction "P$1_J2") (pintype "passive"))
    )
    (net (code "419") (name "Net-(B27B-D)") (class "Default")
      (node (ref "B27") (pin "K2") (pinfunction "D_K2") (pintype "input"))
      (node (ref "B30") (pin "N2") (pinfunction "O$1_N2") (pintype "open_collector"))
      (node (ref "B30") (pin "P2") (pinfunction "P$1_P2") (pintype "passive"))
    )
    (net (code "420") (name "Net-(B27C-D)") (class "Default")
      (node (ref "B27") (pin "R2") (pinfunction "D_R2") (pintype "input"))
      (node (ref "B30") (pin "U2") (pinfunction "O$1_U2") (pintype "open_collector"))
      (node (ref "B30") (pin "V2") (pinfunction "P$1_V2") (pintype "passive"))
    )
    (net (code "421") (name "Net-(B28A-D)") (class "Default")
      (node (ref "B28") (pin "D2") (pinfunction "D_D2") (pintype "input"))
      (node (ref "B31") (pin "H2") (pinfunction "O$1_H2") (pintype "open_collector"))
      (node (ref "B31") (pin "J2") (pinfunction "P$1_J2") (pintype "passive"))
    )
    (net (code "422") (name "Net-(B28B-D)") (class "Default")
      (node (ref "B28") (pin "K2") (pinfunction "D_K2") (pintype "input"))
      (node (ref "B31") (pin "N2") (pinfunction "O$1_N2") (pintype "open_collector"))
      (node (ref "B31") (pin "P2") (pinfunction "P$1_P2") (pintype "passive"))
    )
    (net (code "423") (name "Net-(B28C-D)") (class "Default")
      (node (ref "B28") (pin "R2") (pinfunction "D_R2") (pintype "input"))
      (node (ref "B31") (pin "U2") (pinfunction "O$1_U2") (pintype "open_collector"))
      (node (ref "B31") (pin "V2") (pinfunction "P$1_V2") (pintype "passive"))
    )
    (net (code "424") (name "Net-(B32I-O$1)") (class "Default")
      (node (ref "B32") (pin "T2") (pinfunction "O$1_T2") (pintype "open_collector"))
      (node (ref "PDP-12/8I/8") (pin "3") (pinfunction "3_3") (pintype "passive"))
    )
    (net (code "425") (name "POWER_CLEAR") (class "Default")
      (node (ref "A02") (pin "V2") (pinfunction "P$2_V2") (pintype "bidirectional"))
      (node (ref "B32") (pin "K2") (pinfunction "I$1_K2") (pintype "input"))
      (node (ref "D02") (pin "V2") (pinfunction "P$2_V2") (pintype "bidirectional"))
    )
    (net (code "426") (name "RUN") (class "Default")
      (node (ref "A06") (pin "S2") (pinfunction "P$2_S2") (pintype "bidirectional"))
      (node (ref "D06") (pin "S2") (pinfunction "P$2_S2") (pintype "bidirectional"))
    )
    (net (code "427") (name "T2") (class "Default")
      (node (ref "A02") (pin "T2") (pinfunction "P$2_T2") (pintype "bidirectional"))
      (node (ref "B32") (pin "U2") (pinfunction "I$1_U2") (pintype "input"))
      (node (ref "D02") (pin "T2") (pinfunction "P$2_T2") (pintype "bidirectional"))
    )
    (net (code "429") (name "WCOV") (class "Default")
      (node (ref "A10") (pin "P2") (pinfunction "P$2_P2") (pintype "bidirectional"))
      (node (ref "A16") (pin "E2") (pinfunction "I$2_E2") (pintype "input"))
      (node (ref "A16") (pin "L2") (pinfunction "I$2_L2") (pintype "input"))
      (node (ref "A16") (pin "S2") (pinfunction "I$2_S2") (pintype "input"))
      (node (ref "A17") (pin "E2") (pinfunction "I$2_E2") (pintype "input"))
      (node (ref "A17") (pin "L2") (pinfunction "I$2_L2") (pintype "input"))
      (node (ref "A17") (pin "S2") (pinfunction "I$2_S2") (pintype "input"))
      (node (ref "A18") (pin "E2") (pinfunction "I$2_E2") (pintype "input"))
    )
    (net (code "430") (name "WCOV0") (class "Default")
      (node (ref "B29") (pin "N2") (pinfunction "H_N2") (pintype "output"))
      (node (ref "D10") (pin "P2") (pinfunction "P$2_P2") (pintype "bidirectional"))
    )
    (net (code "431") (name "WCOV1") (class "Default")
      (node (ref "B29") (pin "U2") (pinfunction "H_U2") (pintype "output"))
      (node (ref "D15") (pin "P2") (pinfunction "P$2_P2") (pintype "bidirectional"))
    )
    (net (code "432") (name "WCOV2") (class "Default")
      (node (ref "A14") (pin "H2") (pinfunction "H_H2") (pintype "output"))
      (node (ref "D20") (pin "P2") (pinfunction "P$2_P2") (pintype "bidirectional"))
    )
    (net (code "433") (name "WCOV3") (class "Default")
      (node (ref "A14") (pin "N2") (pinfunction "H_N2") (pintype "output"))
      (node (ref "D25") (pin "P2") (pinfunction "P$2_P2") (pintype "bidirectional"))
    )
    (net (code "434") (name "WCOV4") (class "Default")
      (node (ref "A14") (pin "U2") (pinfunction "H_U2") (pintype "output"))
      (node (ref "D30") (pin "P2") (pinfunction "P$2_P2") (pintype "bidirectional"))
    )
    (net (code "435") (name "WCOV5") (class "Default")
      (node (ref "A15") (pin "H2") (pinfunction "H_H2") (pintype "output"))
      (node (ref "A26") (pin "P2") (pinfunction "P$2_P2") (pintype "bidirectional"))
    )
    (net (code "436") (name "WCOV6") (class "Default")
      (node (ref "A15") (pin "N2") (pinfunction "H_N2") (pintype "output"))
      (node (ref "A31") (pin "P2") (pinfunction "P$2_P2") (pintype "bidirectional"))
    )
    (net (code "437") (name "unconnected-(A12I-I$2-PadV2)") (class "Default")
      (node (ref "A12") (pin "V2") (pinfunction "I$2_V2") (pintype "passive"))
    )
    (net (code "438") (name "unconnected-(A13I-I$2-PadV2)") (class "Default")
      (node (ref "A13") (pin "V2") (pinfunction "I$2_V2") (pintype "passive"))
    )
    (net (code "439") (name "unconnected-(A14A-E-PadE2)") (class "Default")
      (node (ref "A14") (pin "E2") (pinfunction "E_E2") (pintype "passive"))
    )
    (net (code "440") (name "unconnected-(A14A-F-PadF2)") (class "Default")
      (node (ref "A14") (pin "F2") (pinfunction "F_F2") (pintype "passive"))
    )
    (net (code "441") (name "unconnected-(A14B-E-PadL2)") (class "Default")
      (node (ref "A14") (pin "L2") (pinfunction "E_L2") (pintype "passive"))
    )
    (net (code "442") (name "unconnected-(A14B-F-PadM2)") (class "Default")
      (node (ref "A14") (pin "M2") (pinfunction "F_M2") (pintype "passive"))
    )
    (net (code "443") (name "unconnected-(A14C-E-PadS2)") (class "Default")
      (node (ref "A14") (pin "S2") (pinfunction "E_S2") (pintype "passive"))
    )
    (net (code "444") (name "unconnected-(A14C-F-PadT2)") (class "Default")
      (node (ref "A14") (pin "T2") (pinfunction "F_T2") (pintype "passive"))
    )
    (net (code "445") (name "unconnected-(A15A-E-PadE2)") (class "Default")
      (node (ref "A15") (pin "E2") (pinfunction "E_E2") (pintype "passive"))
    )
    (net (code "446") (name "unconnected-(A15A-F-PadF2)") (class "Default")
      (node (ref "A15") (pin "F2") (pinfunction "F_F2") (pintype "passive"))
    )
    (net (code "447") (name "unconnected-(A15B-E-PadL2)") (class "Default")
      (node (ref "A15") (pin "L2") (pinfunction "E_L2") (pintype "passive"))
    )
    (net (code "448") (name "unconnected-(A15B-F-PadM2)") (class "Default")
      (node (ref "A15") (pin "M2") (pinfunction "F_M2") (pintype "passive"))
    )
    (net (code "449") (name "unconnected-(A16C-I$3-PadF2)") (class "Default")
      (node (ref "A16") (pin "F2") (pinfunction "I$3_F2") (pintype "passive"))
    )
    (net (code "450") (name "unconnected-(A16E-I$3-PadM2)") (class "Default")
      (node (ref "A16") (pin "M2") (pinfunction "I$3_M2") (pintype "passive"))
    )
    (net (code "451") (name "unconnected-(A16G-I$3-PadT2)") (class "Default")
      (node (ref "A16") (pin "T2") (pinfunction "I$3_T2") (pintype "passive"))
    )
    (net (code "452") (name "unconnected-(A17C-I$3-PadF2)") (class "Default")
      (node (ref "A17") (pin "F2") (pinfunction "I$3_F2") (pintype "passive"))
    )
    (net (code "453") (name "unconnected-(A17E-I$3-PadM2)") (class "Default")
      (node (ref "A17") (pin "M2") (pinfunction "I$3_M2") (pintype "passive"))
    )
    (net (code "454") (name "unconnected-(A17G-I$3-PadT2)") (class "Default")
      (node (ref "A17") (pin "T2") (pinfunction "I$3_T2") (pintype "passive"))
    )
    (net (code "455") (name "unconnected-(A18C-I$3-PadF2)") (class "Default")
      (node (ref "A18") (pin "F2") (pinfunction "I$3_F2") (pintype "passive"))
    )
    (net (code "456") (name "unconnected-(A18E-I$2-PadL2)") (class "Default")
      (node (ref "A18") (pin "L2") (pinfunction "I$2_L2") (pintype "input"))
    )
    (net (code "457") (name "unconnected-(A18E-I$3-PadM2)") (class "Default")
      (node (ref "A18") (pin "M2") (pinfunction "I$3_M2") (pintype "passive"))
    )
    (net (code "458") (name "unconnected-(A19C-1-PadJ2)") (class "Default")
      (node (ref "A19") (pin "J2") (pinfunction "1_J2") (pintype "open_collector"))
    )
    (net (code "459") (name "unconnected-(A19C-SET-PadM2)") (class "Default")
      (node (ref "A19") (pin "M2") (pinfunction "SET_M2") (pintype "passive"))
    )
    (net (code "460") (name "unconnected-(B02I-I$2-PadV2)") (class "Default")
      (node (ref "B02") (pin "V2") (pinfunction "I$2_V2") (pintype "passive"))
    )
    (net (code "461") (name "unconnected-(B03A-EN0-PadE2)") (class "Default")
      (node (ref "B03") (pin "E2") (pinfunction "EN0_E2") (pintype "passive"))
    )
    (net (code "462") (name "unconnected-(B03A-PU0-PadD2)") (class "Default")
      (node (ref "B03") (pin "D2") (pinfunction "PU0_D2") (pintype "input"))
    )
    (net (code "463") (name "unconnected-(B03D-I$1-PadP2)") (class "Default")
      (node (ref "B03") (pin "P2") (pinfunction "I$1_P2") (pintype "passive"))
    )
    (net (code "464") (name "unconnected-(B03E-I$1-PadV2)") (class "Default")
      (node (ref "B03") (pin "V2") (pinfunction "I$1_V2") (pintype "passive"))
    )
    (net (code "465") (name "unconnected-(B04I-I$2-PadV2)") (class "Default")
      (node (ref "B04") (pin "V2") (pinfunction "I$2_V2") (pintype "passive"))
    )
    (net (code "466") (name "unconnected-(B05I-I$2-PadV2)") (class "Default")
      (node (ref "B05") (pin "V2") (pinfunction "I$2_V2") (pintype "passive"))
    )
    (net (code "467") (name "unconnected-(B06C-I$3-PadF2)") (class "Default")
      (node (ref "B06") (pin "F2") (pinfunction "I$3_F2") (pintype "passive"))
    )
    (net (code "468") (name "unconnected-(B06E-I$3-PadM2)") (class "Default")
      (node (ref "B06") (pin "M2") (pinfunction "I$3_M2") (pintype "passive"))
    )
    (net (code "469") (name "unconnected-(B06G-I$3-PadT2)") (class "Default")
      (node (ref "B06") (pin "T2") (pinfunction "I$3_T2") (pintype "passive"))
    )
    (net (code "470") (name "unconnected-(B07I-I$2-PadV2)") (class "Default")
      (node (ref "B07") (pin "V2") (pinfunction "I$2_V2") (pintype "passive"))
    )
    (net (code "471") (name "unconnected-(B08C-I$3-PadF2)") (class "Default")
      (node (ref "B08") (pin "F2") (pinfunction "I$3_F2") (pintype "passive"))
    )
    (net (code "472") (name "unconnected-(B08E-I$3-PadM2)") (class "Default")
      (node (ref "B08") (pin "M2") (pinfunction "I$3_M2") (pintype "passive"))
    )
    (net (code "473") (name "unconnected-(B08G-I$3-PadT2)") (class "Default")
      (node (ref "B08") (pin "T2") (pinfunction "I$3_T2") (pintype "passive"))
    )
    (net (code "474") (name "unconnected-(B10I-I$2-PadV2)") (class "Default")
      (node (ref "B10") (pin "V2") (pinfunction "I$2_V2") (pintype "passive"))
    )
    (net (code "475") (name "unconnected-(B12A-H-PadH2)") (class "Default")
      (node (ref "B12") (pin "H2") (pinfunction "H_H2") (pintype "input"))
    )
    (net (code "476") (name "unconnected-(B13I-I$2-PadV2)") (class "Default")
      (node (ref "B13") (pin "V2") (pinfunction "I$2_V2") (pintype "passive"))
    )
    (net (code "477") (name "unconnected-(B14C-SET-PadM2)") (class "Default")
      (node (ref "B14") (pin "M2") (pinfunction "SET_M2") (pintype "passive"))
    )
    (net (code "478") (name "unconnected-(B14D-0-PadS2)") (class "Default")
      (node (ref "B14") (pin "S2") (pinfunction "0_S2") (pintype "open_collector"))
    )
    (net (code "479") (name "unconnected-(B15I-I$2-PadV2)") (class "Default")
      (node (ref "B15") (pin "V2") (pinfunction "I$2_V2") (pintype "passive"))
    )
    (net (code "480") (name "unconnected-(B16C-SET-PadM2)") (class "Default")
      (node (ref "B16") (pin "M2") (pinfunction "SET_M2") (pintype "passive"))
    )
    (net (code "481") (name "unconnected-(B16D-0-PadS2)") (class "Default")
      (node (ref "B16") (pin "S2") (pinfunction "0_S2") (pintype "open_collector"))
    )
    (net (code "482") (name "unconnected-(B17C-SET-PadM2)") (class "Default")
      (node (ref "B17") (pin "M2") (pinfunction "SET_M2") (pintype "passive"))
    )
    (net (code "483") (name "unconnected-(B17D-0-PadS2)") (class "Default")
      (node (ref "B17") (pin "S2") (pinfunction "0_S2") (pintype "open_collector"))
    )
    (net (code "484") (name "unconnected-(B18C-SET-PadM2)") (class "Default")
      (node (ref "B18") (pin "M2") (pinfunction "SET_M2") (pintype "passive"))
    )
    (net (code "485") (name "unconnected-(B18D-0-PadS2)") (class "Default")
      (node (ref "B18") (pin "S2") (pinfunction "0_S2") (pintype "open_collector"))
    )
    (net (code "486") (name "unconnected-(B19C-SET-PadM2)") (class "Default")
      (node (ref "B19") (pin "M2") (pinfunction "SET_M2") (pintype "passive"))
    )
    (net (code "487") (name "unconnected-(B19D-0-PadS2)") (class "Default")
      (node (ref "B19") (pin "S2") (pinfunction "0_S2") (pintype "open_collector"))
    )
    (net (code "488") (name "unconnected-(B20C-SET-PadM2)") (class "Default")
      (node (ref "B20") (pin "M2") (pinfunction "SET_M2") (pintype "passive"))
    )
    (net (code "489") (name "unconnected-(B20D-0-PadS2)") (class "Default")
      (node (ref "B20") (pin "S2") (pinfunction "0_S2") (pintype "open_collector"))
    )
    (net (code "490") (name "unconnected-(B21C-SET-PadM2)") (class "Default")
      (node (ref "B21") (pin "M2") (pinfunction "SET_M2") (pintype "passive"))
    )
    (net (code "491") (name "unconnected-(B21D-0-PadS2)") (class "Default")
      (node (ref "B21") (pin "S2") (pinfunction "0_S2") (pintype "open_collector"))
    )
    (net (code "492") (name "unconnected-(B22E-E-PadM2)") (class "Default")
      (node (ref "B22") (pin "M2") (pinfunction "E_M2") (pintype "input"))
    )
    (net (code "493") (name "unconnected-(B23C-I$3-PadF2)") (class "Default")
      (node (ref "B23") (pin "F2") (pinfunction "I$3_F2") (pintype "passive"))
    )
    (net (code "494") (name "unconnected-(B23G-I$3-PadT2)") (class "Default")
      (node (ref "B23") (pin "T2") (pinfunction "I$3_T2") (pintype "passive"))
    )
    (net (code "495") (name "unconnected-(B25I-I$2-PadV2)") (class "Default")
      (node (ref "B25") (pin "V2") (pinfunction "I$2_V2") (pintype "passive"))
    )
    (net (code "496") (name "unconnected-(B26I-I$2-PadV2)") (class "Default")
      (node (ref "B26") (pin "V2") (pinfunction "I$2_V2") (pintype "passive"))
    )
    (net (code "497") (name "unconnected-(B27A-E-PadE2)") (class "Default")
      (node (ref "B27") (pin "E2") (pinfunction "E_E2") (pintype "passive"))
    )
    (net (code "498") (name "unconnected-(B27A-F-PadF2)") (class "Default")
      (node (ref "B27") (pin "F2") (pinfunction "F_F2") (pintype "passive"))
    )
    (net (code "499") (name "unconnected-(B27B-E-PadL2)") (class "Default")
      (node (ref "B27") (pin "L2") (pinfunction "E_L2") (pintype "passive"))
    )
    (net (code "500") (name "unconnected-(B27B-F-PadM2)") (class "Default")
      (node (ref "B27") (pin "M2") (pinfunction "F_M2") (pintype "passive"))
    )
    (net (code "501") (name "unconnected-(B27C-E-PadS2)") (class "Default")
      (node (ref "B27") (pin "S2") (pinfunction "E_S2") (pintype "passive"))
    )
    (net (code "502") (name "unconnected-(B27C-F-PadT2)") (class "Default")
      (node (ref "B27") (pin "T2") (pinfunction "F_T2") (pintype "passive"))
    )
    (net (code "503") (name "unconnected-(B28A-E-PadE2)") (class "Default")
      (node (ref "B28") (pin "E2") (pinfunction "E_E2") (pintype "passive"))
    )
    (net (code "504") (name "unconnected-(B28A-F-PadF2)") (class "Default")
      (node (ref "B28") (pin "F2") (pinfunction "F_F2") (pintype "passive"))
    )
    (net (code "505") (name "unconnected-(B28B-E-PadL2)") (class "Default")
      (node (ref "B28") (pin "L2") (pinfunction "E_L2") (pintype "passive"))
    )
    (net (code "506") (name "unconnected-(B28B-F-PadM2)") (class "Default")
      (node (ref "B28") (pin "M2") (pinfunction "F_M2") (pintype "passive"))
    )
    (net (code "507") (name "unconnected-(B28C-E-PadS2)") (class "Default")
      (node (ref "B28") (pin "S2") (pinfunction "E_S2") (pintype "passive"))
    )
    (net (code "508") (name "unconnected-(B28C-F-PadT2)") (class "Default")
      (node (ref "B28") (pin "T2") (pinfunction "F_T2") (pintype "passive"))
    )
    (net (code "509") (name "unconnected-(B29A-E-PadE2)") (class "Default")
      (node (ref "B29") (pin "E2") (pinfunction "E_E2") (pintype "passive"))
    )
    (net (code "510") (name "unconnected-(B29A-F-PadF2)") (class "Default")
      (node (ref "B29") (pin "F2") (pinfunction "F_F2") (pintype "passive"))
    )
    (net (code "511") (name "unconnected-(B29B-E-PadL2)") (class "Default")
      (node (ref "B29") (pin "L2") (pinfunction "E_L2") (pintype "passive"))
    )
    (net (code "512") (name "unconnected-(B29B-F-PadM2)") (class "Default")
      (node (ref "B29") (pin "M2") (pinfunction "F_M2") (pintype "passive"))
    )
    (net (code "513") (name "unconnected-(B29C-E-PadS2)") (class "Default")
      (node (ref "B29") (pin "S2") (pinfunction "E_S2") (pintype "passive"))
    )
    (net (code "514") (name "unconnected-(B29C-F-PadT2)") (class "Default")
      (node (ref "B29") (pin "T2") (pinfunction "F_T2") (pintype "passive"))
    )
    (net (code "515") (name "unconnected-(B30C-I$3-PadF2)") (class "Default")
      (node (ref "B30") (pin "F2") (pinfunction "I$3_F2") (pintype "passive"))
    )
    (net (code "516") (name "unconnected-(B30E-I$3-PadM2)") (class "Default")
      (node (ref "B30") (pin "M2") (pinfunction "I$3_M2") (pintype "passive"))
    )
    (net (code "517") (name "unconnected-(B30G-I$3-PadT2)") (class "Default")
      (node (ref "B30") (pin "T2") (pinfunction "I$3_T2") (pintype "passive"))
    )
    (net (code "518") (name "unconnected-(B31C-I$3-PadF2)") (class "Default")
      (node (ref "B31") (pin "F2") (pinfunction "I$3_F2") (pintype "passive"))
    )
    (net (code "519") (name "unconnected-(B31E-I$3-PadM2)") (class "Default")
      (node (ref "B31") (pin "M2") (pinfunction "I$3_M2") (pintype "passive"))
    )
    (net (code "520") (name "unconnected-(B31G-I$3-PadT2)") (class "Default")
      (node (ref "B31") (pin "T2") (pinfunction "I$3_T2") (pintype "passive"))
    )
    (net (code "521") (name "unconnected-(B32I-I$2-PadV2)") (class "Default")
      (node (ref "B32") (pin "V2") (pinfunction "I$2_V2") (pintype "passive"))
    )
    (net (code "522") (name "~{-BMB3}") (class "Default")
      (node (ref "A03") (pin "K2") (pinfunction "P$2_K2") (pintype "bidirectional"))
      (node (ref "D03") (pin "K2") (pinfunction "P$2_K2") (pintype "bidirectional"))
    )
    (net (code "523") (name "~{-BMB4}") (class "Default")
      (node (ref "A03") (pin "P2") (pinfunction "P$2_P2") (pintype "bidirectional"))
      (node (ref "D03") (pin "P2") (pinfunction "P$2_P2") (pintype "bidirectional"))
    )
    (net (code "524") (name "~{-BMB5}") (class "Default")
      (node (ref "A03") (pin "T2") (pinfunction "P$2_T2") (pintype "bidirectional"))
      (node (ref "D03") (pin "T2") (pinfunction "P$2_T2") (pintype "bidirectional"))
    )
    (net (code "525") (name "~{-BMB6}") (class "Default")
      (node (ref "A04") (pin "D2") (pinfunction "P$2_D2") (pintype "bidirectional"))
      (node (ref "D04") (pin "D2") (pinfunction "P$2_D2") (pintype "bidirectional"))
    )
    (net (code "526") (name "~{-BMB7}") (class "Default")
      (node (ref "A04") (pin "H2") (pinfunction "P$2_H2") (pintype "bidirectional"))
      (node (ref "D04") (pin "H2") (pinfunction "P$2_H2") (pintype "bidirectional"))
    )
    (net (code "527") (name "~{-BMB8}") (class "Default")
      (node (ref "A04") (pin "M2") (pinfunction "P$2_M2") (pintype "bidirectional"))
      (node (ref "D04") (pin "M2") (pinfunction "P$2_M2") (pintype "bidirectional"))
    )
    (net (code "528") (name "~{BREAK}") (class "Default")
      (node (ref "A18") (pin "N2") (pinfunction "O$1_N2") (pintype "open_collector"))
      (node (ref "A18") (pin "P2") (pinfunction "P$1_P2") (pintype "passive"))
      (node (ref "B03") (pin "S2") (pinfunction "EN0_S2") (pintype "passive"))
    )
    (net (code "529") (name "~{BRK_SYNC_CLK}") (class "Default")
      (node (ref "B13") (pin "T2") (pinfunction "O$1_T2") (pintype "open_collector"))
      (node (ref "PDP-12/8I/8") (pin "1") (pinfunction "1_1") (pintype "passive"))
    )
  )
)
